# 1-Schematic_NotKia_168x.net
KiCad netlist of a schematic drawn in EasyEDA
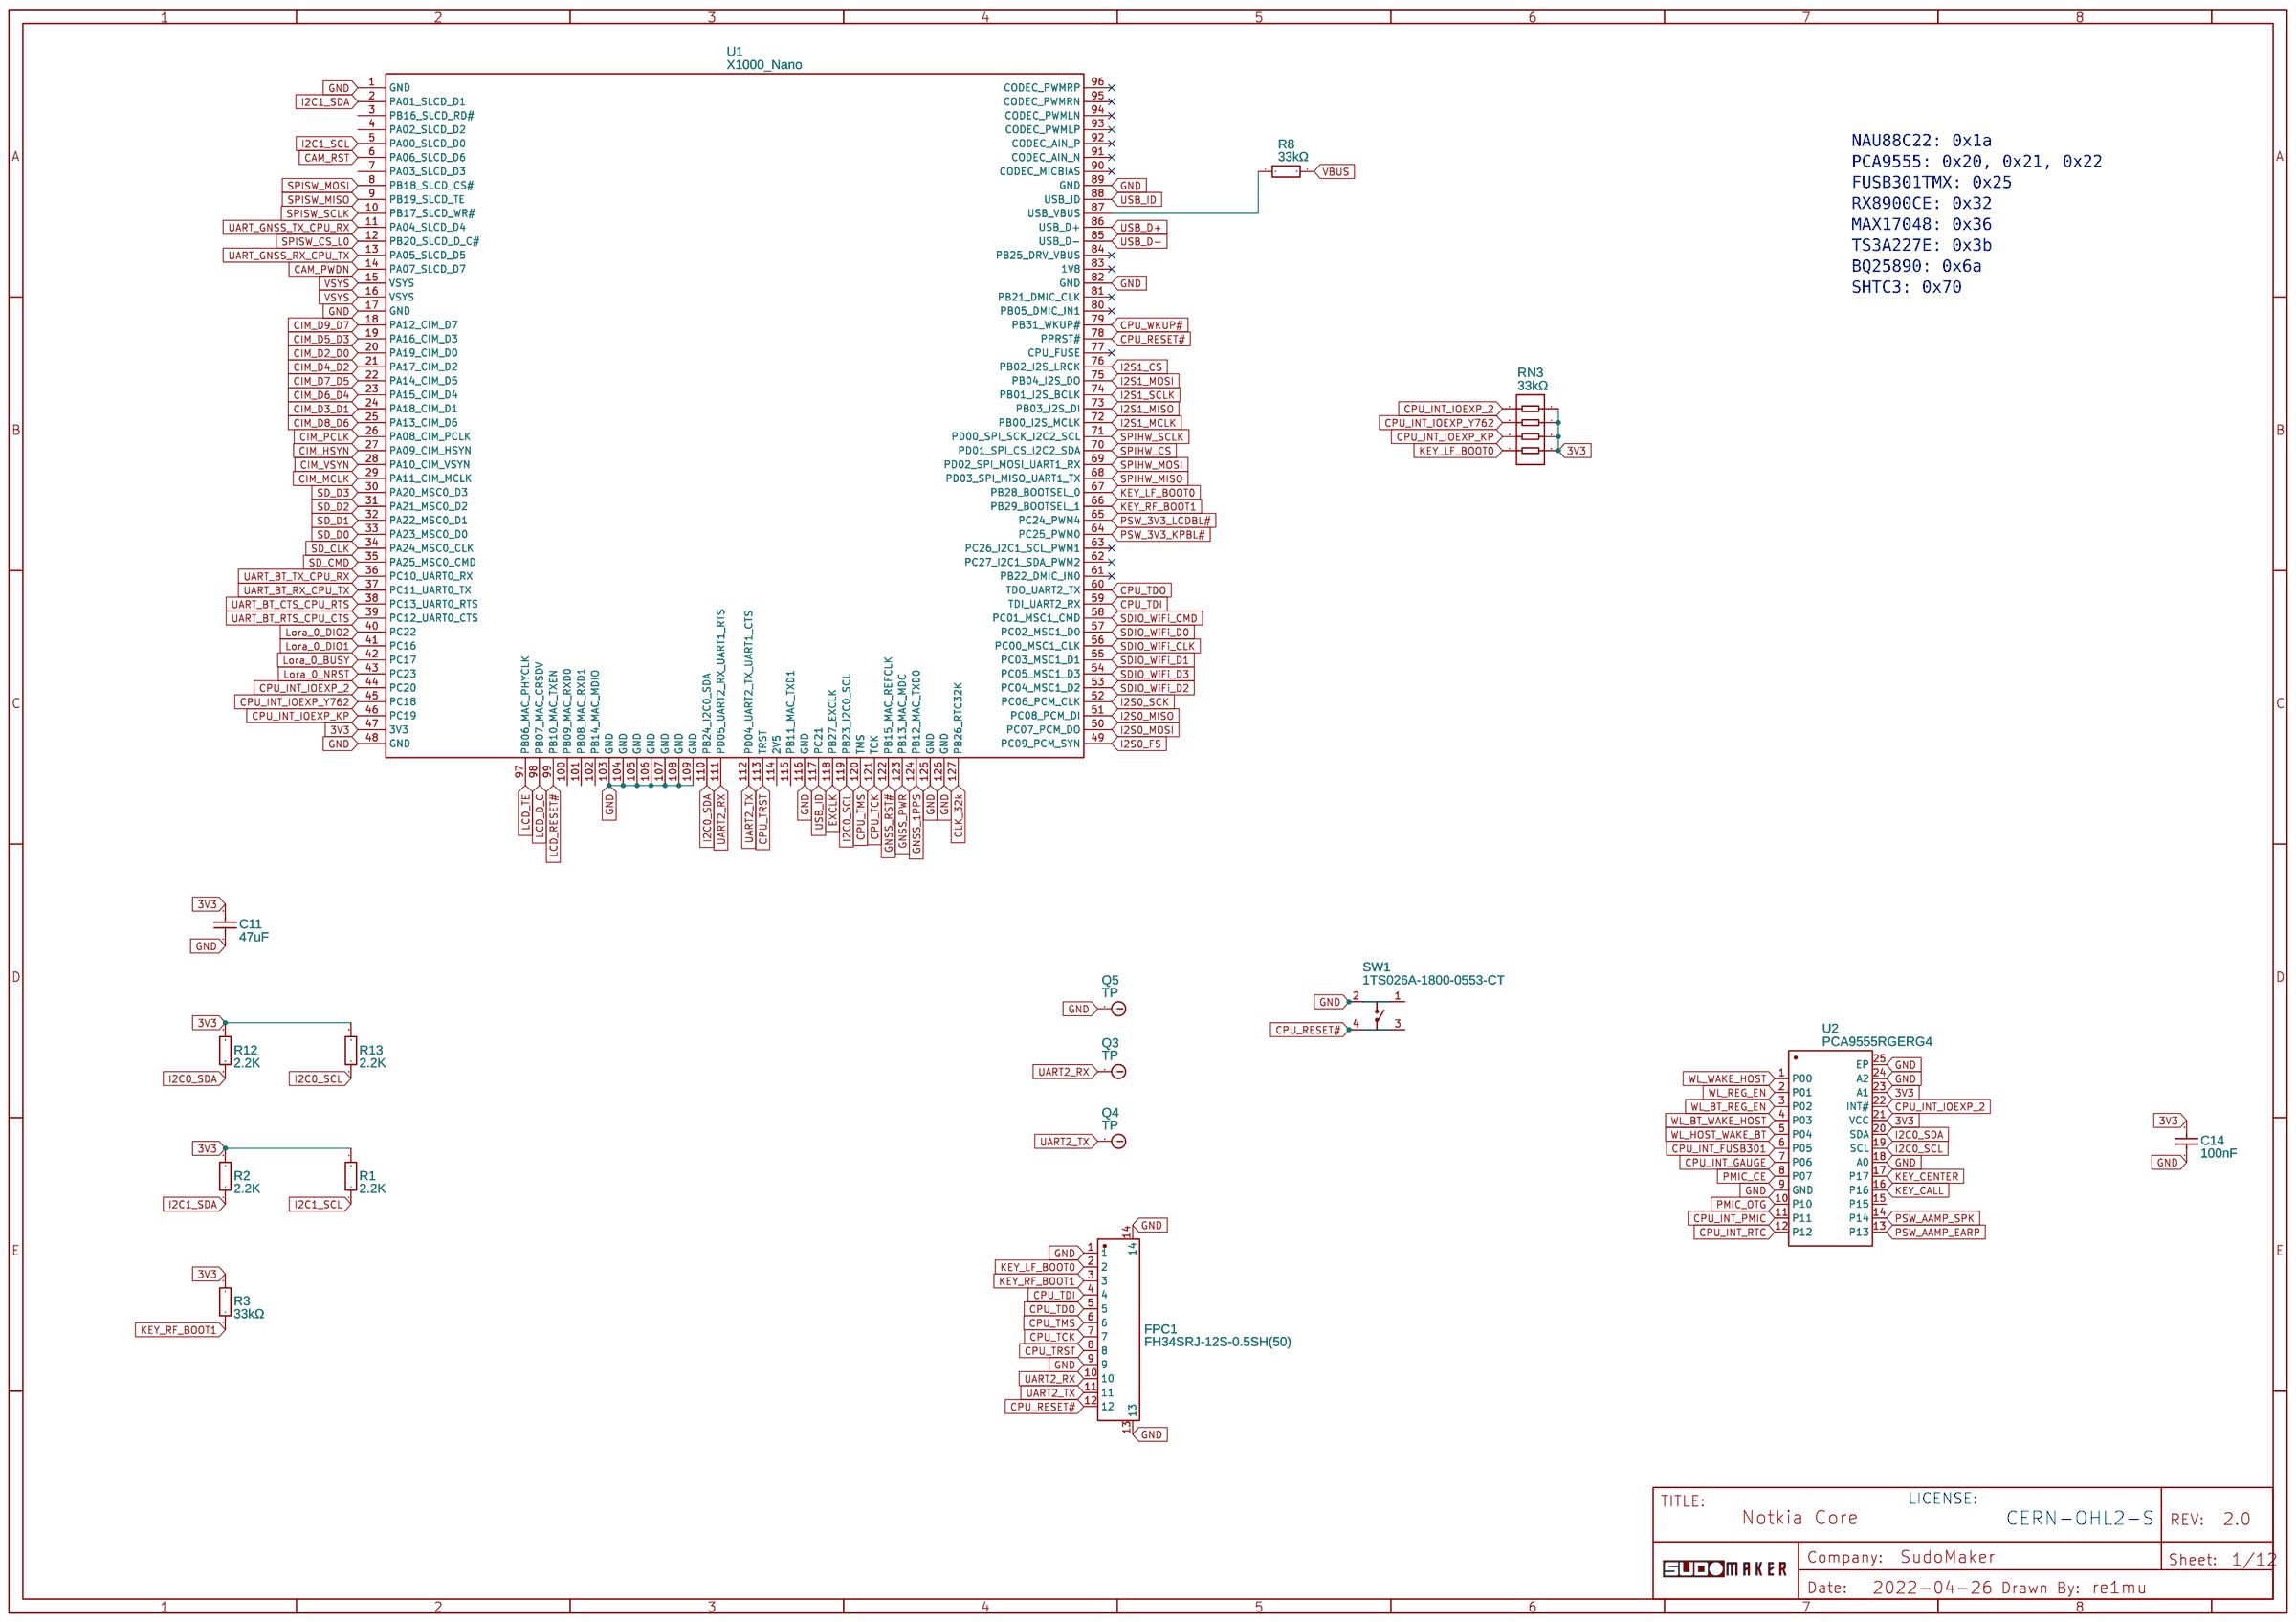
[diagram p0: Core]
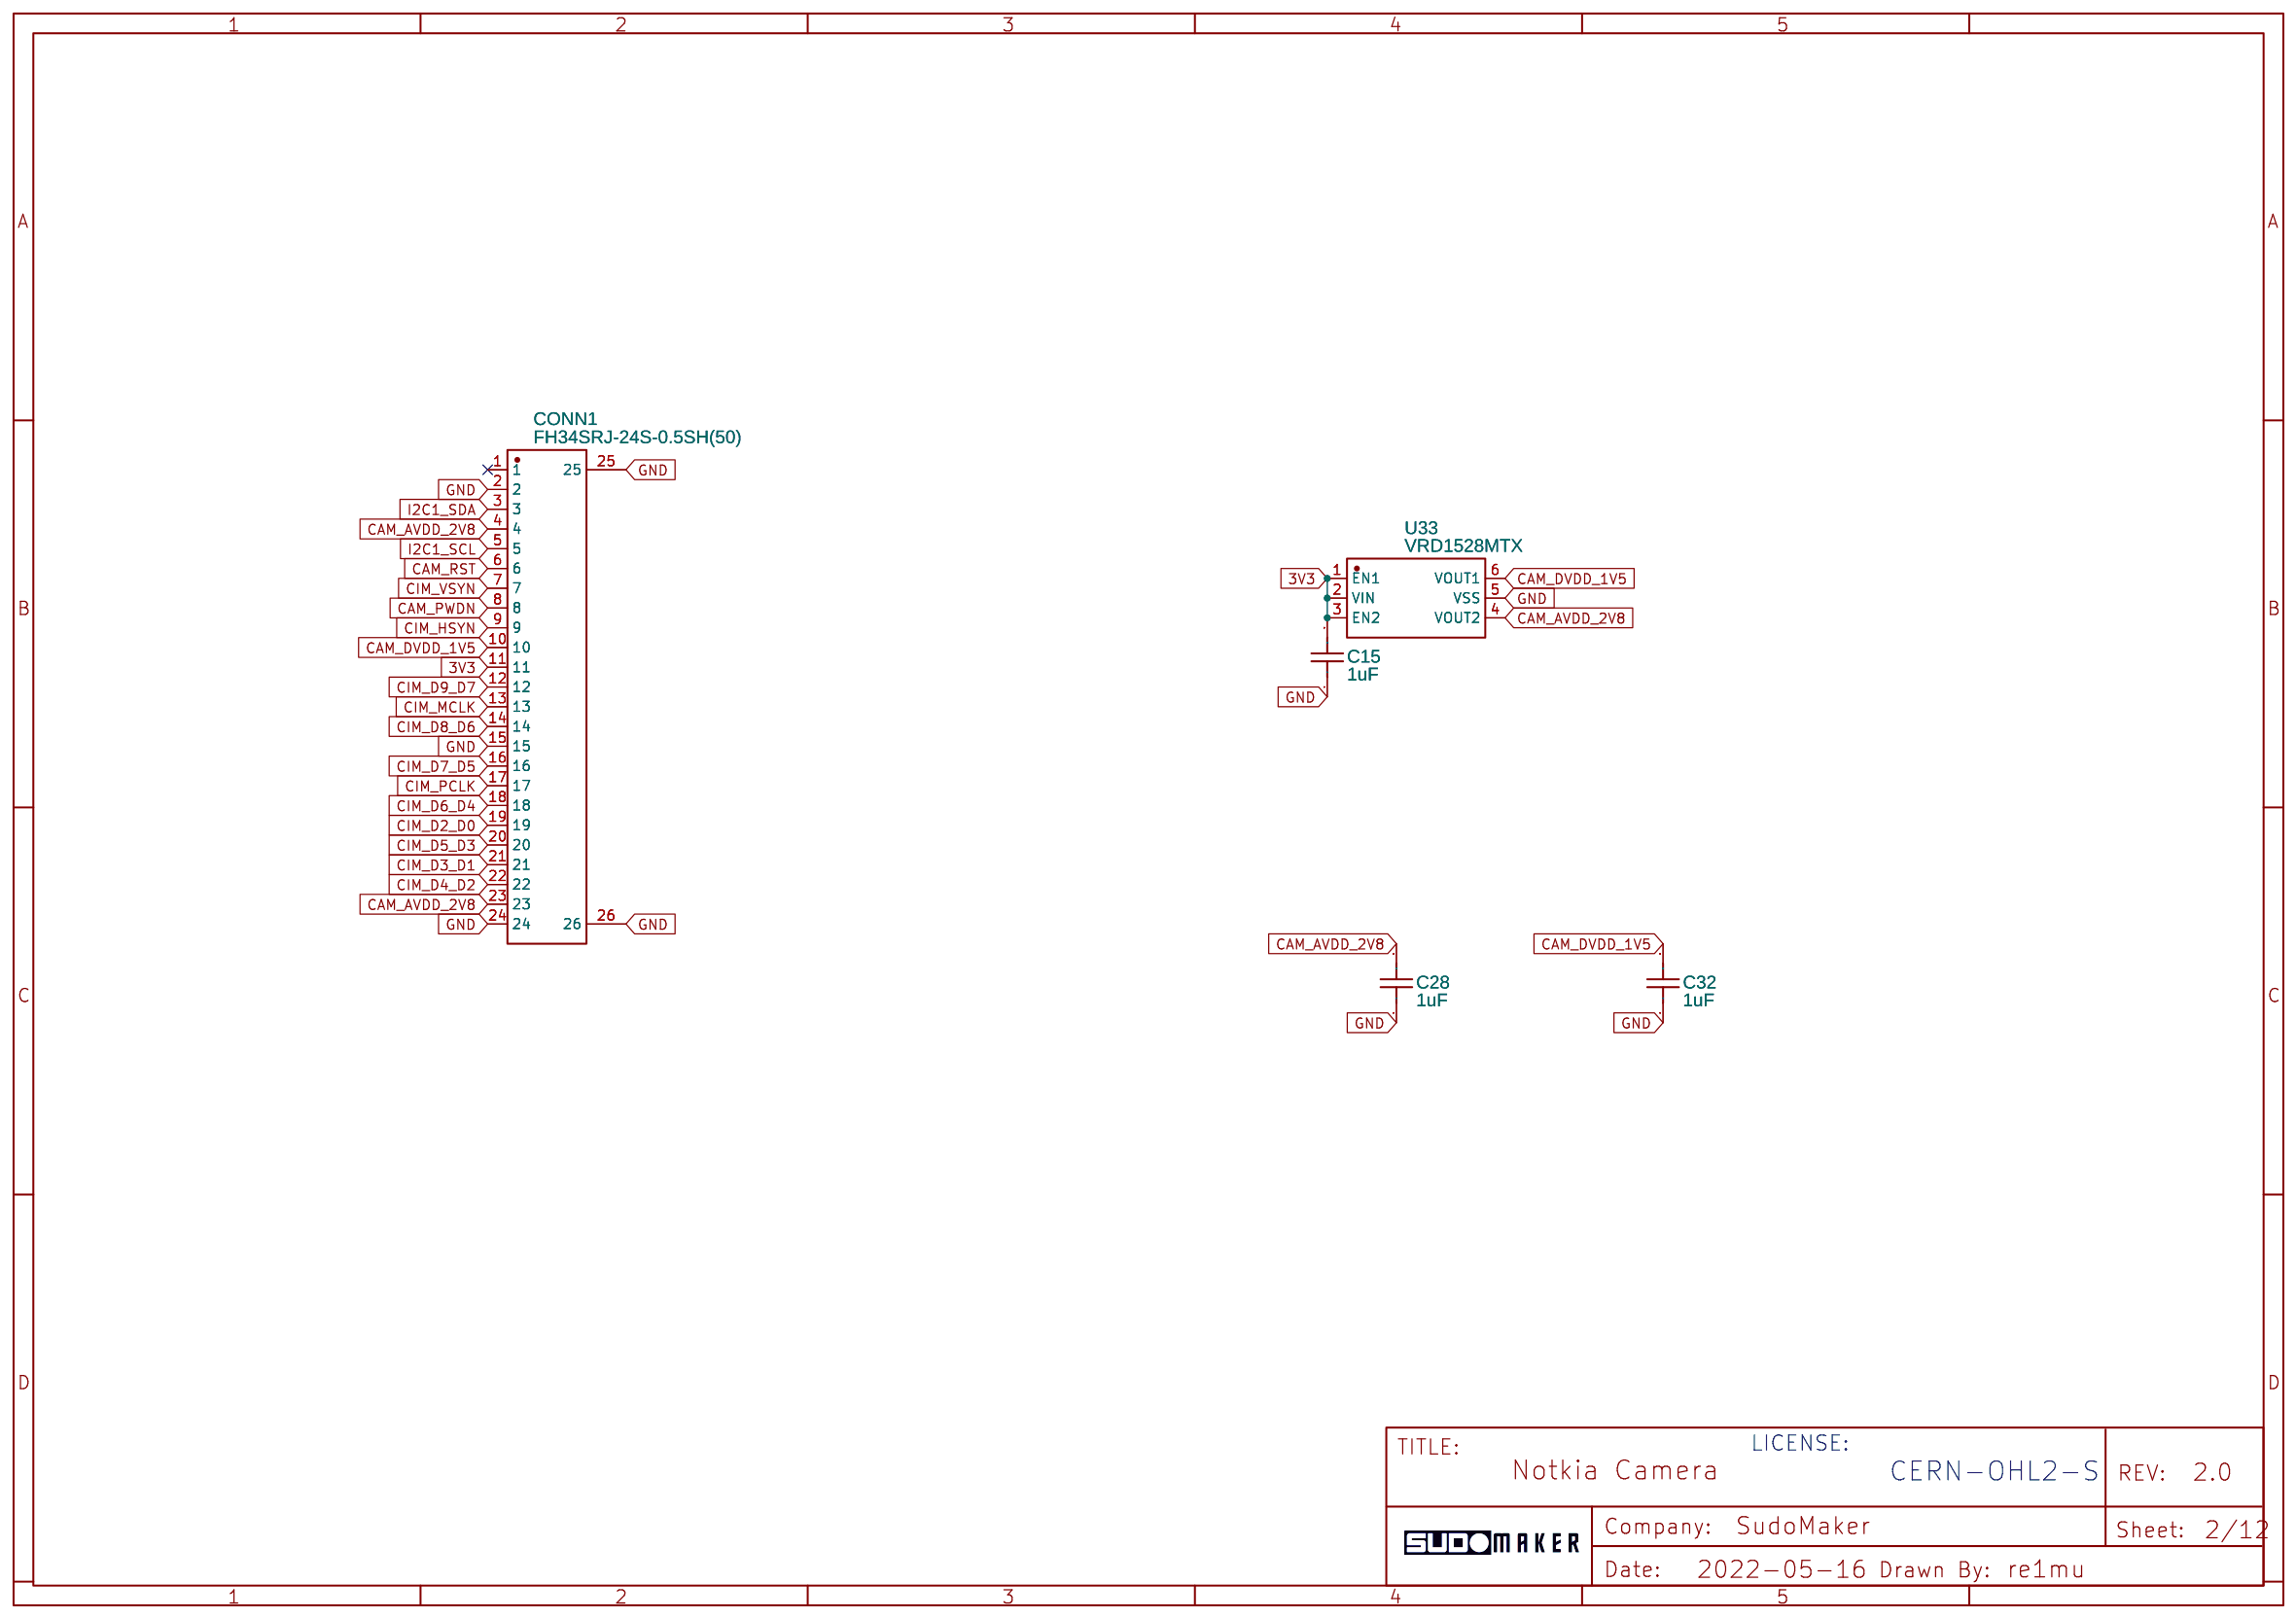
[diagram p1: Camera]
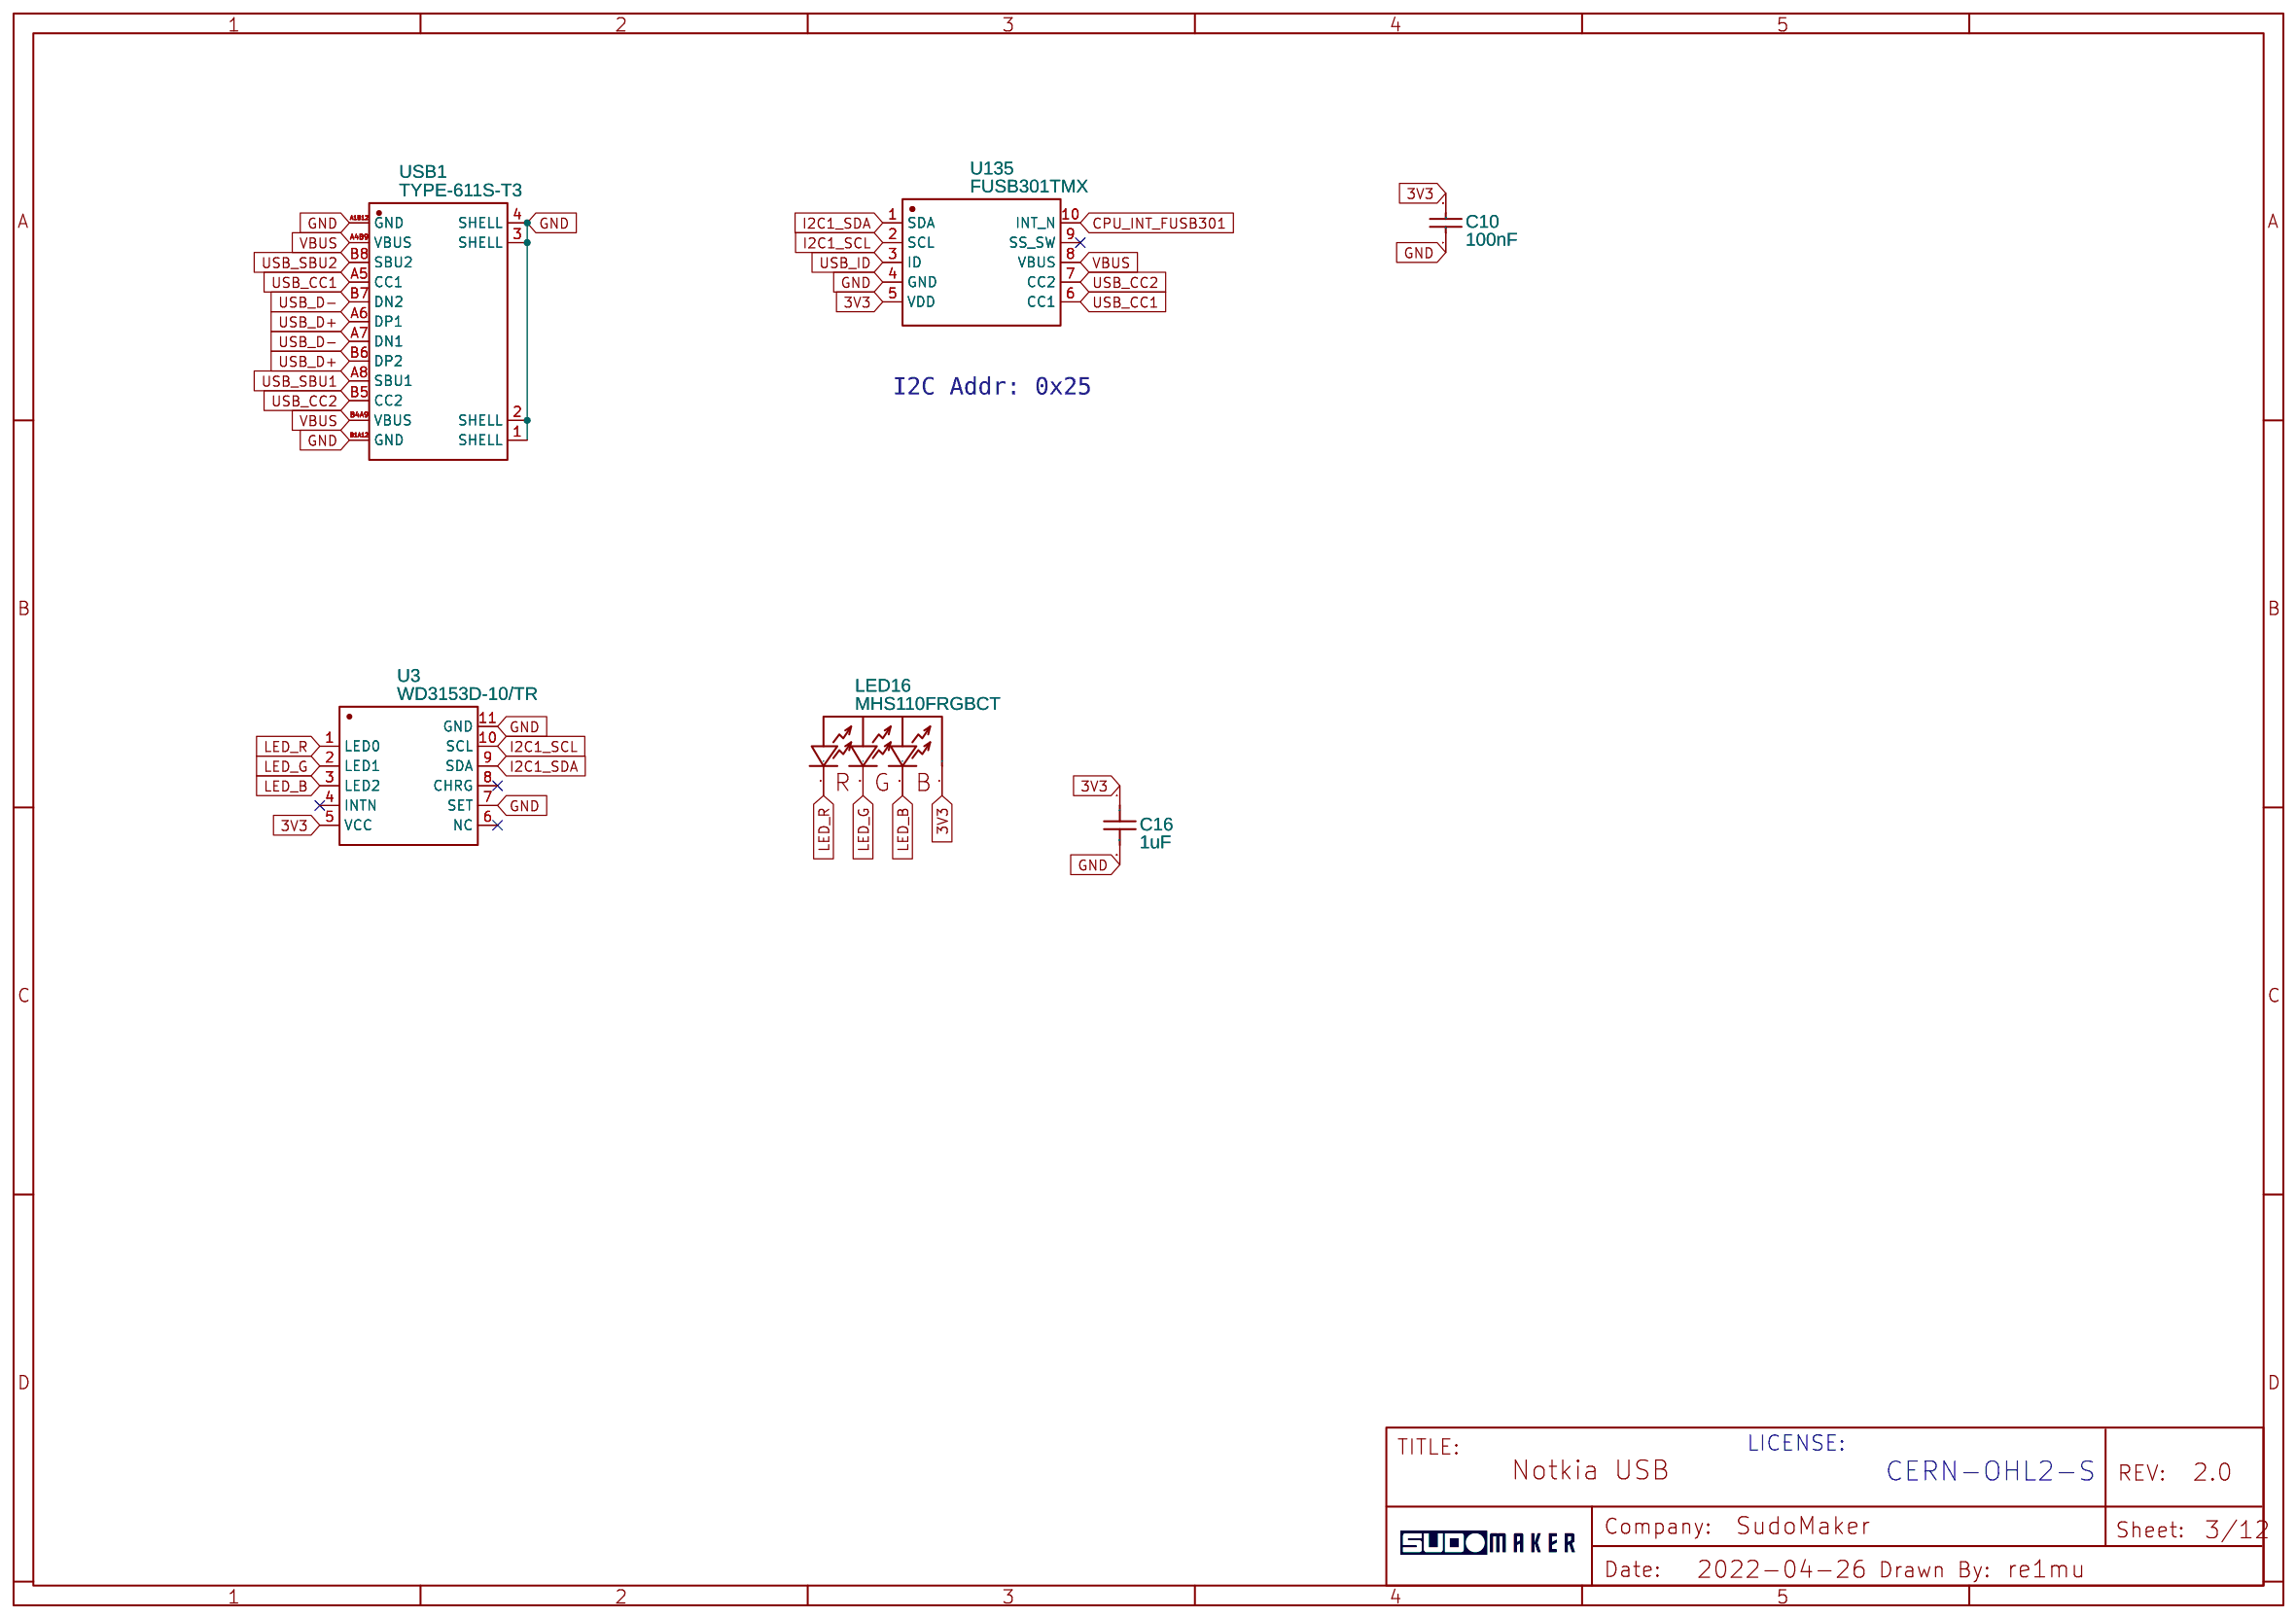
[diagram p2: USB]
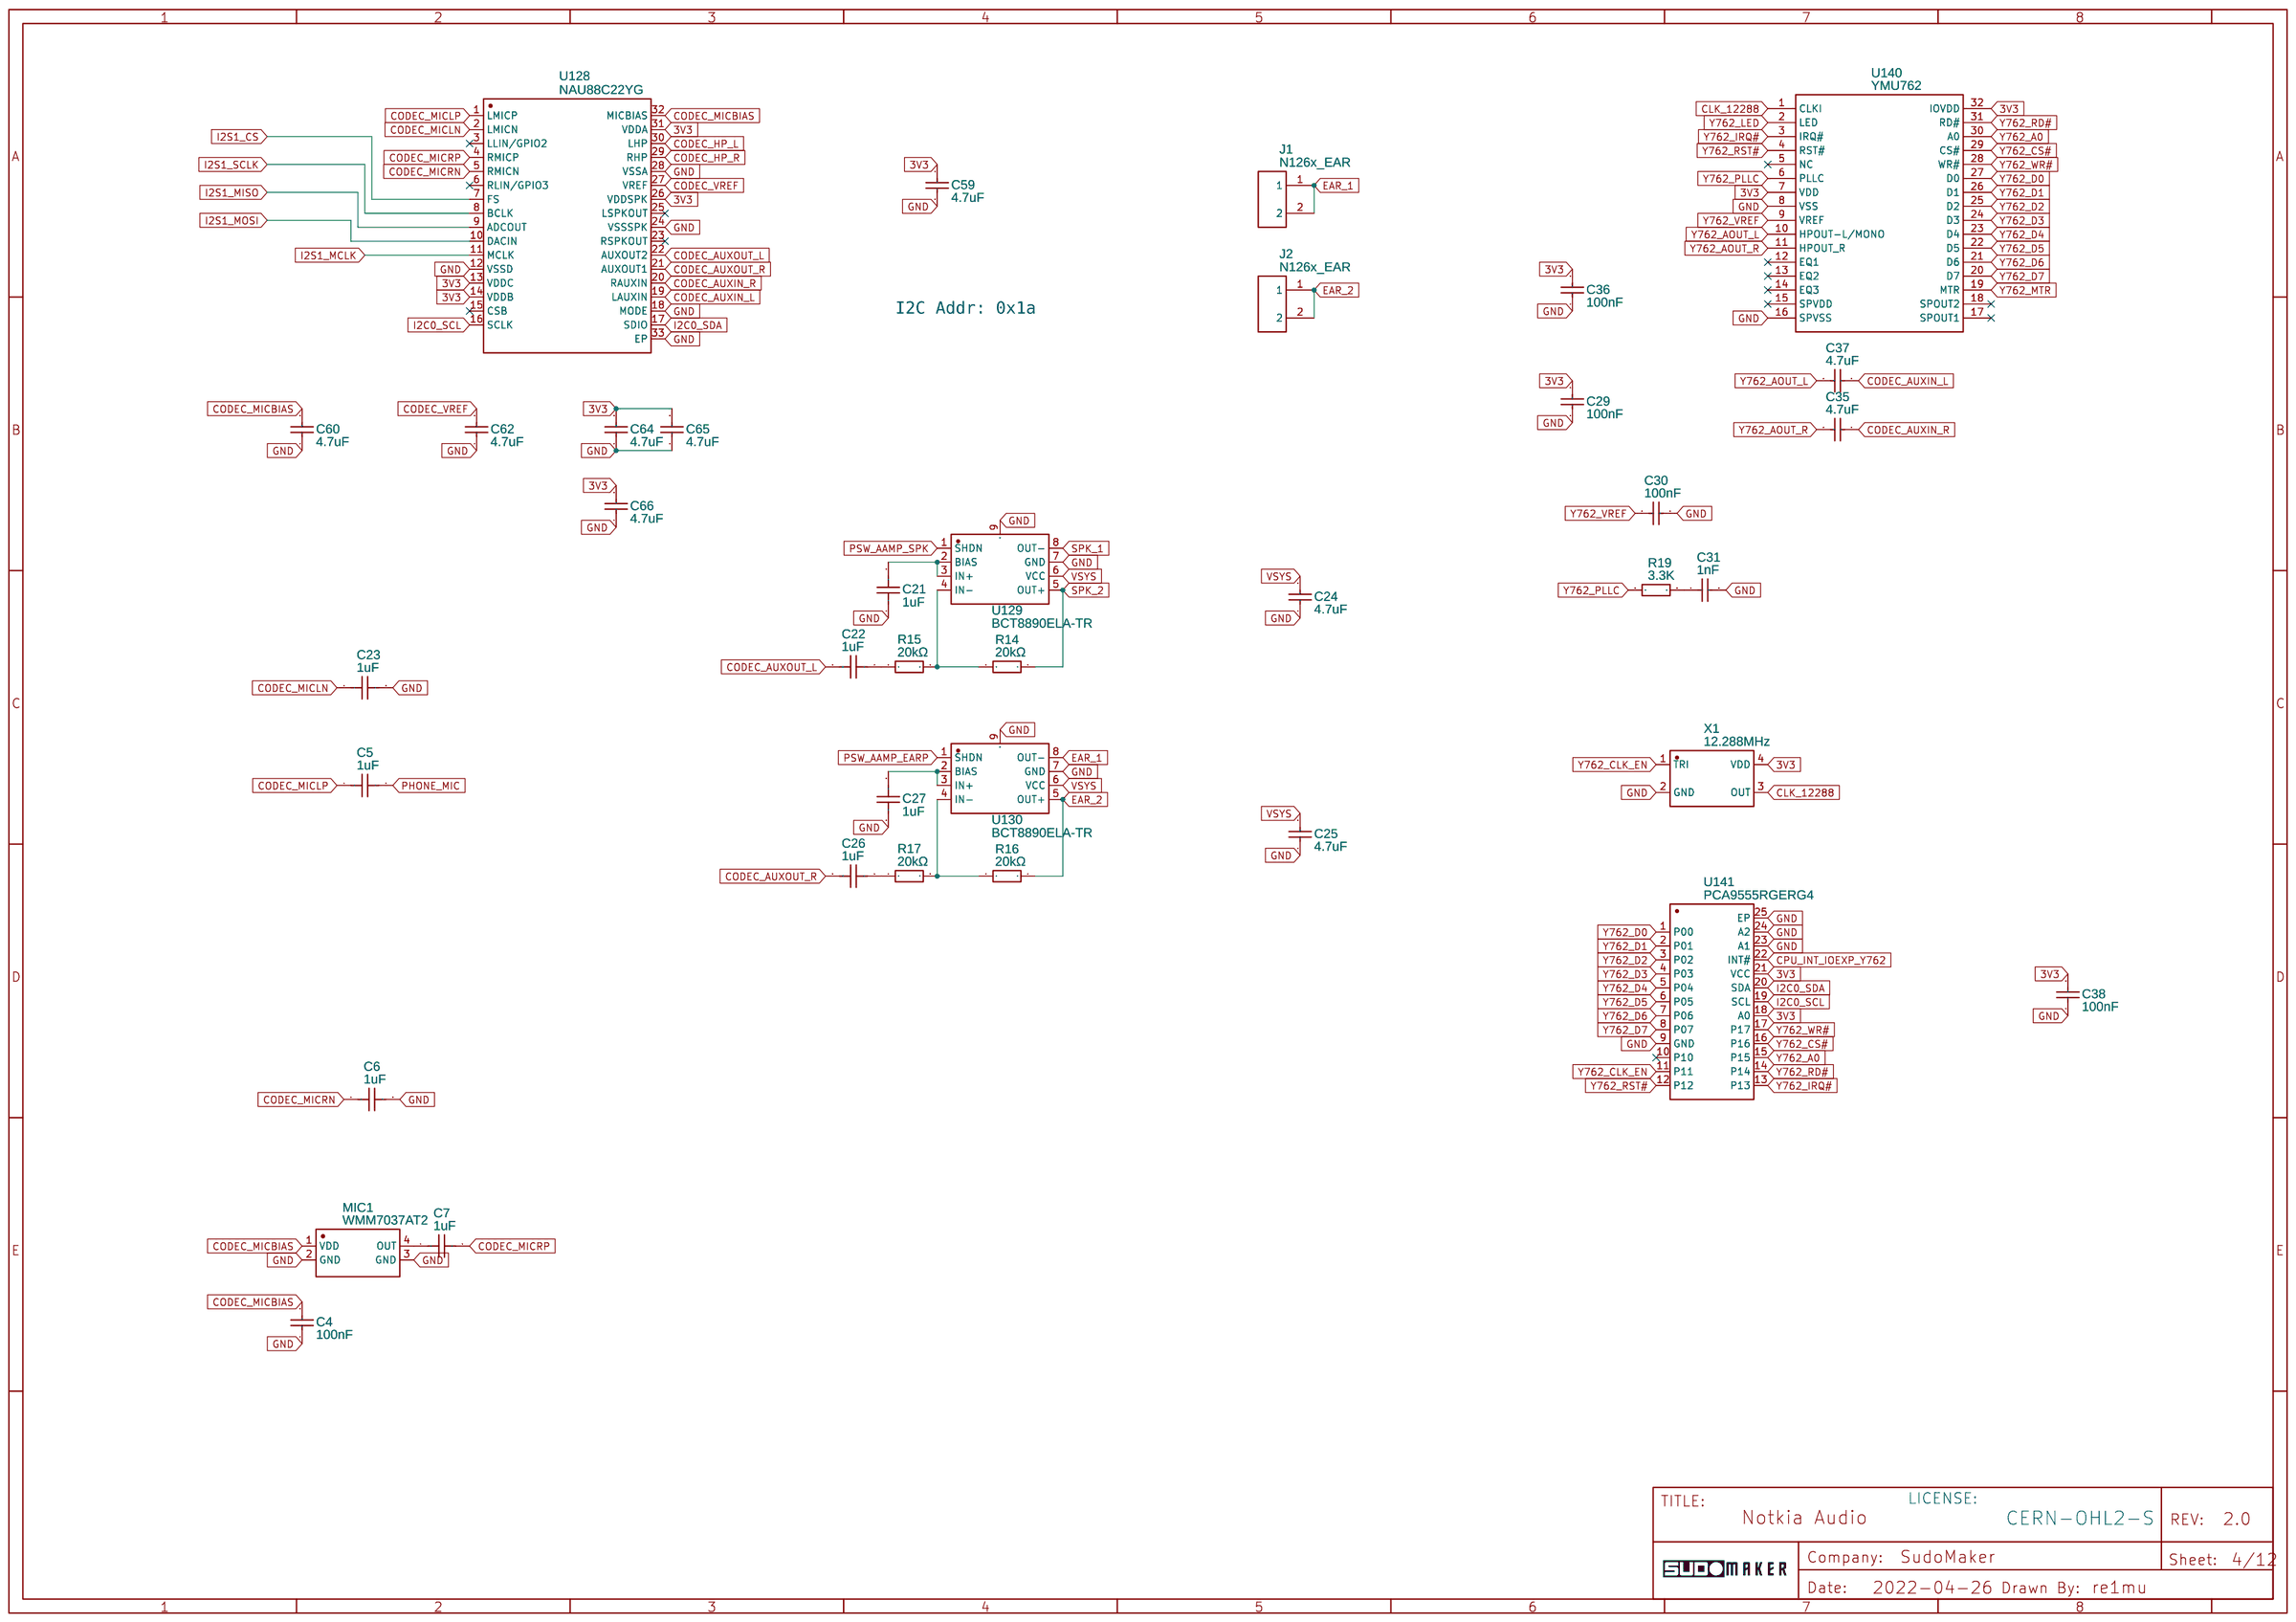
[diagram p3: Audio]
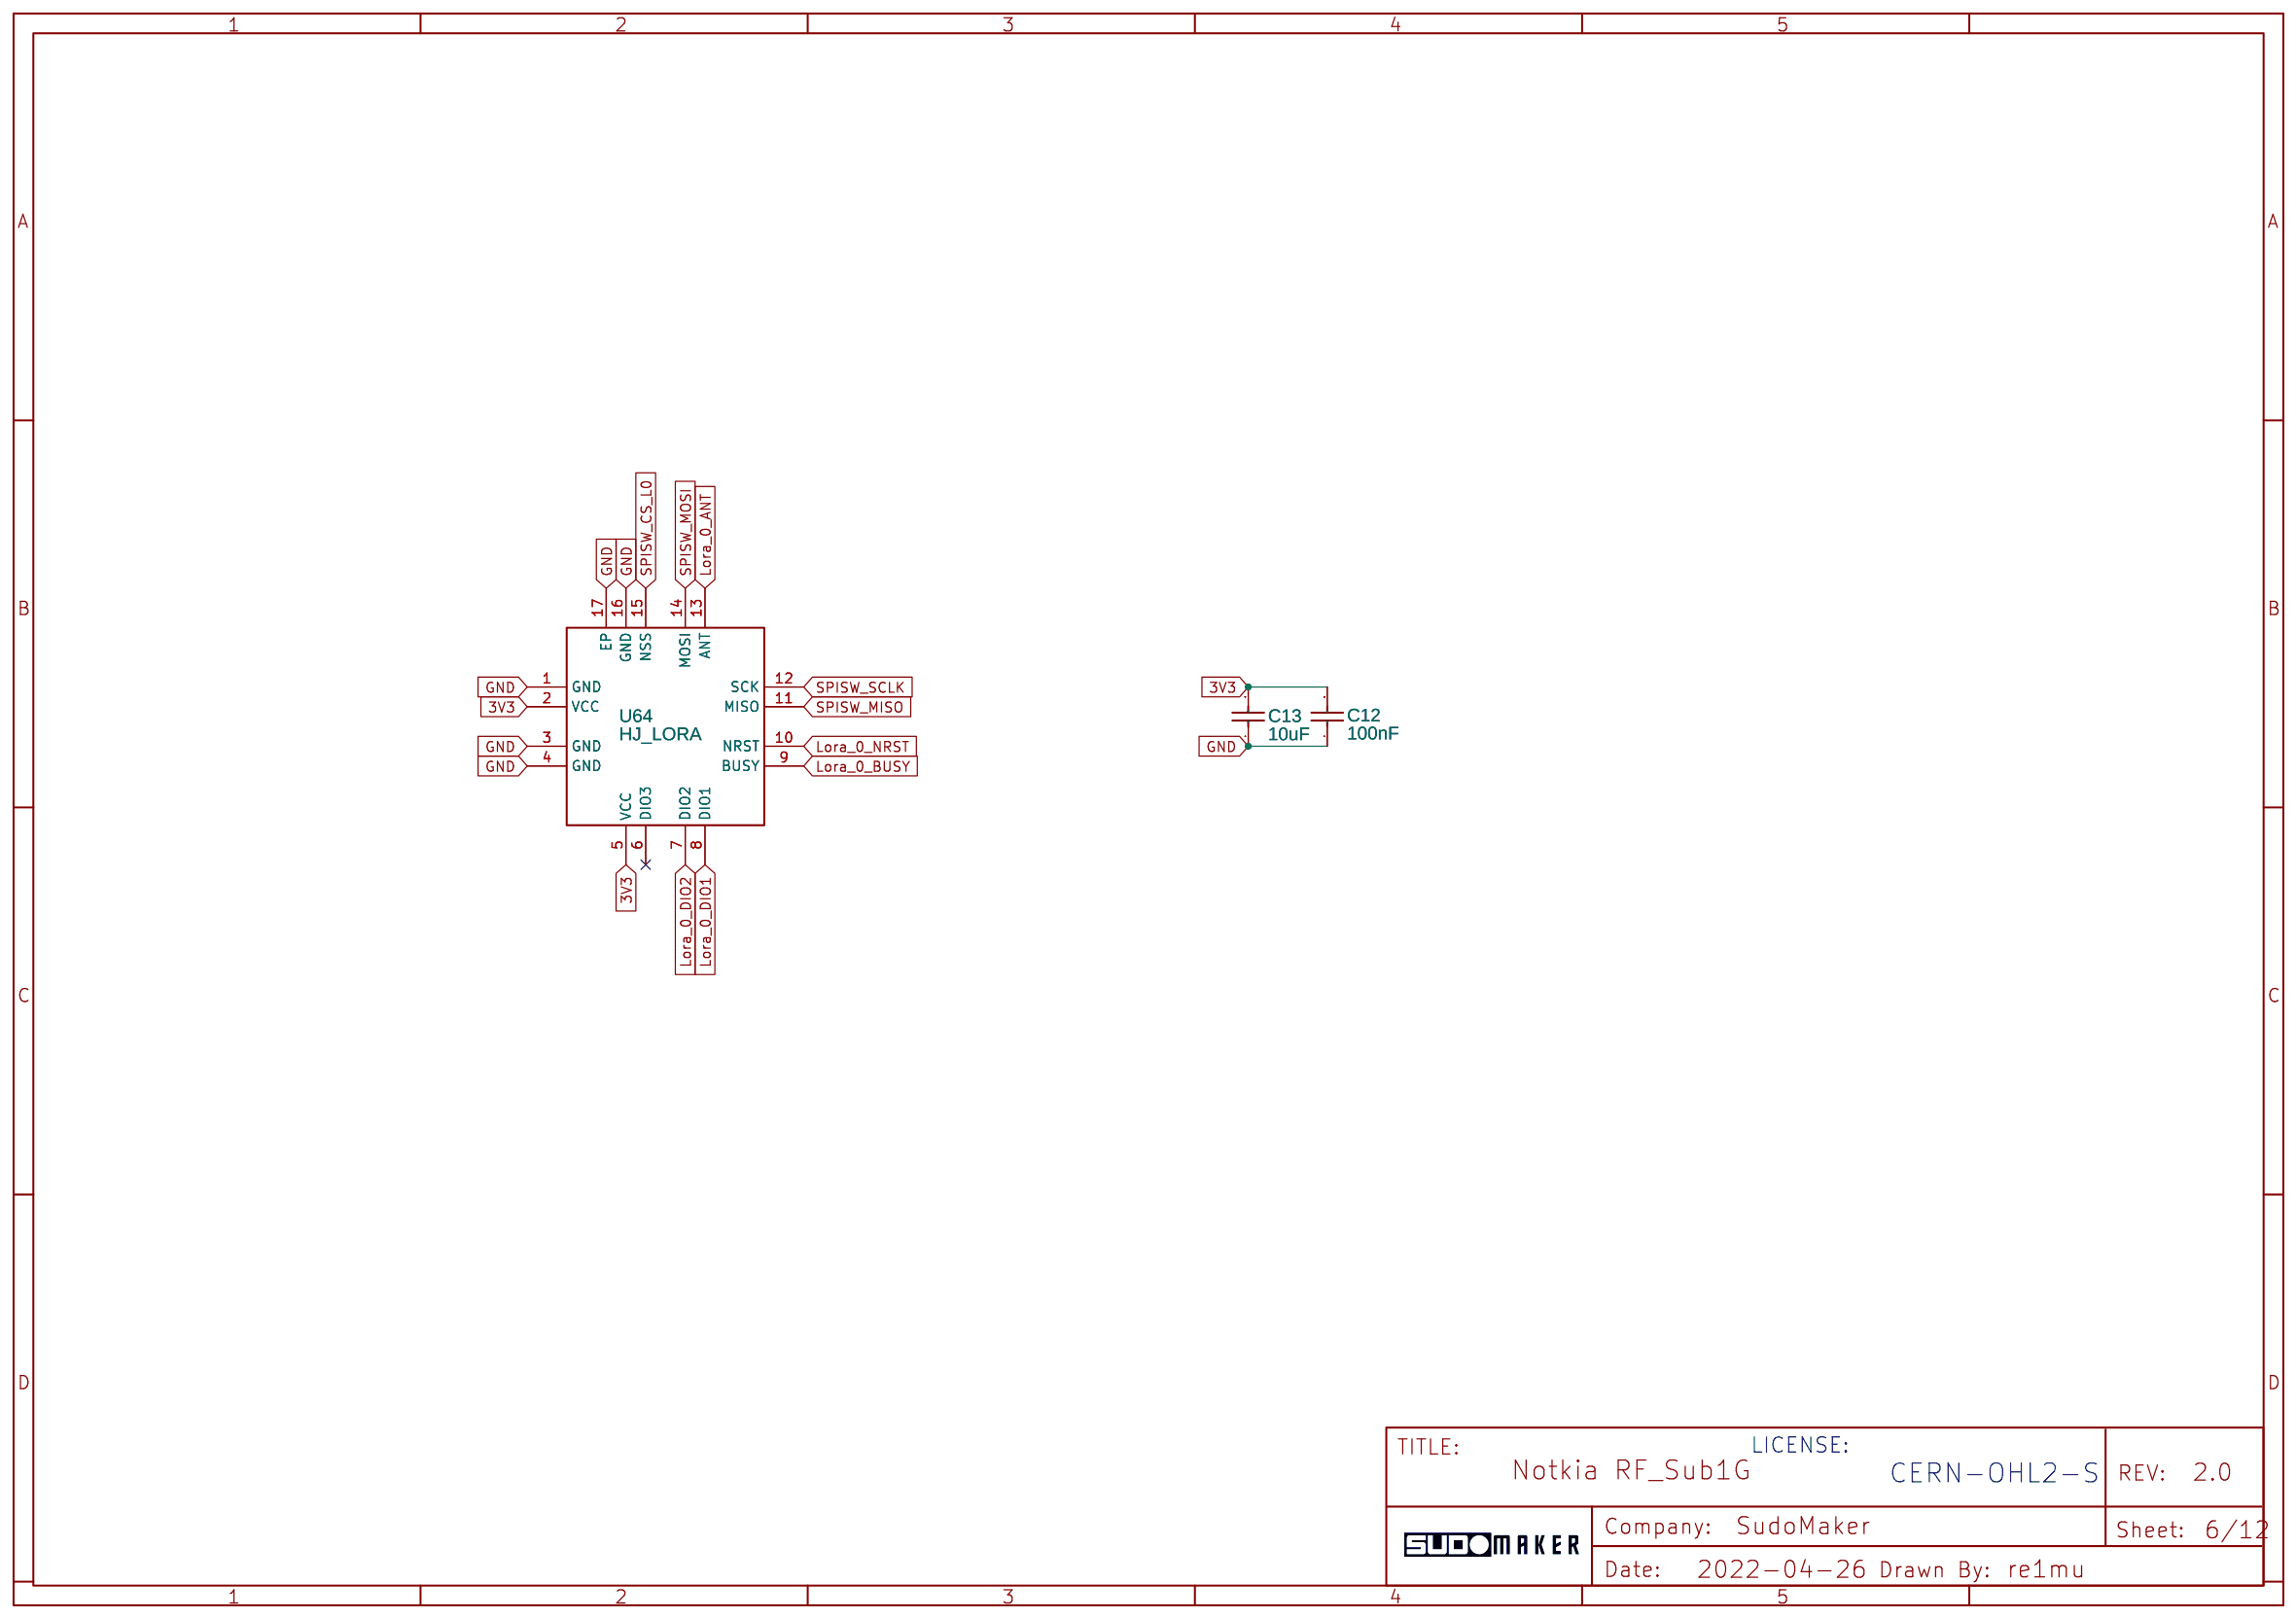
[diagram p4: RF_Sub1G]
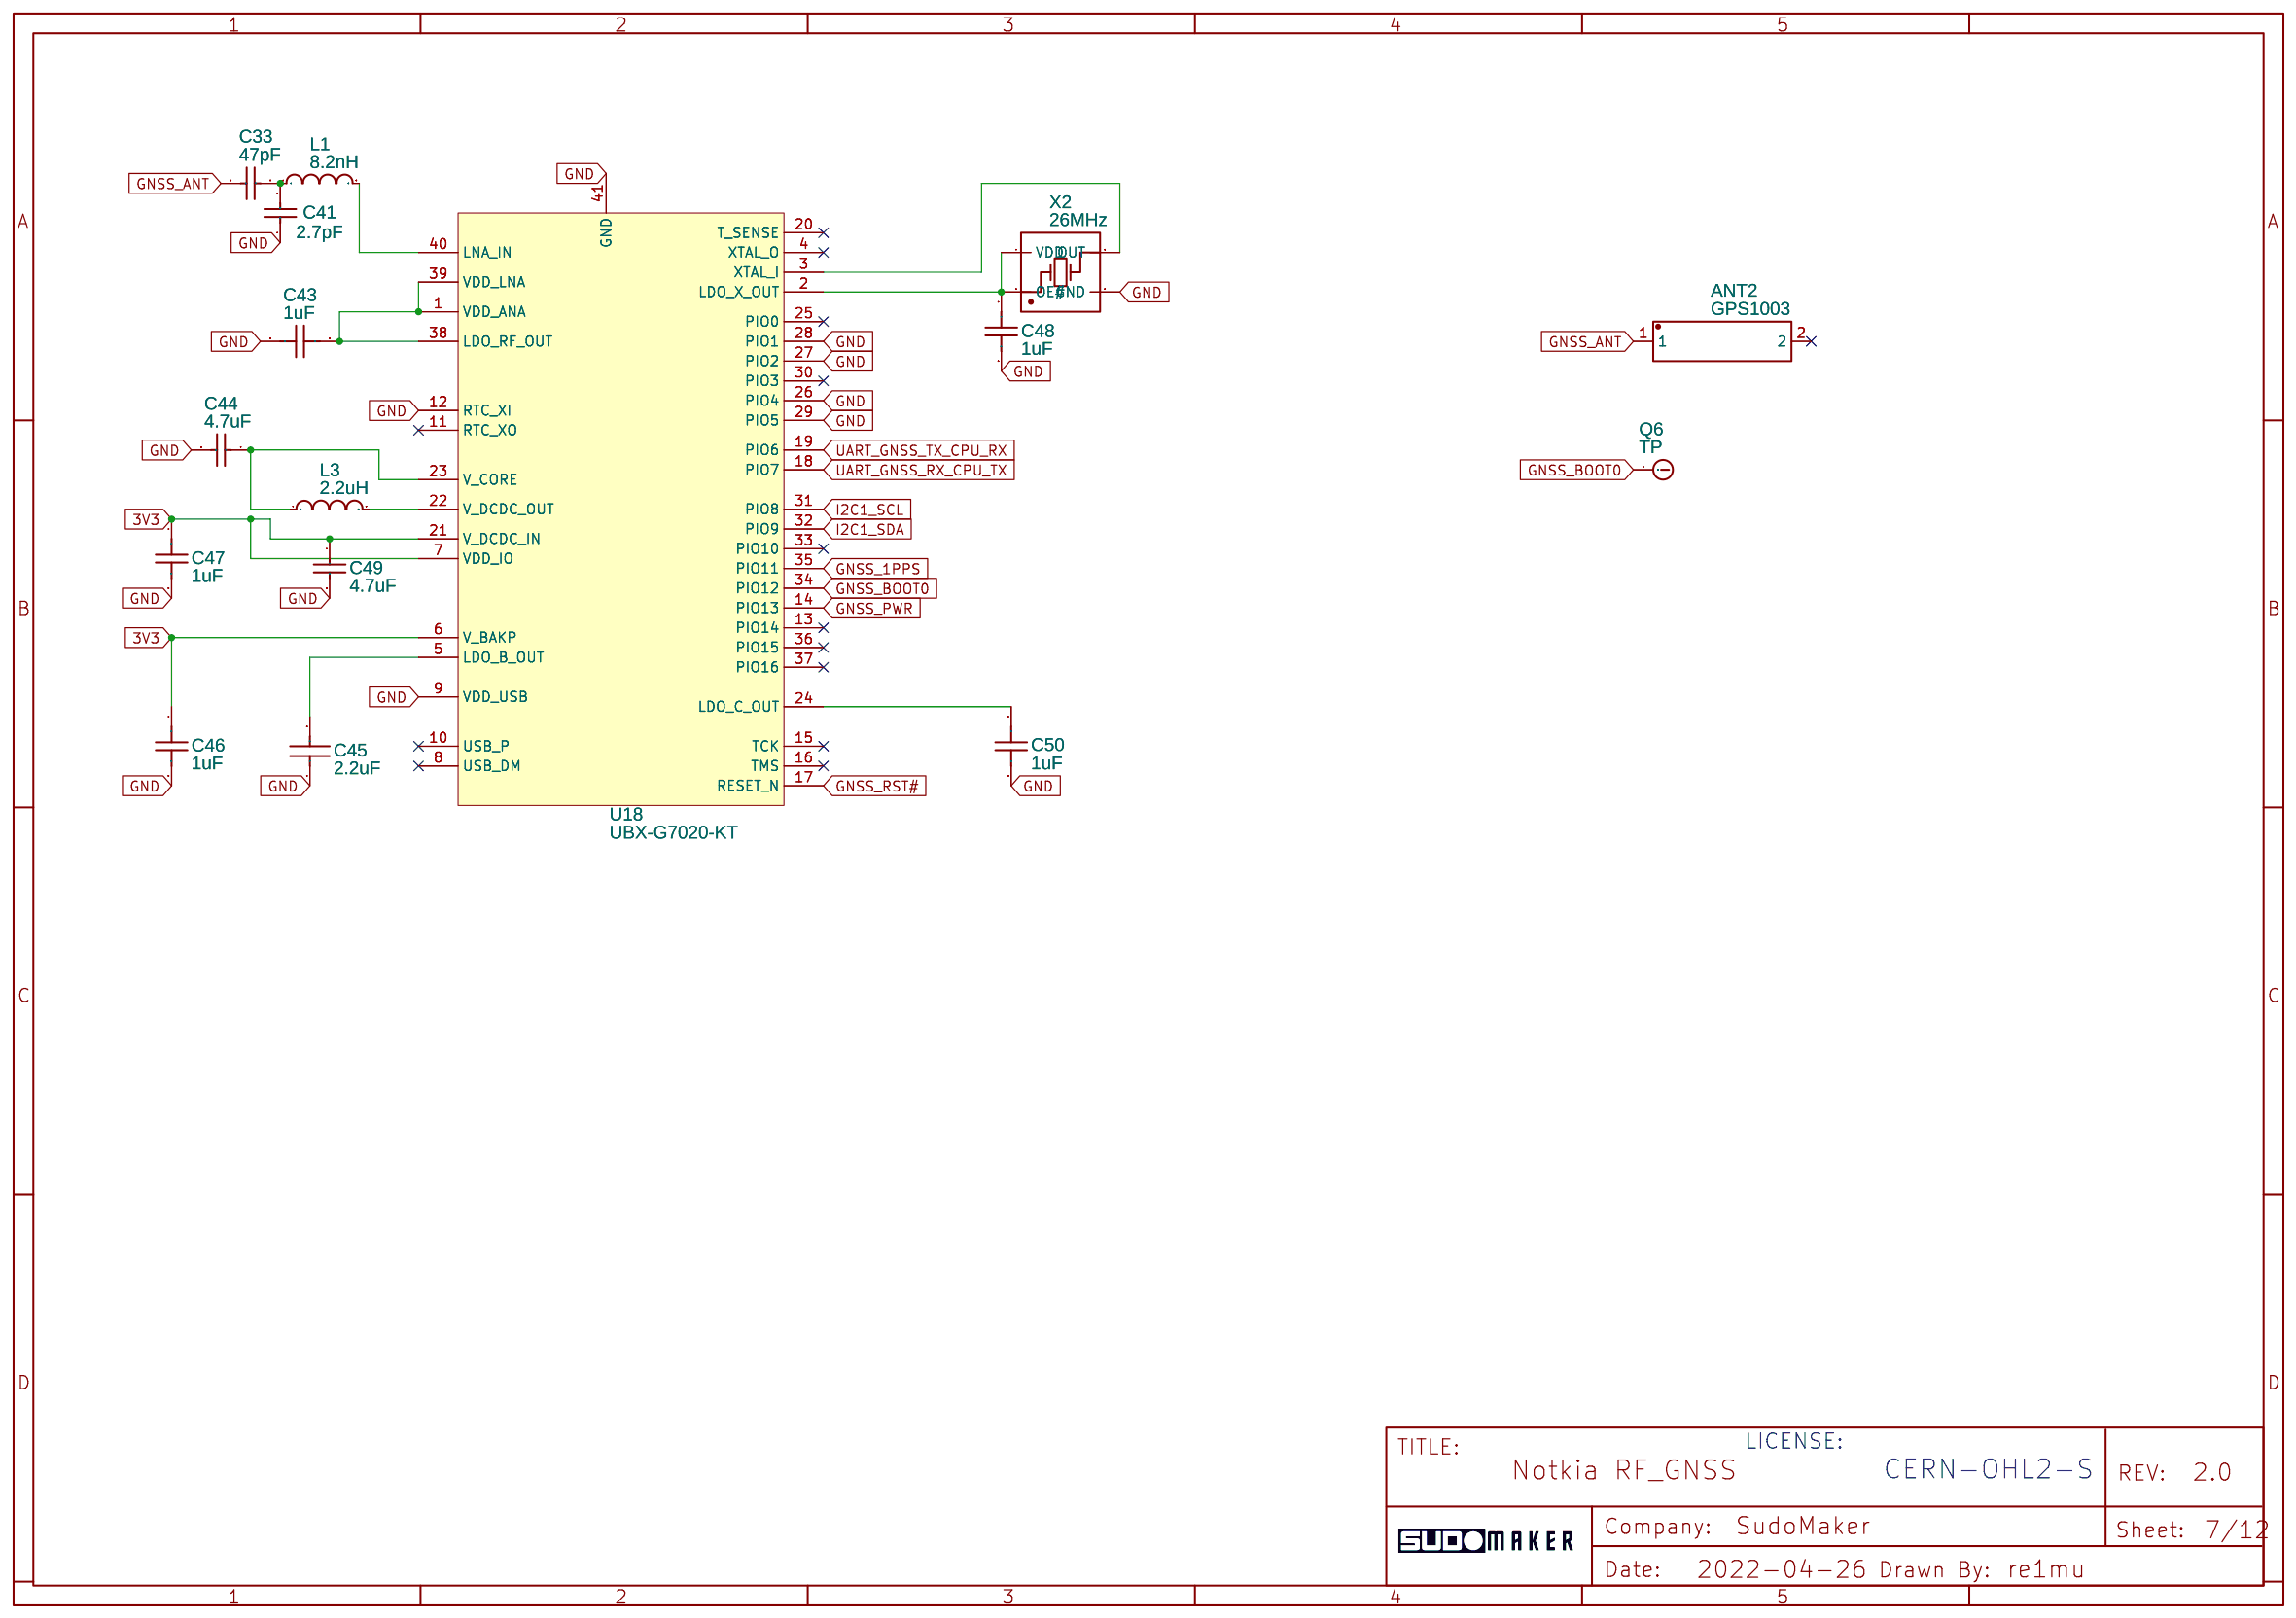
[diagram p5: RF_GNSS]
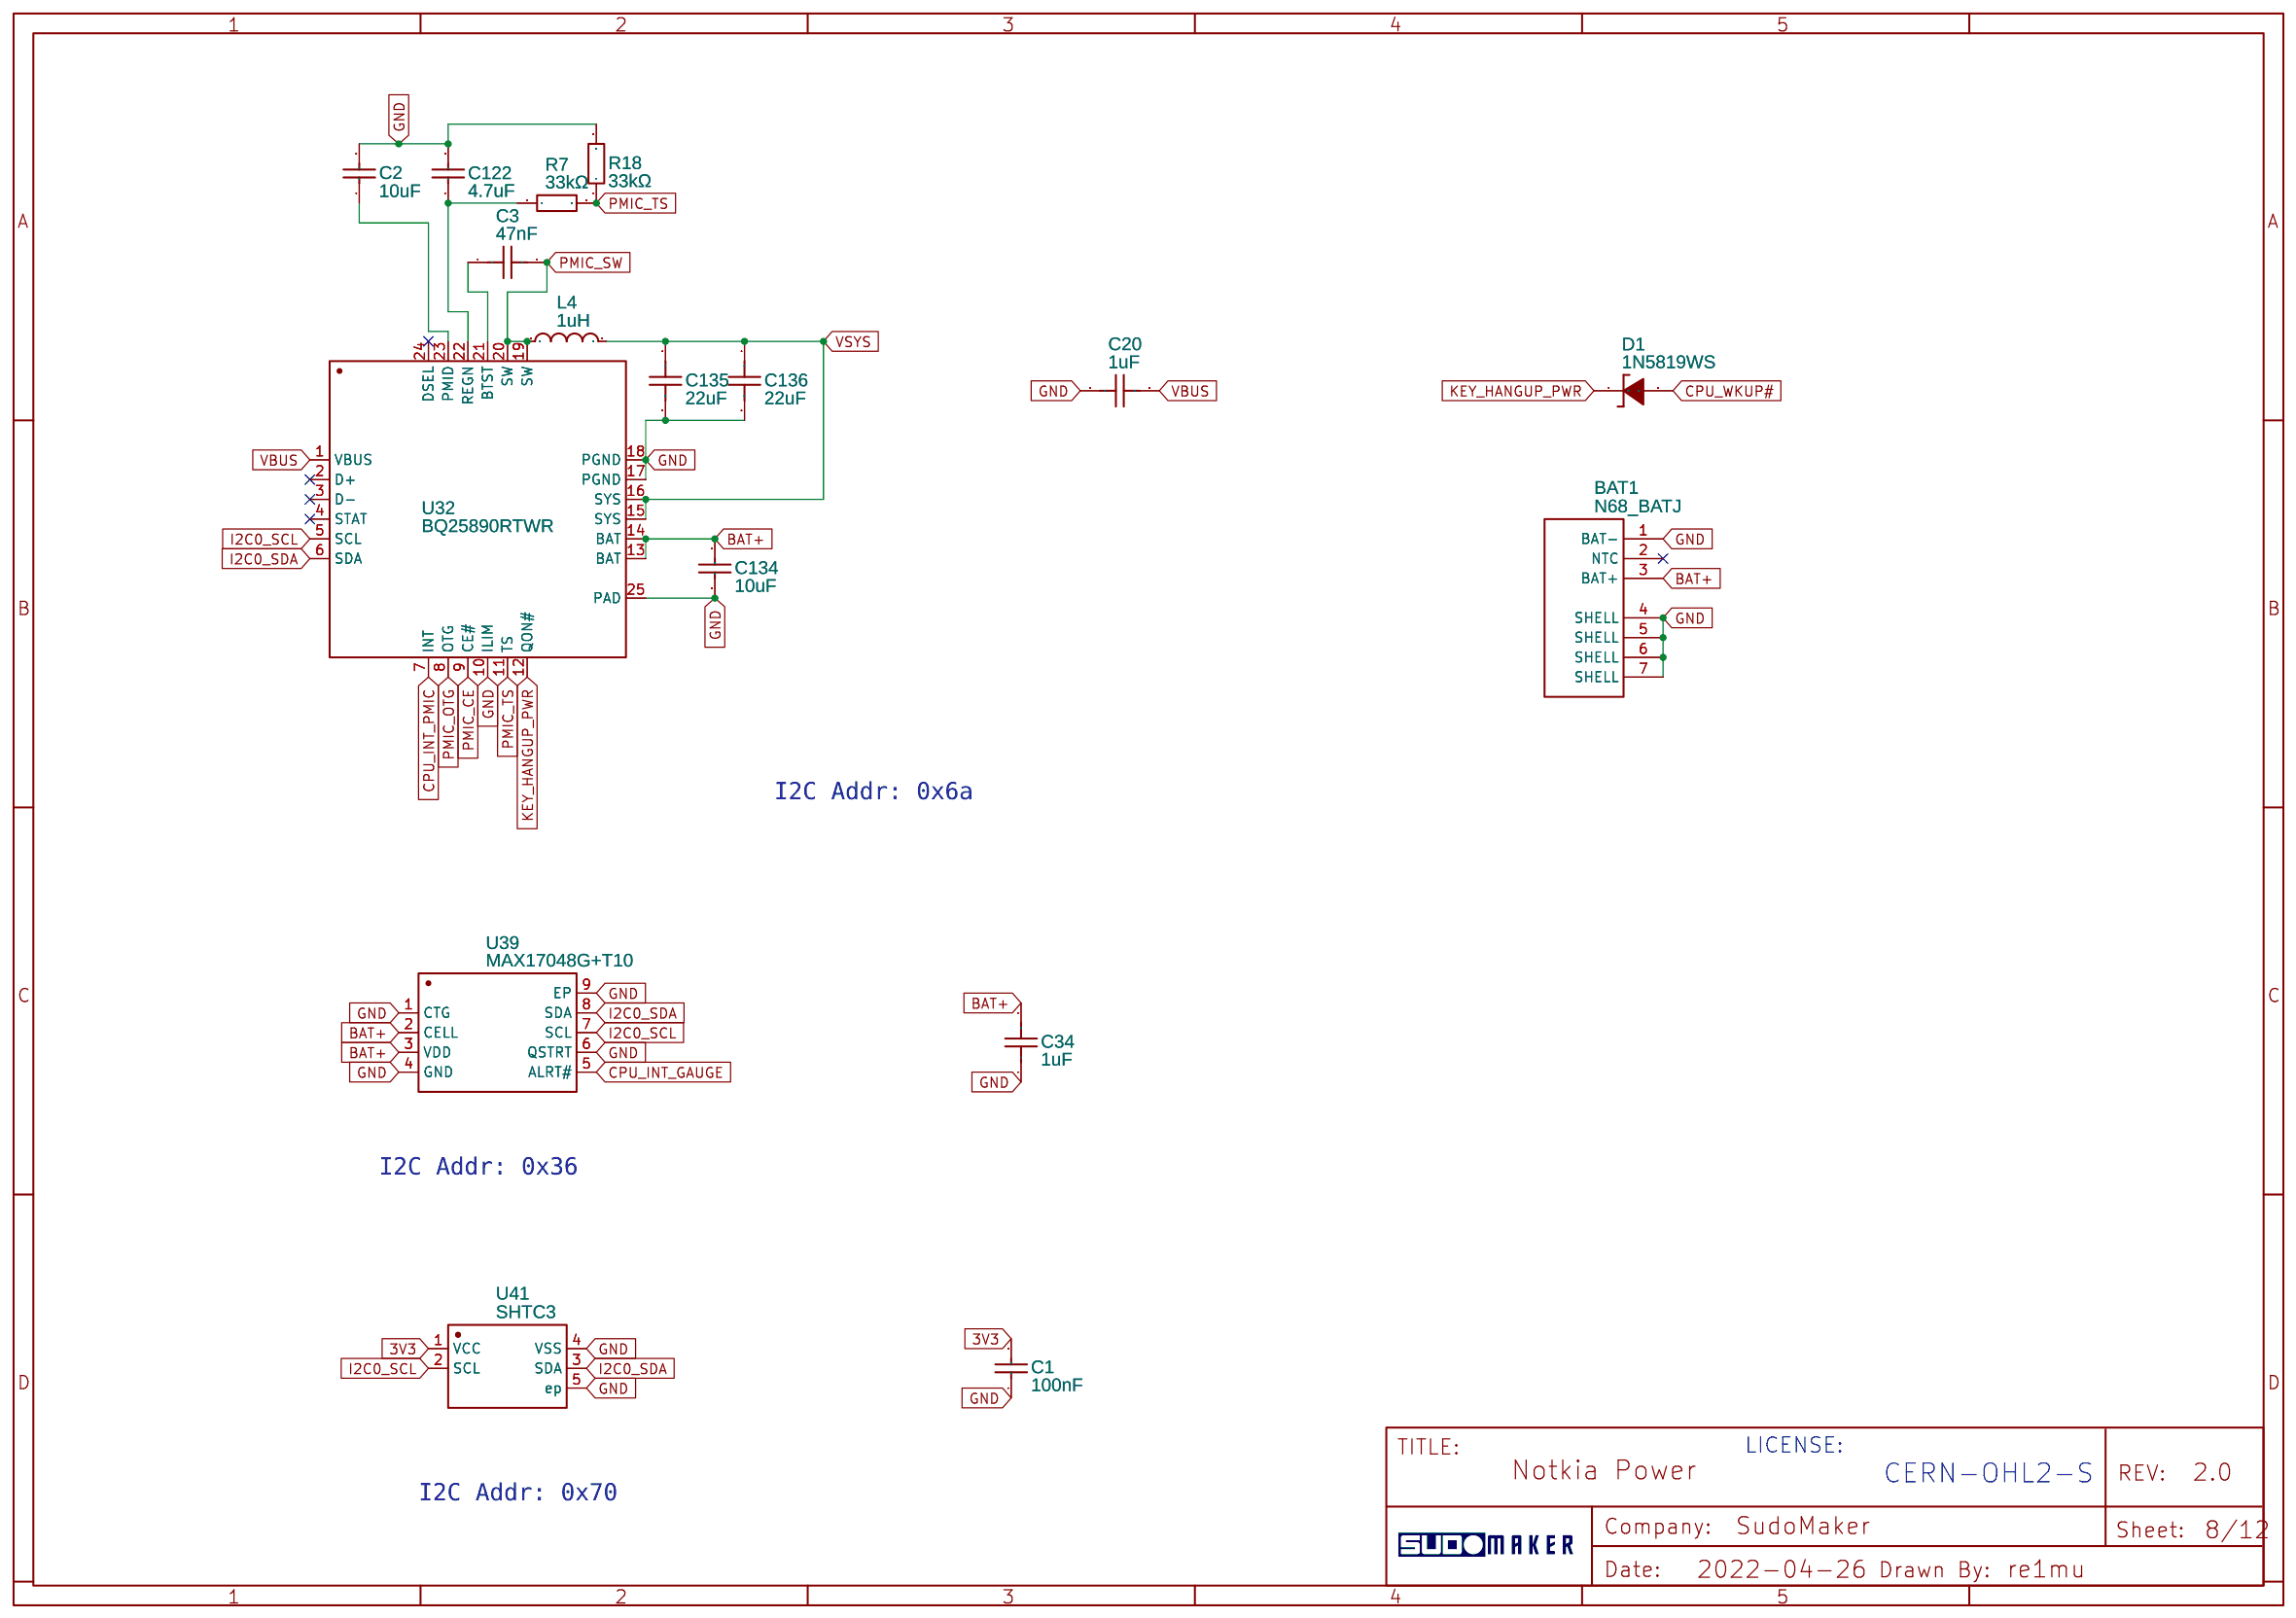
[diagram p6: Power]
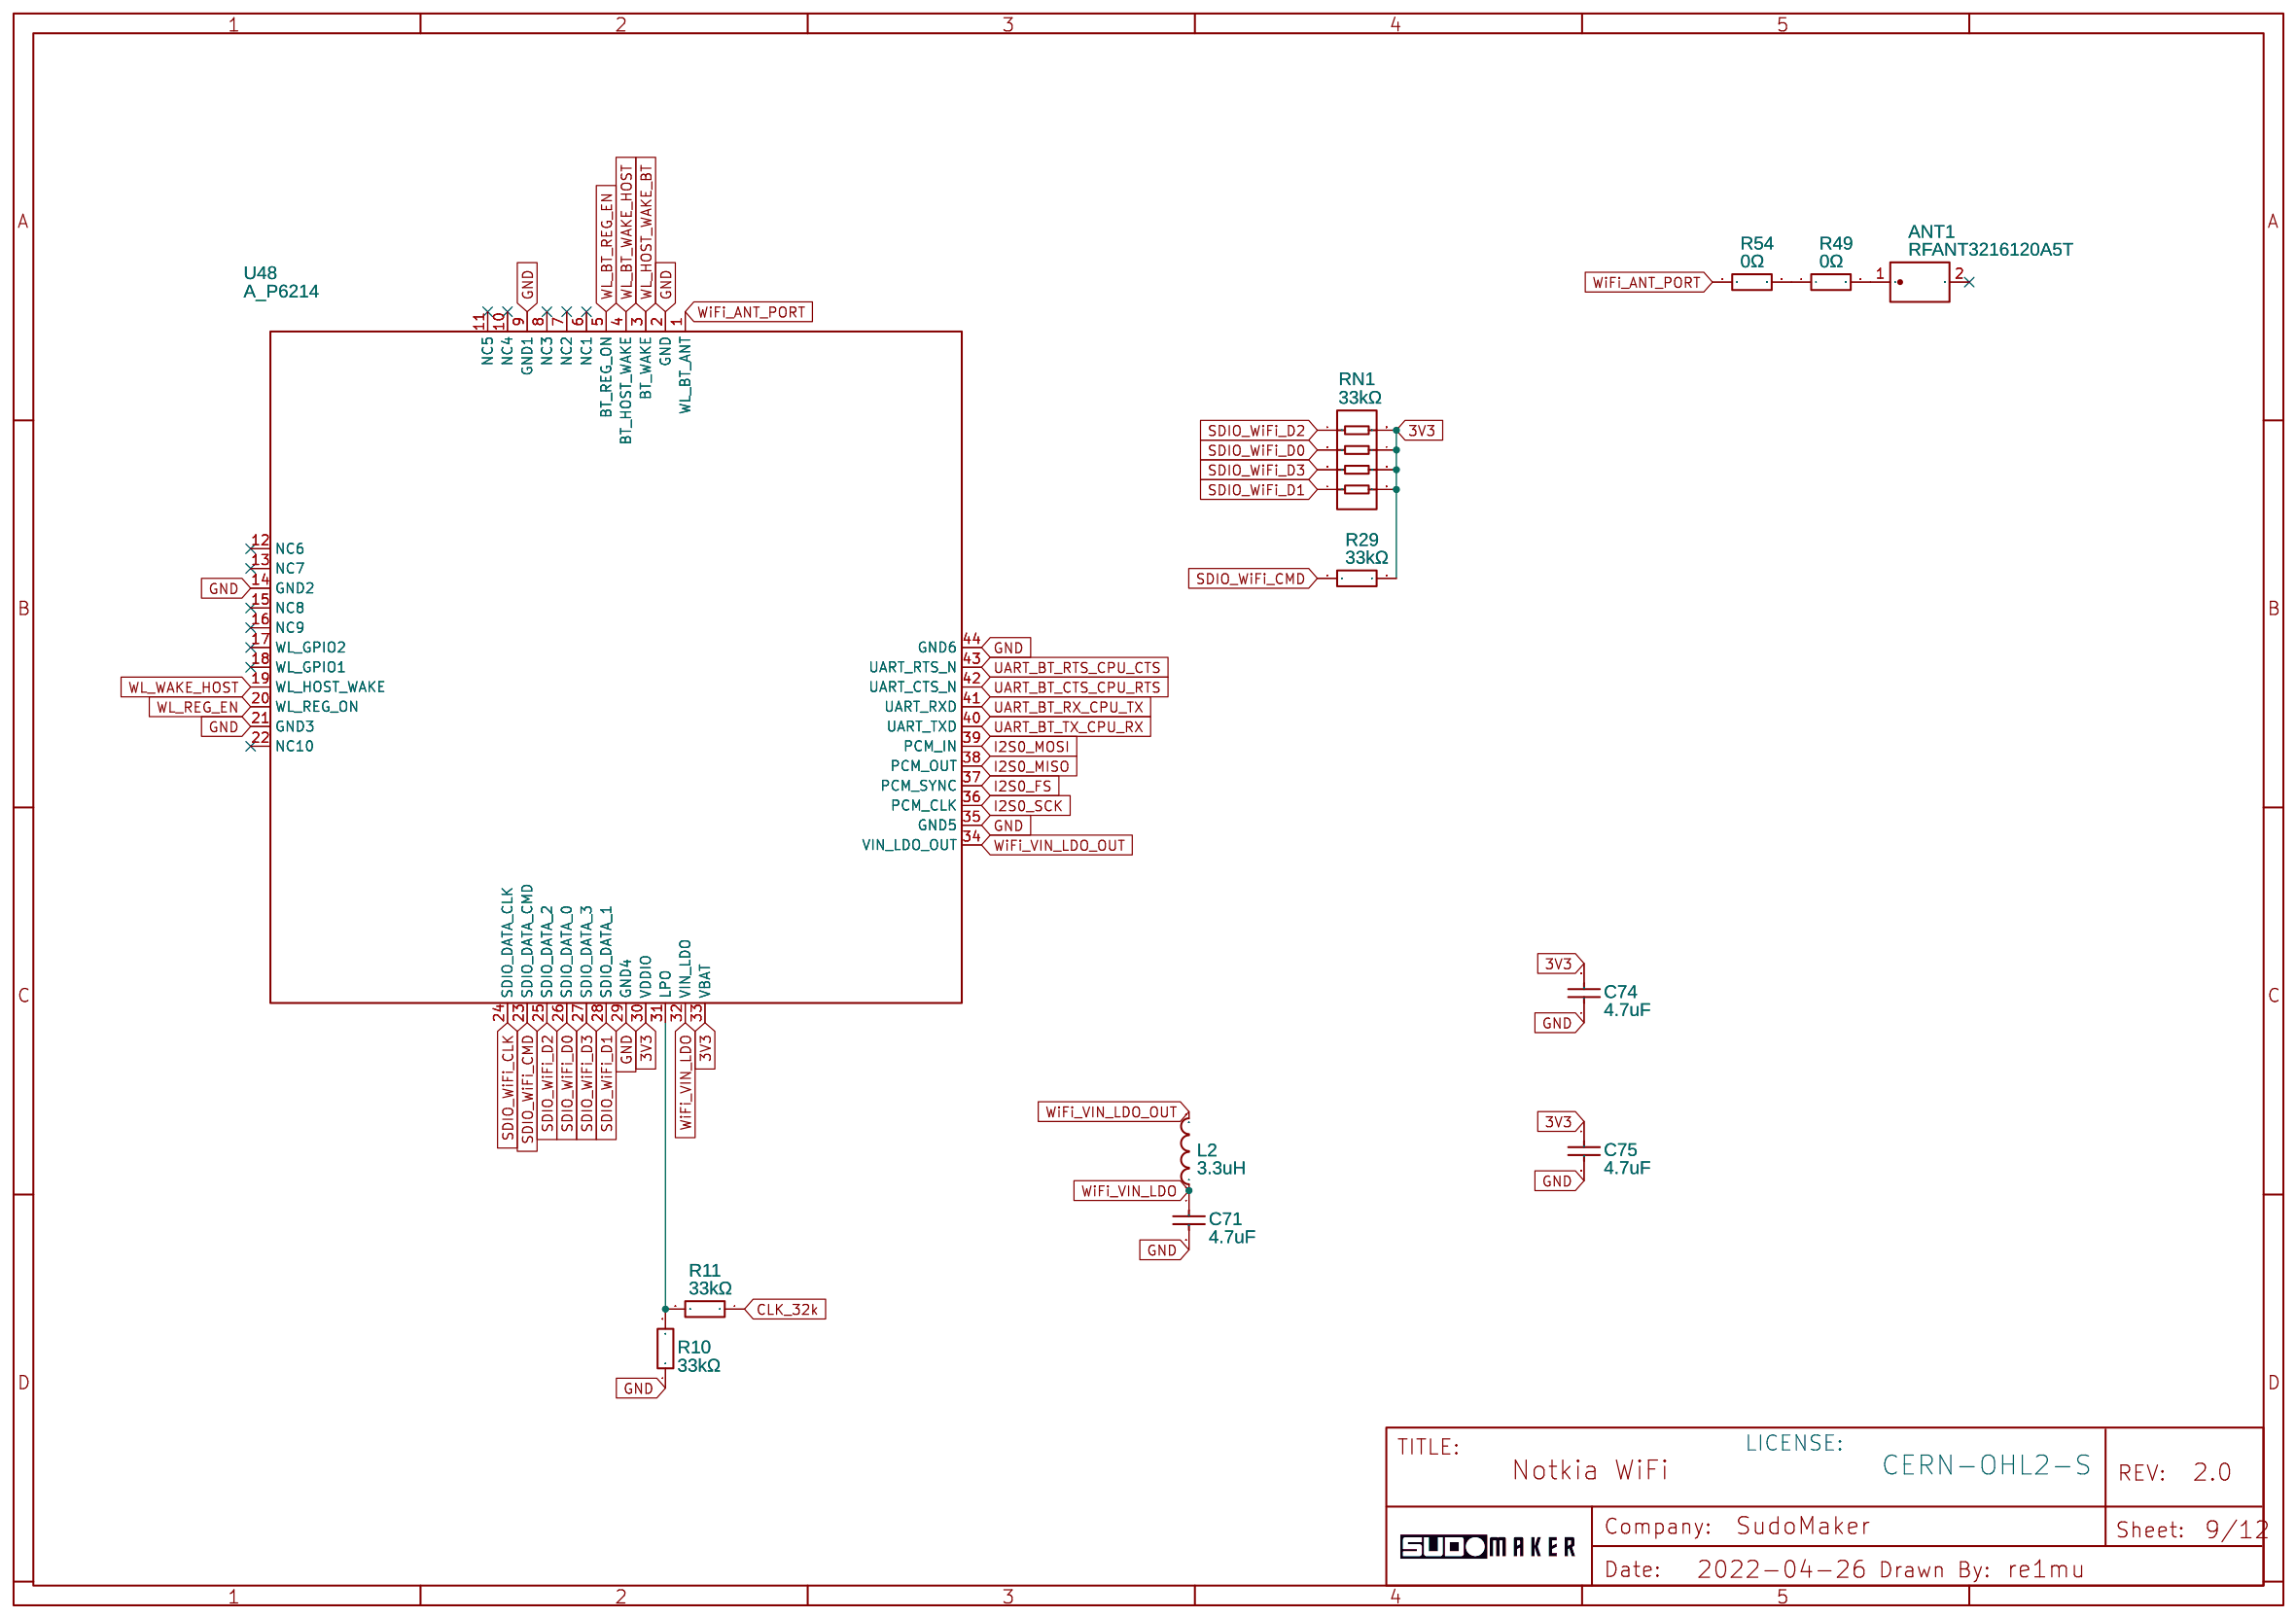
[diagram p7: W1F1]
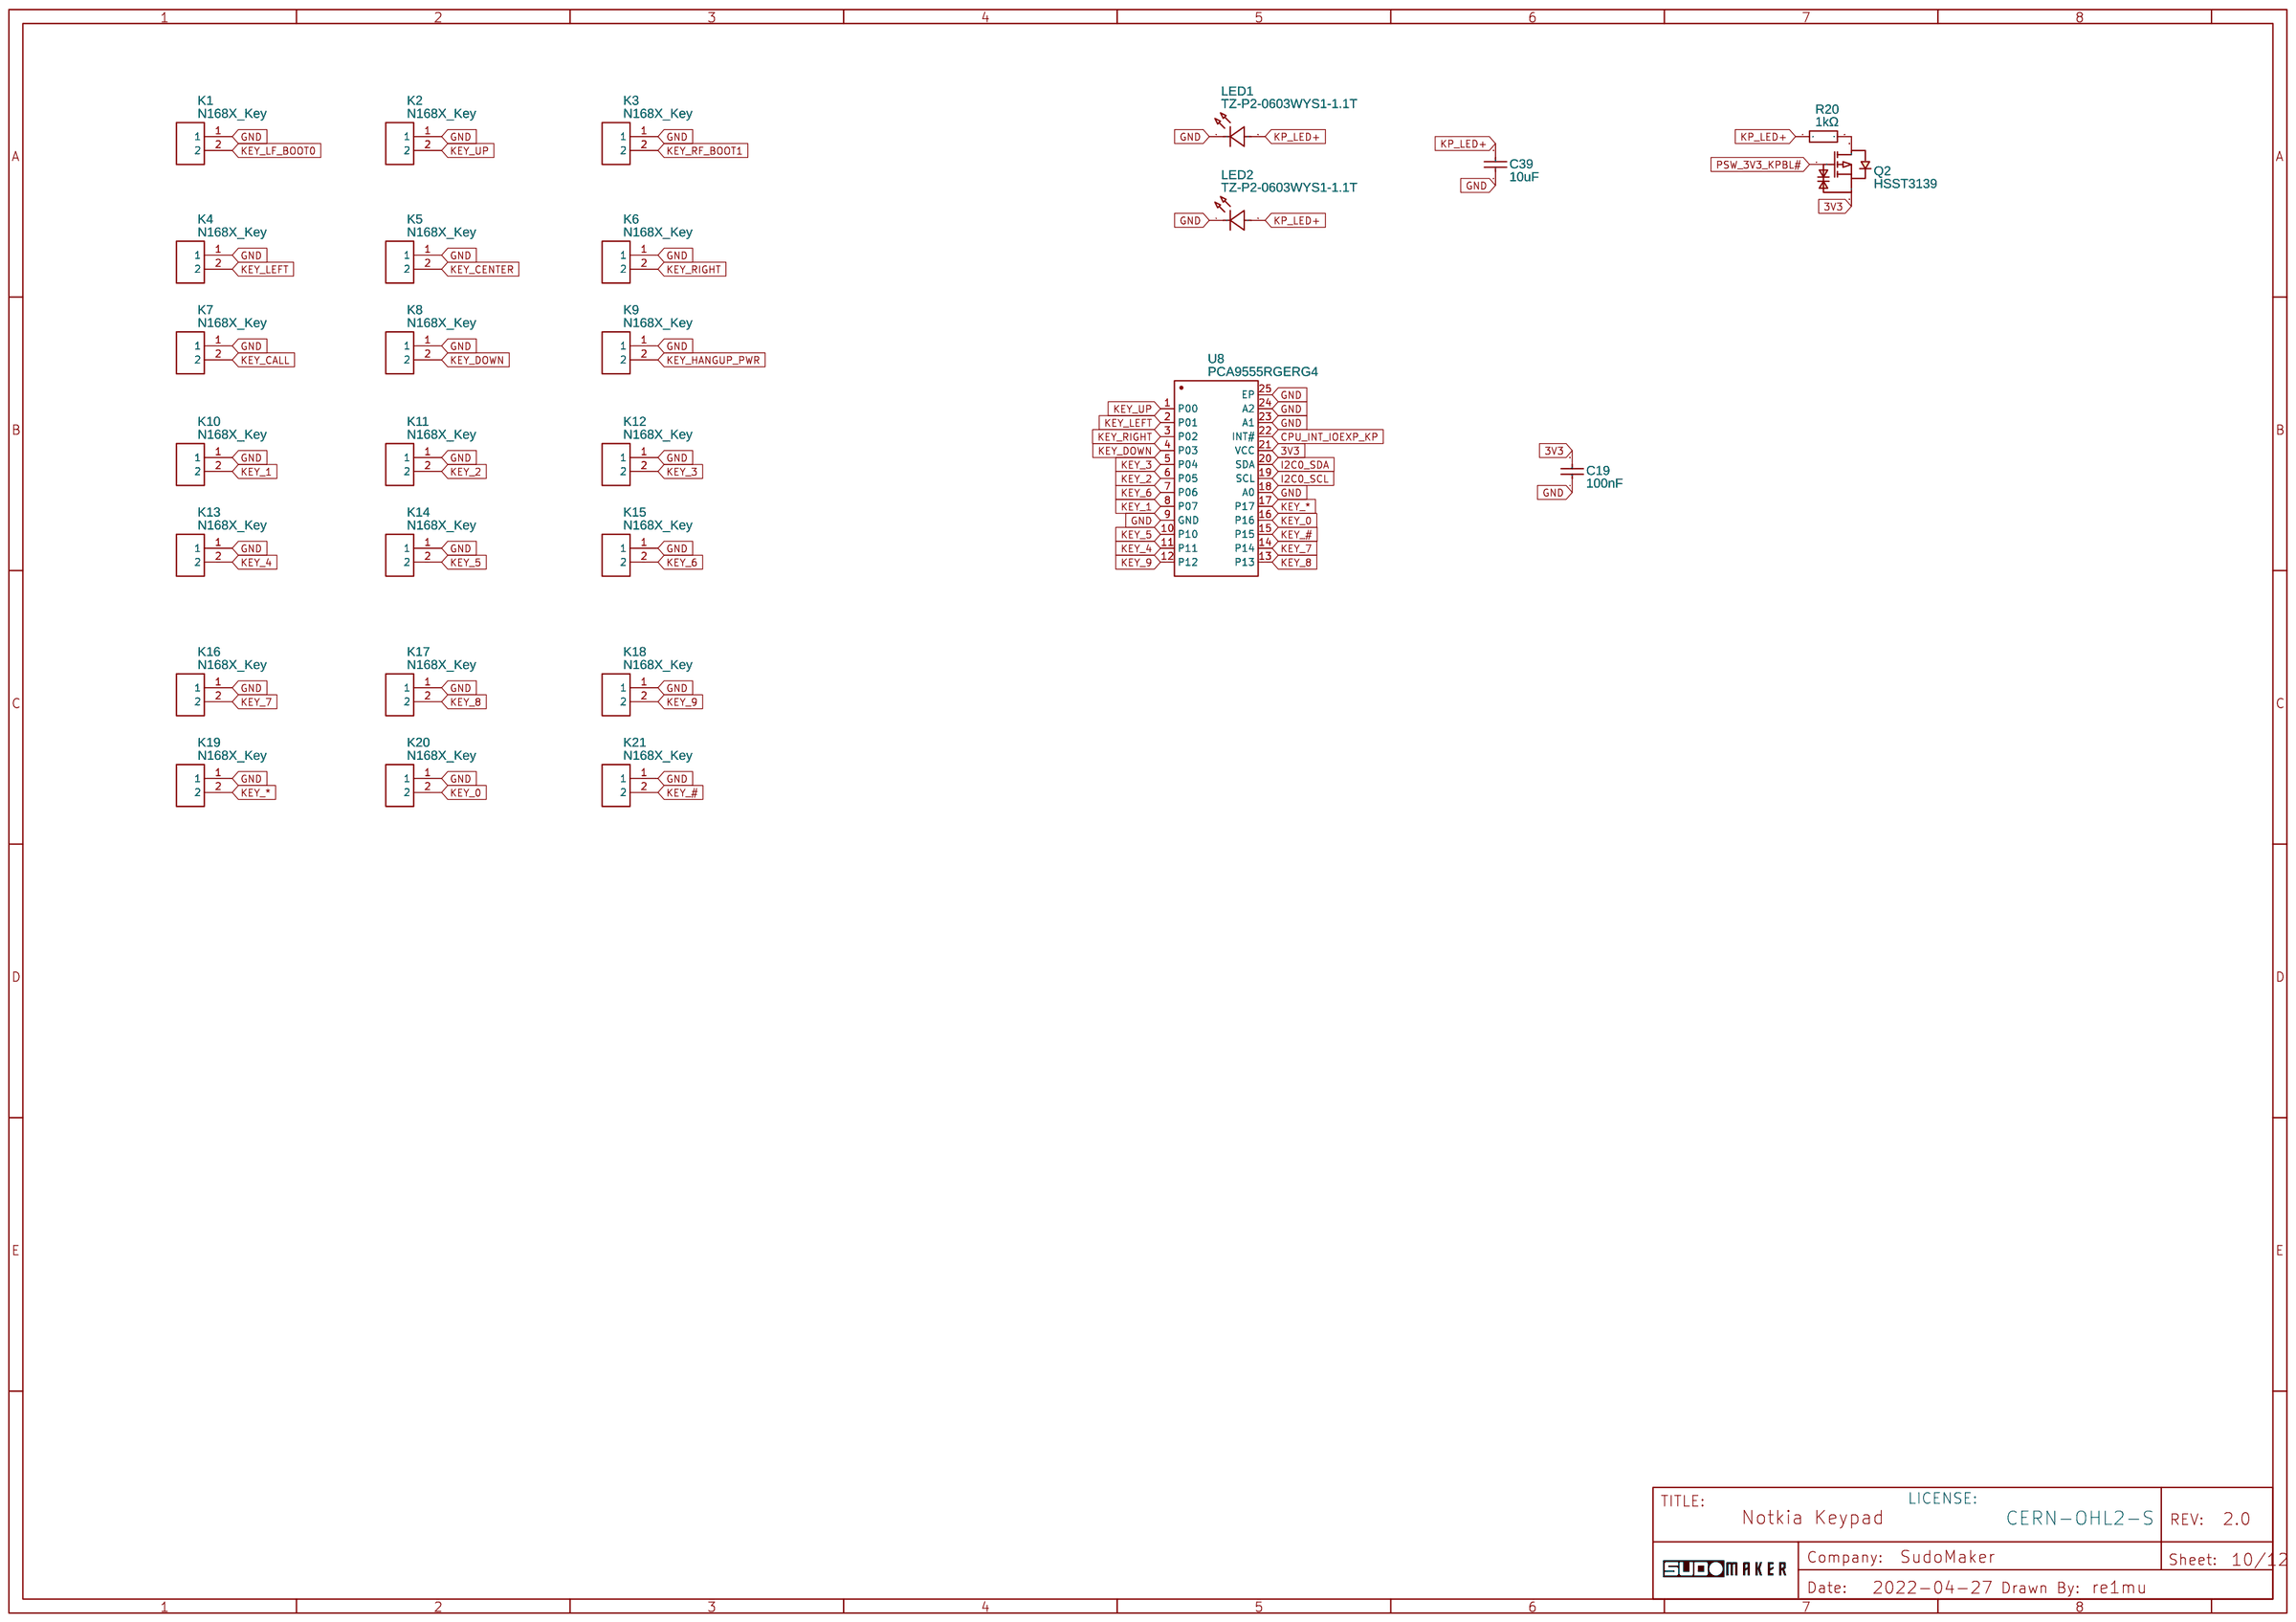
[diagram p8: Keypad]
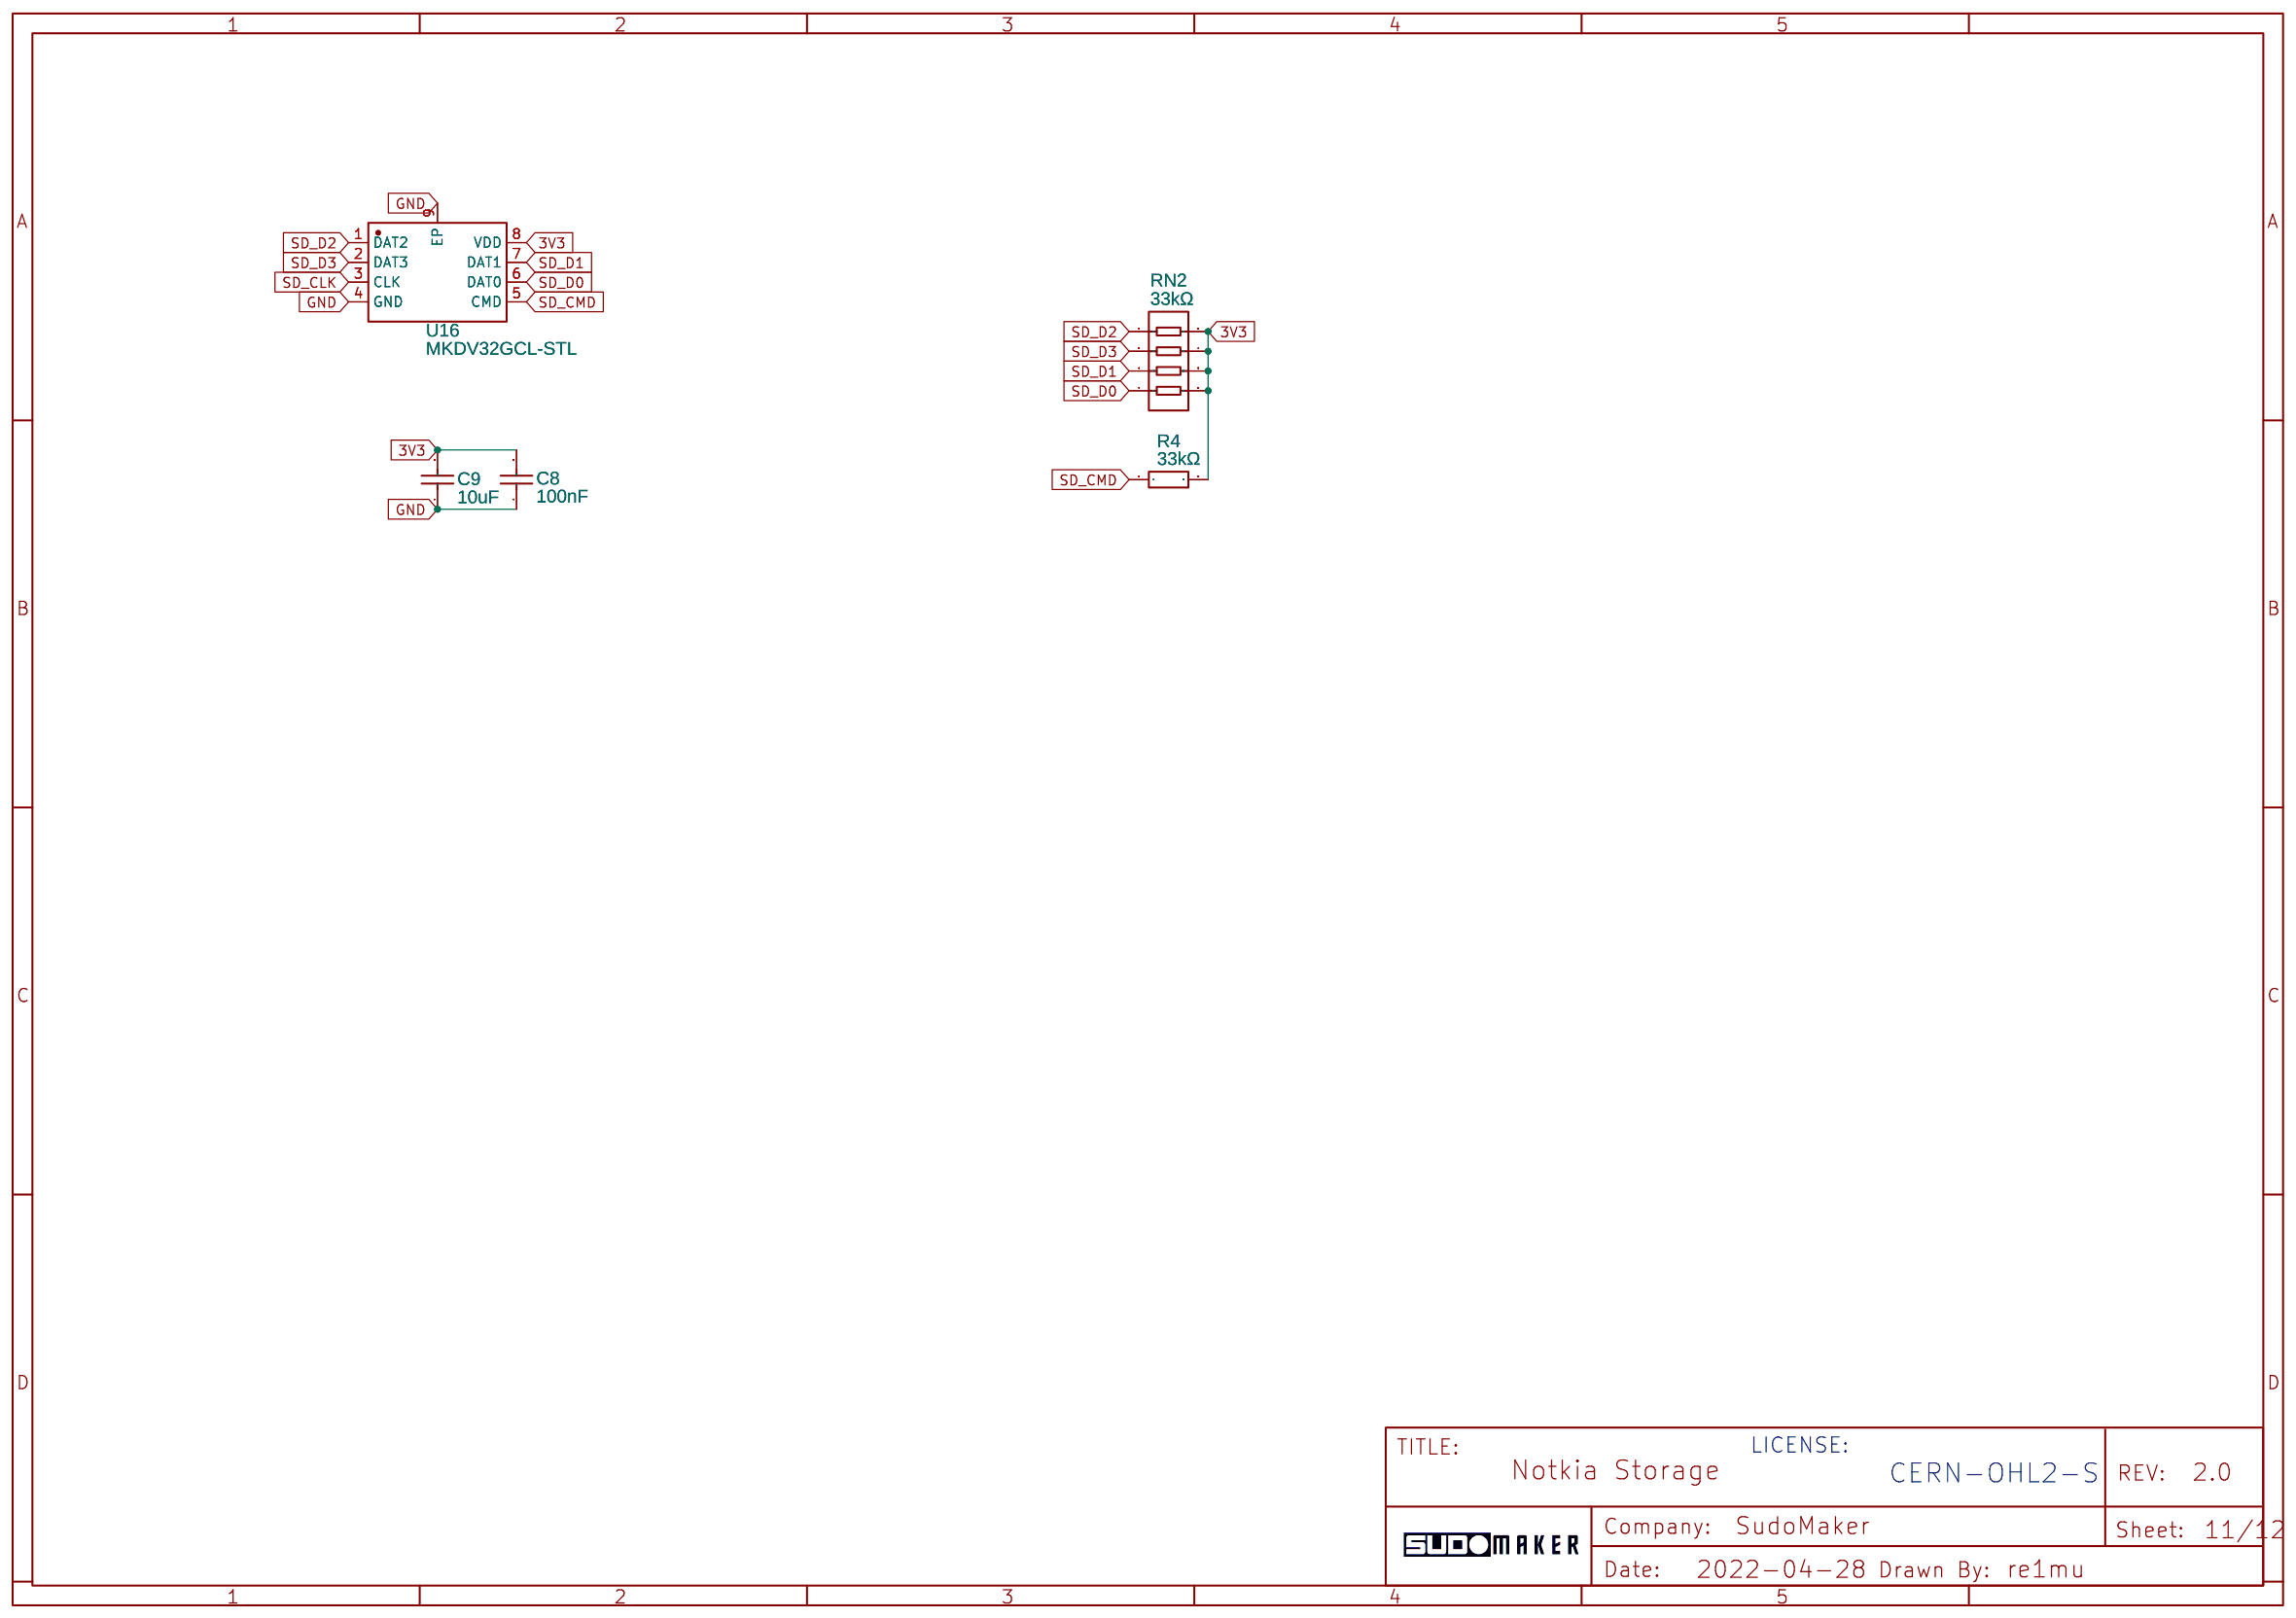
[diagram p9: Storage]
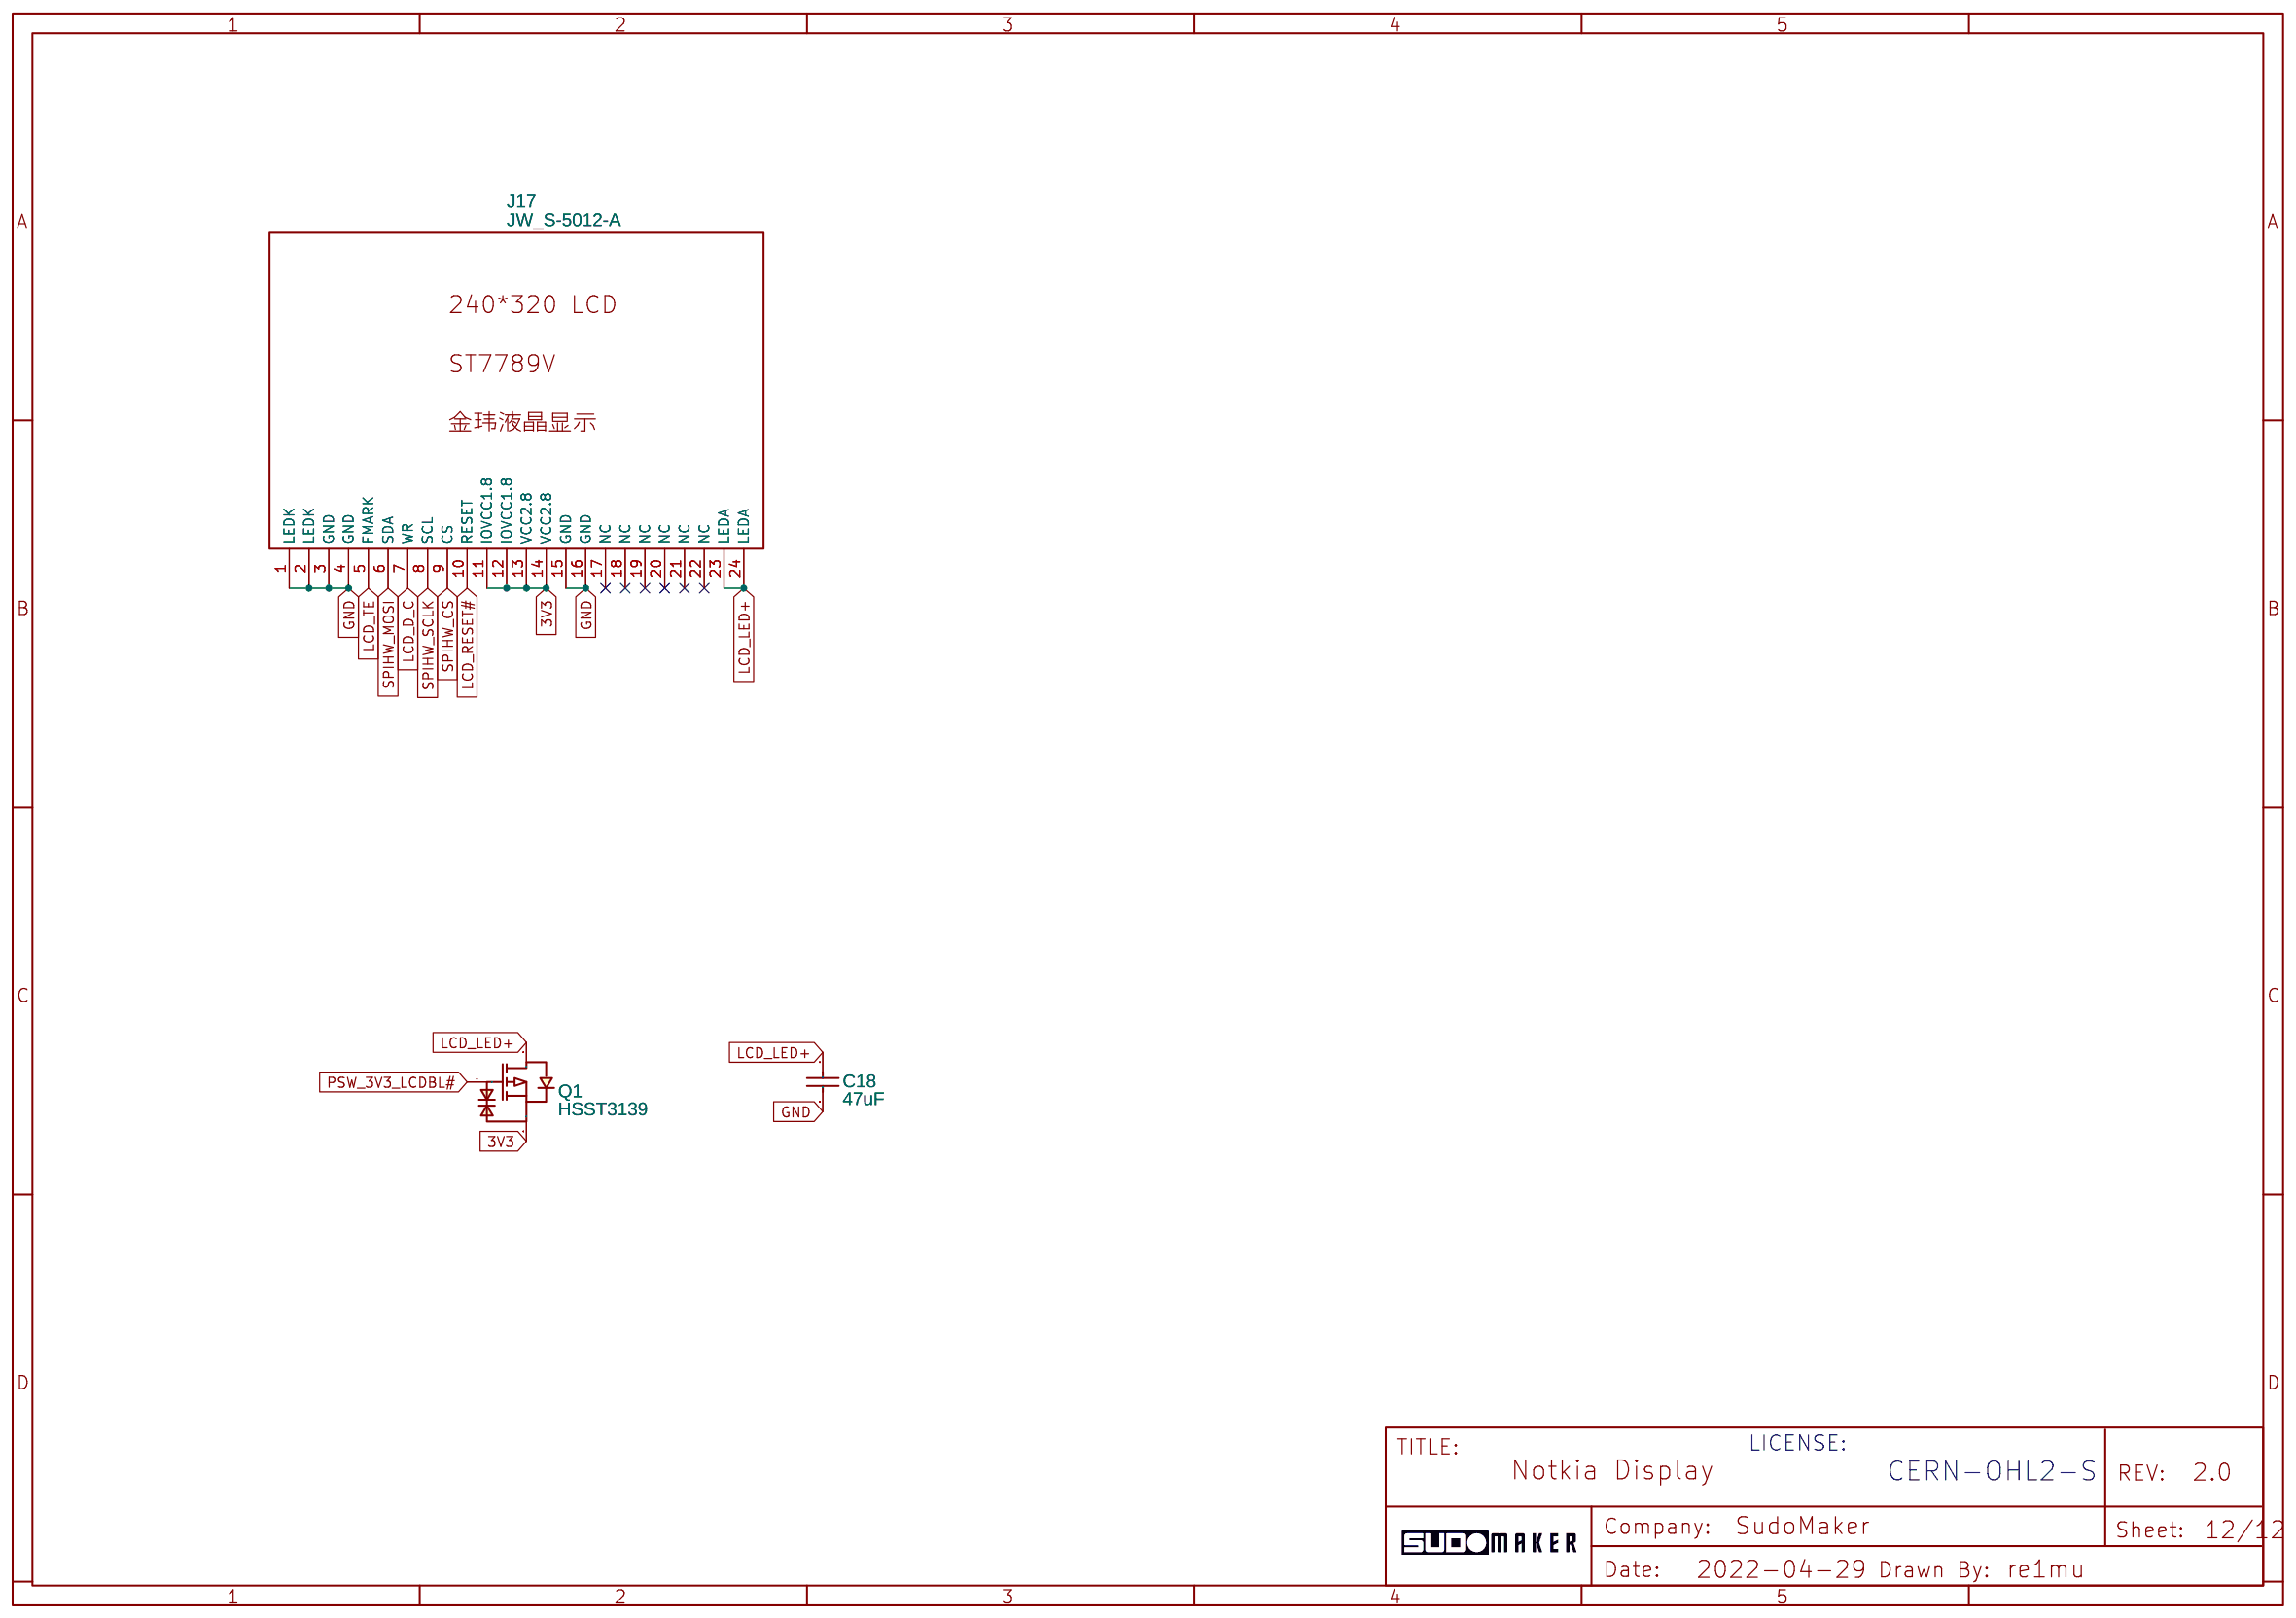
[diagram p10: Display]
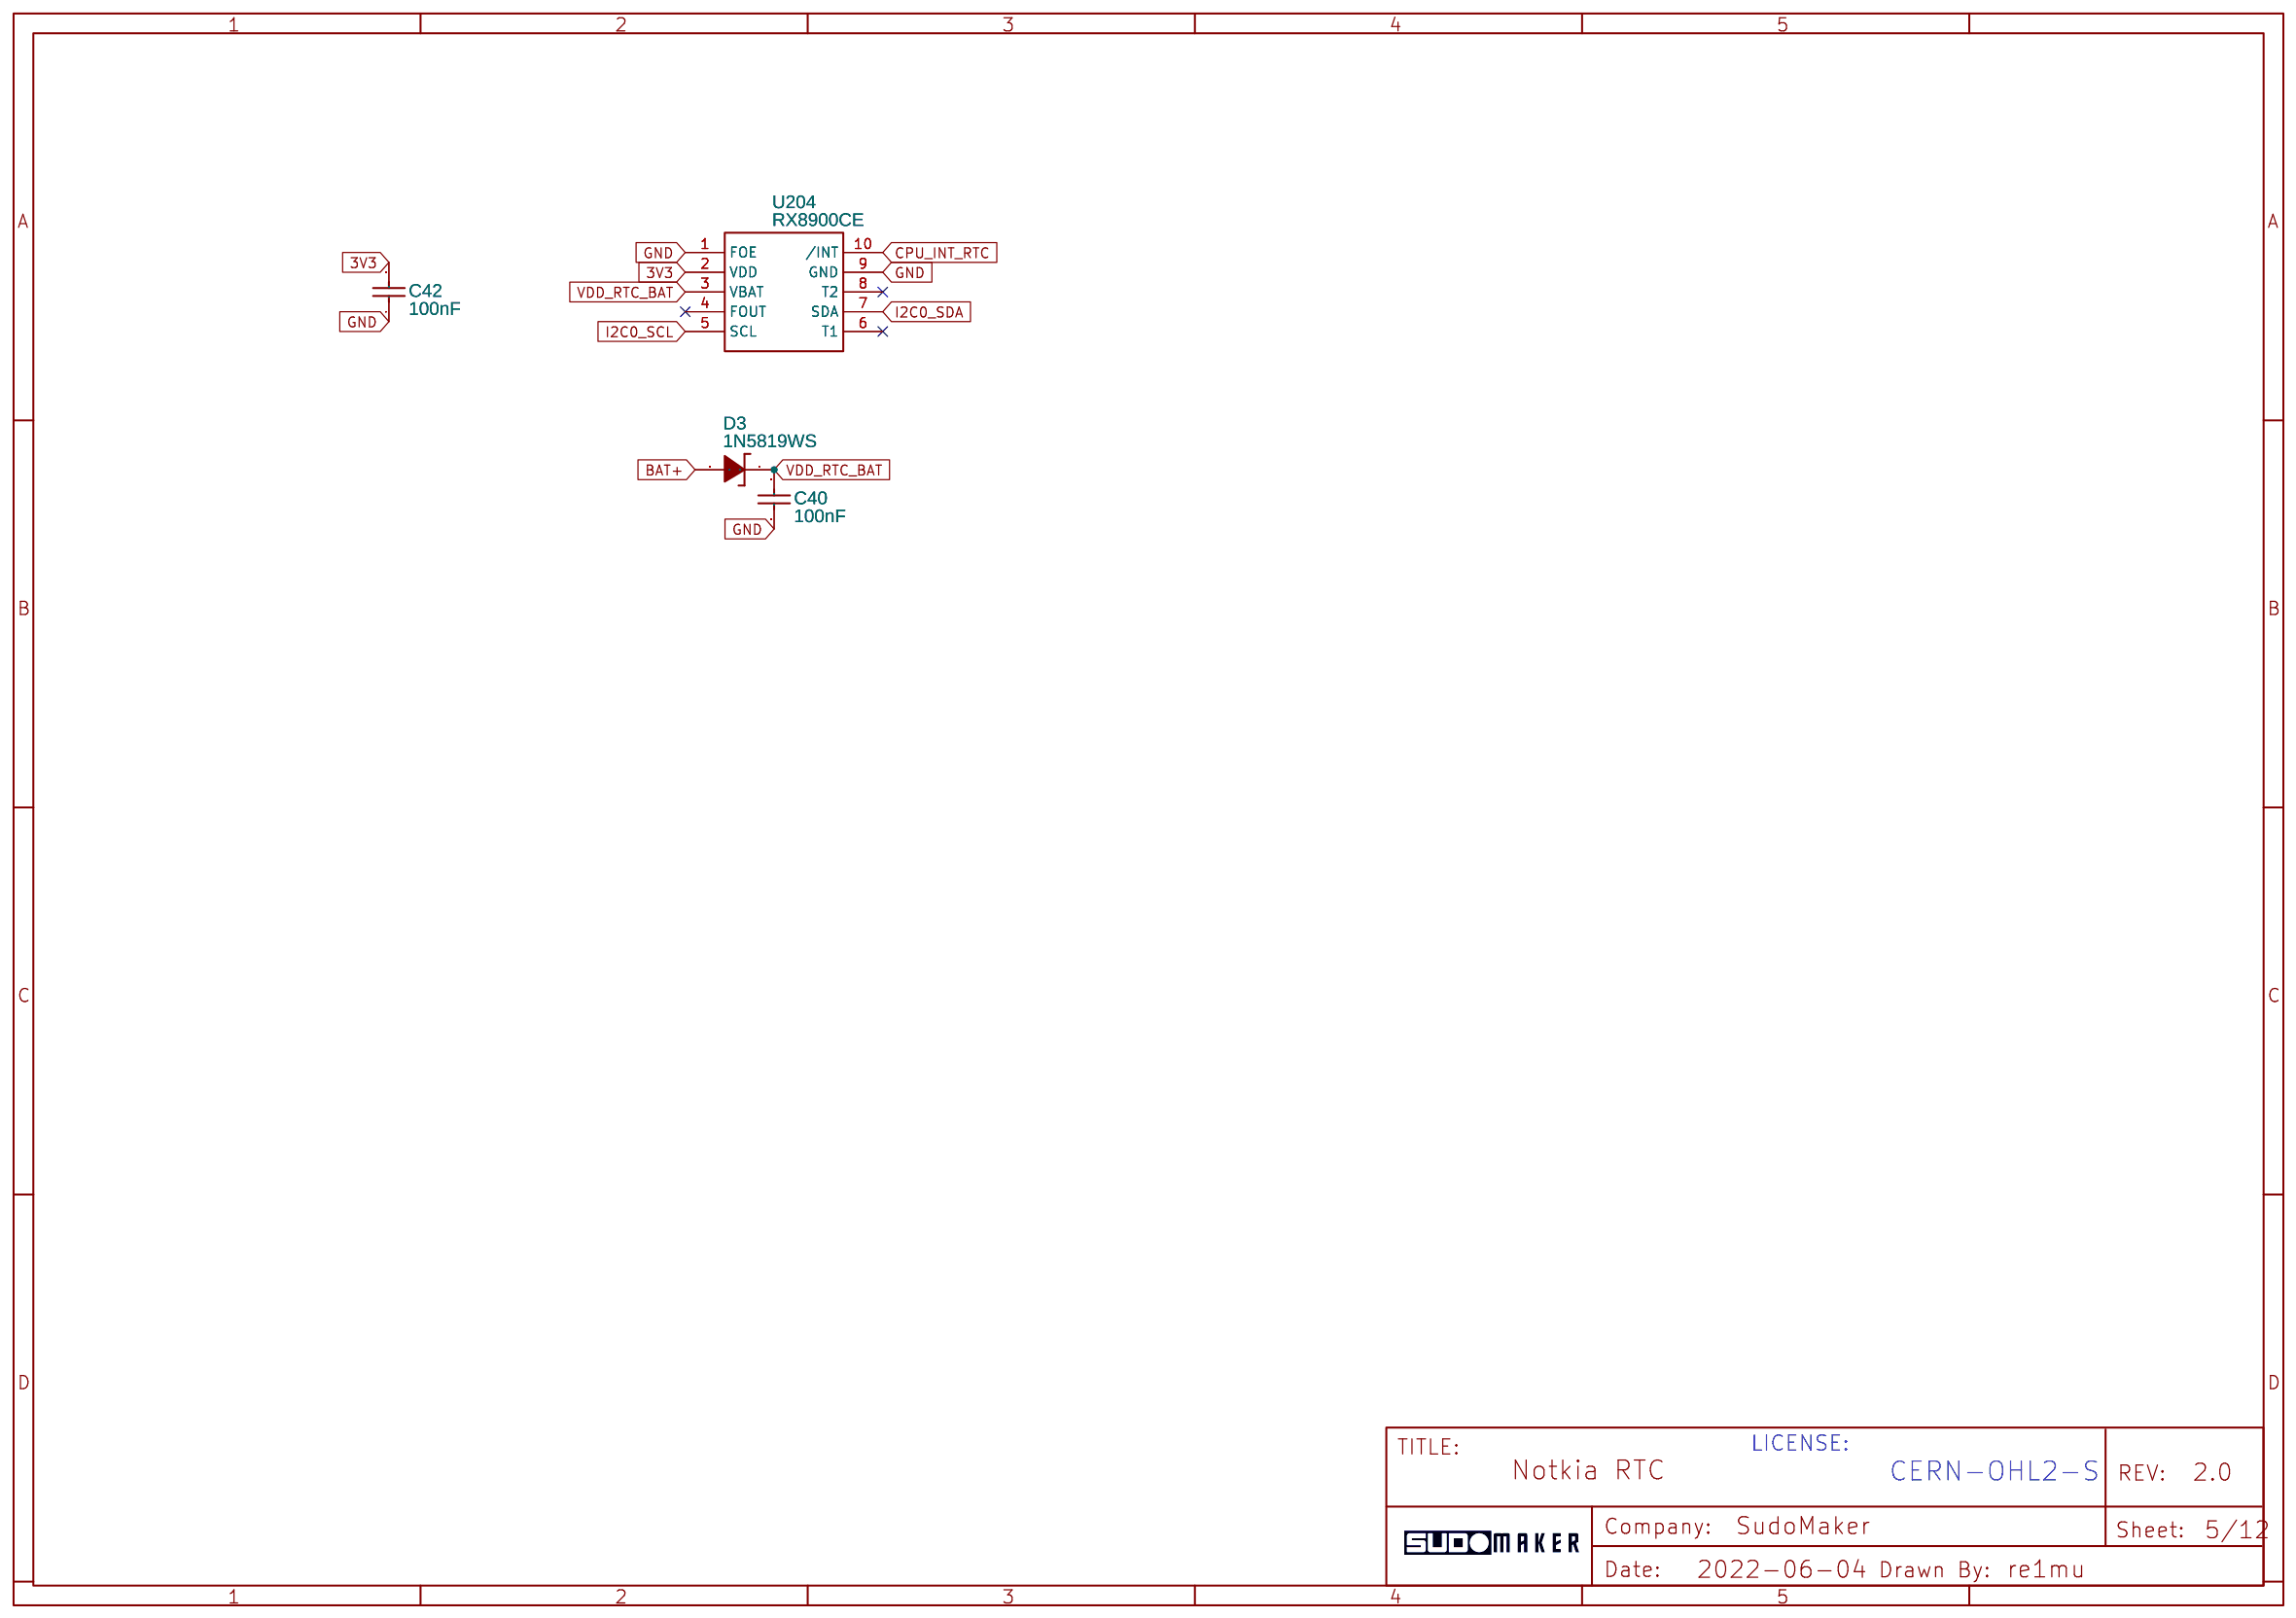
[diagram p11: RTC]

(export (version "E")
  (design (tool "Eeschema 10.0.6"))
  (components
    (comp (ref "C11")
      (value "47uF")
      (fields
        (field (name "BOM_Manufacturer Part") "CL21A476MQYNNNE")
        (field (name "BOM_Supplier Part") "C16780")
      )
      (libsource (lib "") (part "CL21A476MQYNNNE"))
    )
    (comp (ref "C14")
      (value "100nF")
      (fields
        (field (name "BOM_Manufacturer Part") "CL05B104KO5NNNC")
        (field (name "BOM_Supplier Part") "C1525")
      )
      (libsource (lib "") (part "CL05B104KO5NNNC"))
    )
    (comp (ref "FPC1")
      (value "FH34SRJ-12S-0.5SH(50)")
      (fields (field (name "BOM_Supplier Part") "C424659"))
      (libsource (lib "") (part "FH34SRJ-12S-0.5SH(50)"))
    )
    (comp (ref "Q3") (value "TP") (libsource (lib "") (part "TP")))
    (comp (ref "Q4") (value "TP") (libsource (lib "") (part "TP")))
    (comp (ref "Q5") (value "TP") (libsource (lib "") (part "TP")))
    (comp (ref "R1")
      (value "2.2K")
      (fields
        (field (name "BOM_Manufacturer Part") "0402WGF2201TCE")
        (field (name "BOM_Supplier Part") "C25879")
      )
      (libsource (lib "") (part "0402WGF2201TCE"))
    )
    (comp (ref "R2")
      (value "2.2K")
      (fields
        (field (name "BOM_Manufacturer Part") "0402WGF2201TCE")
        (field (name "BOM_Supplier Part") "C25879")
      )
      (libsource (lib "") (part "0402WGF2201TCE"))
    )
    (comp (ref "R3")
      (value "33kΩ")
      (fields
        (field (name "BOM_Manufacturer Part") "0402WGF3302TCE")
        (field (name "BOM_Supplier Part") "C25779")
      )
      (libsource (lib "") (part "0402WGF3302TCE"))
    )
    (comp (ref "R8")
      (value "33kΩ")
      (fields
        (field (name "BOM_Manufacturer Part") "0402WGF3302TCE")
        (field (name "BOM_Supplier Part") "C25779")
      )
      (libsource (lib "") (part "0402WGF3302TCE_1"))
    )
    (comp (ref "R12")
      (value "2.2K")
      (fields
        (field (name "BOM_Manufacturer Part") "0402WGF2201TCE")
        (field (name "BOM_Supplier Part") "C25879")
      )
      (libsource (lib "") (part "0402WGF2201TCE"))
    )
    (comp (ref "R13")
      (value "2.2K")
      (fields
        (field (name "BOM_Manufacturer Part") "0402WGF2201TCE")
        (field (name "BOM_Supplier Part") "C25879")
      )
      (libsource (lib "") (part "0402WGF2201TCE"))
    )
    (comp (ref "RN3")
      (value "33kΩ")
      (fields
        (field (name "BOM_Manufacturer Part") "WA04X333JTL")
        (field (name "BOM_Supplier Part") "C431861")
      )
      (libsource (lib "") (part "WA04X333JTL"))
    )
    (comp (ref "SW1")
      (value "1TS026A-1800-0553-CT")
      (fields (field (name "BOM_Supplier Part") "C913786"))
      (libsource (lib "") (part "1TS026A-1800-0553-CT"))
    )
    (comp (ref "U1") (value "X1000_Nano") (libsource (lib "") (part "X1000_Nano")))
    (comp (ref "U2")
      (value "PCA9555RGERG4")
      (fields (field (name "BOM_Supplier Part") "C2669780"))
      (libsource (lib "") (part "PCA9555RGERG4"))
    )
    (comp (ref "C15")
      (value "1uF")
      (fields
        (field (name "BOM_Manufacturer Part") "CL05A105KA5NQNC")
        (field (name "BOM_Supplier Part") "C52923")
      )
      (libsource (lib "") (part "CL05A105KA5NQNC"))
    )
    (comp (ref "C28")
      (value "1uF")
      (fields
        (field (name "BOM_Manufacturer Part") "CL05A105KA5NQNC")
        (field (name "BOM_Supplier Part") "C52923")
      )
      (libsource (lib "") (part "CL05A105KA5NQNC"))
    )
    (comp (ref "C32")
      (value "1uF")
      (fields
        (field (name "BOM_Manufacturer Part") "CL05A105KA5NQNC")
        (field (name "BOM_Supplier Part") "C52923")
      )
      (libsource (lib "") (part "CL05A105KA5NQNC"))
    )
    (comp (ref "CONN1")
      (value "FH34SRJ-24S-0.5SH(50)")
      (fields (field (name "BOM_Supplier Part") "C324726"))
      (libsource (lib "") (part "FH34SRJ-24S-0.5SH(50)"))
    )
    (comp (ref "U33")
      (value "VRD1528MTX")
      (fields (field (name "BOM_Supplier Part") "C697914"))
      (libsource (lib "") (part "VRD1528MTX"))
    )
    (comp (ref "C10")
      (value "100nF")
      (fields
        (field (name "BOM_Manufacturer Part") "CL05B104KO5NNNC")
        (field (name "BOM_Supplier Part") "C1525")
      )
      (libsource (lib "") (part "CL05B104KO5NNNC"))
    )
    (comp (ref "C16")
      (value "1uF")
      (fields
        (field (name "BOM_Manufacturer Part") "CL05A105KA5NQNC")
        (field (name "BOM_Supplier Part") "C52923")
      )
      (libsource (lib "") (part "CL05A105KA5NQNC"))
    )
    (comp (ref "LED16")
      (value "MHS110FRGBCT")
      (fields (field (name "BOM_Supplier Part") "C496820"))
      (libsource (lib "") (part "MHS110FRGBCT"))
    )
    (comp (ref "U3")
      (value "WD3153D-10/TR")
      (fields (field (name "BOM_Supplier Part") "C506151"))
      (libsource (lib "") (part "WD3153D-10/TR"))
    )
    (comp (ref "U135")
      (value "FUSB301TMX")
      (fields (field (name "BOM_Supplier Part") "C132290"))
      (libsource (lib "") (part "FUSB301TMX"))
    )
    (comp (ref "USB1")
      (value "TYPE-611S-T3")
      (fields (field (name "BOM_Supplier Part") "C2874595"))
      (libsource (lib "") (part "TYPE-611S-T3"))
    )
    (comp (ref "C4")
      (value "100nF")
      (fields
        (field (name "BOM_Manufacturer Part") "CL05B104KO5NNNC")
        (field (name "BOM_Supplier Part") "C1525")
      )
      (libsource (lib "") (part "CL05B104KO5NNNC"))
    )
    (comp (ref "C5")
      (value "1uF")
      (fields
        (field (name "BOM_Manufacturer Part") "CL05A105KA5NQNC")
        (field (name "BOM_Supplier Part") "C52923")
      )
      (libsource (lib "") (part "CL05A105KA5NQNC"))
    )
    (comp (ref "C6")
      (value "1uF")
      (fields
        (field (name "BOM_Manufacturer Part") "CL05A105KA5NQNC")
        (field (name "BOM_Supplier Part") "C52923")
      )
      (libsource (lib "") (part "CL05A105KA5NQNC"))
    )
    (comp (ref "C7")
      (value "1uF")
      (fields
        (field (name "BOM_Manufacturer Part") "CL05A105KA5NQNC")
        (field (name "BOM_Supplier Part") "C52923")
      )
      (libsource (lib "") (part "CL05A105KA5NQNC"))
    )
    (comp (ref "C21")
      (value "1uF")
      (fields
        (field (name "BOM_Manufacturer Part") "CL05A105KA5NQNC")
        (field (name "BOM_Supplier Part") "C52923")
      )
      (libsource (lib "") (part "CL05A105KA5NQNC_2"))
    )
    (comp (ref "C22")
      (value "1uF")
      (fields
        (field (name "BOM_Manufacturer Part") "CL05A105KA5NQNC")
        (field (name "BOM_Supplier Part") "C52923")
      )
      (libsource (lib "") (part "CL05A105KA5NQNC_1"))
    )
    (comp (ref "C23")
      (value "1uF")
      (fields
        (field (name "BOM_Manufacturer Part") "CL05A105KA5NQNC")
        (field (name "BOM_Supplier Part") "C52923")
      )
      (libsource (lib "") (part "CL05A105KA5NQNC"))
    )
    (comp (ref "C24")
      (value "4.7uF")
      (fields
        (field (name "BOM_Manufacturer Part") "CL05A475MP5NRNC")
        (field (name "BOM_Supplier Part") "C23733")
      )
      (libsource (lib "") (part "CL05A475MP5NRNC"))
    )
    (comp (ref "C25")
      (value "4.7uF")
      (fields
        (field (name "BOM_Manufacturer Part") "CL05A475MP5NRNC")
        (field (name "BOM_Supplier Part") "C23733")
      )
      (libsource (lib "") (part "CL05A475MP5NRNC"))
    )
    (comp (ref "C26")
      (value "1uF")
      (fields
        (field (name "BOM_Manufacturer Part") "CL05A105KA5NQNC")
        (field (name "BOM_Supplier Part") "C52923")
      )
      (libsource (lib "") (part "CL05A105KA5NQNC_1"))
    )
    (comp (ref "C27")
      (value "1uF")
      (fields
        (field (name "BOM_Manufacturer Part") "CL05A105KA5NQNC")
        (field (name "BOM_Supplier Part") "C52923")
      )
      (libsource (lib "") (part "CL05A105KA5NQNC_2"))
    )
    (comp (ref "C29")
      (value "100nF")
      (fields
        (field (name "BOM_Manufacturer Part") "CL05B104KO5NNNC")
        (field (name "BOM_Supplier Part") "C1525")
      )
      (libsource (lib "") (part "CL05B104KO5NNNC"))
    )
    (comp (ref "C30")
      (value "100nF")
      (fields
        (field (name "BOM_Manufacturer Part") "CL05B104KO5NNNC")
        (field (name "BOM_Supplier Part") "C1525")
      )
      (libsource (lib "") (part "CL05B104KO5NNNC_1"))
    )
    (comp (ref "C31")
      (value "1nF")
      (fields
        (field (name "BOM_Manufacturer Part") "0402B102K500NT")
        (field (name "BOM_Supplier Part") "C1523")
      )
      (libsource (lib "") (part "0402B102K500NT"))
    )
    (comp (ref "C35")
      (value "4.7uF")
      (fields
        (field (name "BOM_Manufacturer Part") "CL05A475MP5NRNC")
        (field (name "BOM_Supplier Part") "C23733")
      )
      (libsource (lib "") (part "CL05A475MP5NRNC_1"))
    )
    (comp (ref "C36")
      (value "100nF")
      (fields
        (field (name "BOM_Manufacturer Part") "CL05B104KO5NNNC")
        (field (name "BOM_Supplier Part") "C1525")
      )
      (libsource (lib "") (part "CL05B104KO5NNNC"))
    )
    (comp (ref "C37")
      (value "4.7uF")
      (fields
        (field (name "BOM_Manufacturer Part") "CL05A475MP5NRNC")
        (field (name "BOM_Supplier Part") "C23733")
      )
      (libsource (lib "") (part "CL05A475MP5NRNC_1"))
    )
    (comp (ref "C38")
      (value "100nF")
      (fields
        (field (name "BOM_Manufacturer Part") "CL05B104KO5NNNC")
        (field (name "BOM_Supplier Part") "C1525")
      )
      (libsource (lib "") (part "CL05B104KO5NNNC"))
    )
    (comp (ref "C59")
      (value "4.7uF")
      (fields
        (field (name "BOM_Manufacturer Part") "CL05A475MP5NRNC")
        (field (name "BOM_Supplier Part") "C23733")
      )
      (libsource (lib "") (part "CL05A475MP5NRNC"))
    )
    (comp (ref "C60")
      (value "4.7uF")
      (fields
        (field (name "BOM_Manufacturer Part") "CL05A475MP5NRNC")
        (field (name "BOM_Supplier Part") "C23733")
      )
      (libsource (lib "") (part "CL05A475MP5NRNC"))
    )
    (comp (ref "C62")
      (value "4.7uF")
      (fields
        (field (name "BOM_Manufacturer Part") "CL05A475MP5NRNC")
        (field (name "BOM_Supplier Part") "C23733")
      )
      (libsource (lib "") (part "CL05A475MP5NRNC"))
    )
    (comp (ref "C64")
      (value "4.7uF")
      (fields
        (field (name "BOM_Manufacturer Part") "CL05A475MP5NRNC")
        (field (name "BOM_Supplier Part") "C23733")
      )
      (libsource (lib "") (part "CL05A475MP5NRNC"))
    )
    (comp (ref "C65")
      (value "4.7uF")
      (fields
        (field (name "BOM_Manufacturer Part") "CL05A475MP5NRNC")
        (field (name "BOM_Supplier Part") "C23733")
      )
      (libsource (lib "") (part "CL05A475MP5NRNC"))
    )
    (comp (ref "C66")
      (value "4.7uF")
      (fields
        (field (name "BOM_Manufacturer Part") "CL05A475MP5NRNC")
        (field (name "BOM_Supplier Part") "C23733")
      )
      (libsource (lib "") (part "CL05A475MP5NRNC"))
    )
    (comp (ref "J1") (value "N126x_EAR") (libsource (lib "") (part "N126x_EAR")))
    (comp (ref "J2") (value "N126x_EAR") (libsource (lib "") (part "N126x_EAR")))
    (comp (ref "MIC1")
      (value "WMM7037AT2")
      (fields (field (name "BOM_Supplier Part") "C140705"))
      (libsource (lib "") (part "WMM7037AT2"))
    )
    (comp (ref "R14")
      (value "20kΩ")
      (fields
        (field (name "BOM_Manufacturer Part") "0402WGF2002TCE")
        (field (name "BOM_Supplier Part") "C25765")
      )
      (libsource (lib "") (part "0402WGF2002TCE_1"))
    )
    (comp (ref "R15")
      (value "20kΩ")
      (fields
        (field (name "BOM_Manufacturer Part") "0402WGF2002TCE")
        (field (name "BOM_Supplier Part") "C25765")
      )
      (libsource (lib "") (part "0402WGF2002TCE"))
    )
    (comp (ref "R16")
      (value "20kΩ")
      (fields
        (field (name "BOM_Manufacturer Part") "0402WGF2002TCE")
        (field (name "BOM_Supplier Part") "C25765")
      )
      (libsource (lib "") (part "0402WGF2002TCE_1"))
    )
    (comp (ref "R17")
      (value "20kΩ")
      (fields
        (field (name "BOM_Manufacturer Part") "0402WGF2002TCE")
        (field (name "BOM_Supplier Part") "C25765")
      )
      (libsource (lib "") (part "0402WGF2002TCE"))
    )
    (comp (ref "R19")
      (value "3.3K")
      (fields
        (field (name "BOM_Manufacturer Part") "0402WGF3301TCE")
        (field (name "BOM_Supplier Part") "C25890")
      )
      (libsource (lib "") (part "0402WGF3301TCE"))
    )
    (comp (ref "U128")
      (value "NAU88C22YG")
      (fields (field (name "BOM_Supplier Part") "C100123"))
      (libsource (lib "") (part "NAU88C22YG"))
    )
    (comp (ref "U129")
      (value "BCT8890ELA-TR")
      (fields (field (name "BOM_Supplier Part") "C2924400"))
      (libsource (lib "") (part "BCT8890ELA-TR"))
    )
    (comp (ref "U130")
      (value "BCT8890ELA-TR")
      (fields (field (name "BOM_Supplier Part") "C2924400"))
      (libsource (lib "") (part "BCT8890ELA-TR"))
    )
    (comp (ref "U140") (value "YMU762") (libsource (lib "") (part "YMU762")))
    (comp (ref "U141")
      (value "PCA9555RGERG4")
      (fields (field (name "BOM_Supplier Part") "C2669780"))
      (libsource (lib "") (part "PCA9555RGERG4"))
    )
    (comp (ref "X1")
      (value "12.288MHz")
      (fields
        (field (name "BOM_Manufacturer Part") "OT201624MJBA4SL")
        (field (name "BOM_Supplier Part") "C725986")
      )
      (libsource (lib "") (part "OT201624MJBA4SL"))
    )
    (comp (ref "C12")
      (value "100nF")
      (fields
        (field (name "BOM_Manufacturer Part") "CL05B104KO5NNNC")
        (field (name "BOM_Supplier Part") "C1525")
      )
      (libsource (lib "") (part "CL05B104KO5NNNC"))
    )
    (comp (ref "C13")
      (value "10uF")
      (fields
        (field (name "BOM_Manufacturer Part") "CL05A106MQ5NUNC")
        (field (name "BOM_Supplier Part") "C15525")
      )
      (libsource (lib "") (part "CL05A106MQ5NUNC"))
    )
    (comp (ref "U64") (value "HJ_LORA") (libsource (lib "") (part "HJ_LORA")))
    (comp (ref "ANT2")
      (value "GPS1003")
      (fields (field (name "BOM_Supplier Part") "C239243"))
      (libsource (lib "") (part "GPS1003"))
    )
    (comp (ref "C33")
      (value "47pF")
      (fields
        (field (name "BOM_Manufacturer Part") "0402CG470J500NT")
        (field (name "BOM_Supplier Part") "C1567")
      )
      (libsource (lib "") (part "0402CG470J500NT"))
    )
    (comp (ref "C41")
      (value "2.7pF")
      (fields
        (field (name "BOM_Manufacturer Part") "0402CG2R7C500NT")
        (field (name "BOM_Supplier Part") "C1561")
      )
      (libsource (lib "") (part "0402CG2R7C500NT"))
    )
    (comp (ref "C43")
      (value "1uF")
      (fields
        (field (name "BOM_Manufacturer Part") "CL05A105KA5NQNC")
        (field (name "BOM_Supplier Part") "C52923")
      )
      (libsource (lib "") (part "CL05A105KA5NQNC_1"))
    )
    (comp (ref "C44")
      (value "4.7uF")
      (fields
        (field (name "BOM_Manufacturer Part") "CL05A475MP5NRNC")
        (field (name "BOM_Supplier Part") "C23733")
      )
      (libsource (lib "") (part "CL05A475MP5NRNC"))
    )
    (comp (ref "C45")
      (value "2.2uF")
      (fields
        (field (name "BOM_Manufacturer Part") "CL05A225MQ5NSNC")
        (field (name "BOM_Supplier Part") "C12530")
      )
      (libsource (lib "") (part "CL05A225MQ5NSNC"))
    )
    (comp (ref "C46")
      (value "1uF")
      (fields
        (field (name "BOM_Manufacturer Part") "CL05A105KA5NQNC")
        (field (name "BOM_Supplier Part") "C52923")
      )
      (libsource (lib "") (part "CL05A105KA5NQNC"))
    )
    (comp (ref "C47")
      (value "1uF")
      (fields
        (field (name "BOM_Manufacturer Part") "CL05A105KA5NQNC")
        (field (name "BOM_Supplier Part") "C52923")
      )
      (libsource (lib "") (part "CL05A105KA5NQNC"))
    )
    (comp (ref "C48")
      (value "1uF")
      (fields
        (field (name "BOM_Manufacturer Part") "CL05A105KA5NQNC")
        (field (name "BOM_Supplier Part") "C52923")
      )
      (libsource (lib "") (part "CL05A105KA5NQNC"))
    )
    (comp (ref "C49")
      (value "4.7uF")
      (fields
        (field (name "BOM_Manufacturer Part") "CL05A475MP5NRNC")
        (field (name "BOM_Supplier Part") "C23733")
      )
      (libsource (lib "") (part "CL05A475MP5NRNC_1"))
    )
    (comp (ref "C50")
      (value "1uF")
      (fields
        (field (name "BOM_Manufacturer Part") "CL05A105KA5NQNC")
        (field (name "BOM_Supplier Part") "C52923")
      )
      (libsource (lib "") (part "CL05A105KA5NQNC"))
    )
    (comp (ref "L1")
      (value "8.2nH")
      (fields
        (field (name "BOM_Manufacturer Part") "LQW15AN8N2G00D")
        (field (name "BOM_Supplier Part") "C84404")
      )
      (libsource (lib "") (part "LQW15AN8N2G00D"))
    )
    (comp (ref "L3")
      (value "2.2uH")
      (fields
        (field (name "BOM_Manufacturer Part") "LQM2MPN2R2NG0L")
        (field (name "BOM_Supplier Part") "C83998")
      )
      (libsource (lib "") (part "LQM2MPN2R2NG0L"))
    )
    (comp (ref "Q6") (value "TP") (libsource (lib "") (part "TP")))
    (comp (ref "U18") (value "UBX-G7020-KT") (libsource (lib "") (part "UBX-G7020-KT")))
    (comp (ref "X2")
      (value "26MHz")
      (fields
        (field (name "BOM_Manufacturer Part") "1XTW26000MAA")
        (field (name "BOM_Supplier Part") "C213404")
      )
      (libsource (lib "") (part "1XTW26000MAA"))
    )
    (comp (ref "BAT1") (value "N68_BATJ") (libsource (lib "") (part "N68_BATJ")))
    (comp (ref "C1")
      (value "100nF")
      (fields
        (field (name "BOM_Manufacturer Part") "CL05B104KO5NNNC")
        (field (name "BOM_Supplier Part") "C1525")
      )
      (libsource (lib "") (part "CL05B104KO5NNNC"))
    )
    (comp (ref "C2")
      (value "10uF")
      (fields
        (field (name "BOM_Manufacturer Part") "CL05A106MQ5NUNC")
        (field (name "BOM_Supplier Part") "C15525")
      )
      (libsource (lib "") (part "CL05A106MQ5NUNC"))
    )
    (comp (ref "C3")
      (value "47nF")
      (fields
        (field (name "BOM_Manufacturer Part") "0402B473K250CT")
        (field (name "BOM_Supplier Part") "C314287")
      )
      (libsource (lib "") (part "0402B473K250CT"))
    )
    (comp (ref "C20")
      (value "1uF")
      (fields
        (field (name "BOM_Manufacturer Part") "CL05A105KA5NQNC")
        (field (name "BOM_Supplier Part") "C52923")
      )
      (libsource (lib "") (part "CL05A105KA5NQNC_1"))
    )
    (comp (ref "C34")
      (value "1uF")
      (fields
        (field (name "BOM_Manufacturer Part") "CL05A105KA5NQNC")
        (field (name "BOM_Supplier Part") "C52923")
      )
      (libsource (lib "") (part "CL05A105KA5NQNC"))
    )
    (comp (ref "C122")
      (value "4.7uF")
      (fields
        (field (name "BOM_Manufacturer Part") "CL05A475MP5NRNC")
        (field (name "BOM_Supplier Part") "C23733")
      )
      (libsource (lib "") (part "CL05A475MP5NRNC"))
    )
    (comp (ref "C134")
      (value "10uF")
      (fields
        (field (name "BOM_Manufacturer Part") "CL05A106MQ5NUNC")
        (field (name "BOM_Supplier Part") "C15525")
      )
      (libsource (lib "") (part "CL05A106MQ5NUNC"))
    )
    (comp (ref "C135")
      (value "22uF")
      (fields
        (field (name "BOM_Manufacturer Part") "CL10A226MQ8NRNC")
        (field (name "BOM_Supplier Part") "C59461")
      )
      (libsource (lib "") (part "CL10A226MQ8NRNC"))
    )
    (comp (ref "C136")
      (value "22uF")
      (fields
        (field (name "BOM_Manufacturer Part") "CL10A226MQ8NRNC")
        (field (name "BOM_Supplier Part") "C59461")
      )
      (libsource (lib "") (part "CL10A226MQ8NRNC"))
    )
    (comp (ref "D1")
      (value "1N5819WS")
      (fields (field (name "BOM_Supplier Part") "C191023"))
      (libsource (lib "") (part "1N5819WS"))
    )
    (comp (ref "L4")
      (value "1uH")
      (fields
        (field (name "BOM_Manufacturer Part") "HHEI252010A-1R0M-Q8")
        (field (name "BOM_Supplier Part") "C910025")
      )
      (libsource (lib "") (part "HHEI252010A-1R0M-Q8"))
    )
    (comp (ref "R7")
      (value "33kΩ")
      (fields
        (field (name "BOM_Manufacturer Part") "0402WGF3302TCE")
        (field (name "BOM_Supplier Part") "C25779")
      )
      (libsource (lib "") (part "0402WGF3302TCE"))
    )
    (comp (ref "R18")
      (value "33kΩ")
      (fields
        (field (name "BOM_Manufacturer Part") "0402WGF3302TCE")
        (field (name "BOM_Supplier Part") "C25779")
      )
      (libsource (lib "") (part "0402WGF3302TCE_1"))
    )
    (comp (ref "U32")
      (value "BQ25890RTWR")
      (fields (field (name "BOM_Supplier Part") "C130451"))
      (libsource (lib "") (part "BQ25890RTWR"))
    )
    (comp (ref "U39")
      (value "MAX17048G+T10")
      (fields (field (name "BOM_Supplier Part") "C2682616"))
      (libsource (lib "") (part "MAX17048G+T10"))
    )
    (comp (ref "U41")
      (value "SHTC3")
      (fields (field (name "BOM_Supplier Part") "C194656"))
      (libsource (lib "") (part "SHTC3"))
    )
    (comp (ref "ANT1")
      (value "RFANT3216120A5T")
      (fields (field (name "BOM_Supplier Part") "C127629"))
      (libsource (lib "") (part "RFANT3216120A5T"))
    )
    (comp (ref "C71")
      (value "4.7uF")
      (fields
        (field (name "BOM_Manufacturer Part") "CL05A475MP5NRNC")
        (field (name "BOM_Supplier Part") "C23733")
      )
      (libsource (lib "") (part "CL05A475MP5NRNC"))
    )
    (comp (ref "C74")
      (value "4.7uF")
      (fields
        (field (name "BOM_Manufacturer Part") "CL05A475MP5NRNC")
        (field (name "BOM_Supplier Part") "C23733")
      )
      (libsource (lib "") (part "CL05A475MP5NRNC_1"))
    )
    (comp (ref "C75")
      (value "4.7uF")
      (fields
        (field (name "BOM_Manufacturer Part") "CL05A475MP5NRNC")
        (field (name "BOM_Supplier Part") "C23733")
      )
      (libsource (lib "") (part "CL05A475MP5NRNC"))
    )
    (comp (ref "L2")
      (value "3.3uH")
      (fields
        (field (name "BOM_Manufacturer Part") "MPL2012S3R3MHT")
        (field (name "BOM_Supplier Part") "C98331")
      )
      (libsource (lib "") (part "MPL2012S3R3MHT"))
    )
    (comp (ref "R10")
      (value "33kΩ")
      (fields
        (field (name "BOM_Manufacturer Part") "0402WGF3302TCE")
        (field (name "BOM_Supplier Part") "C25779")
      )
      (libsource (lib "") (part "0402WGF3302TCE_2"))
    )
    (comp (ref "R11")
      (value "33kΩ")
      (fields
        (field (name "BOM_Manufacturer Part") "0402WGF3302TCE")
        (field (name "BOM_Supplier Part") "C25779")
      )
      (libsource (lib "") (part "0402WGF3302TCE_1"))
    )
    (comp (ref "R29")
      (value "33kΩ")
      (fields
        (field (name "BOM_Manufacturer Part") "0402WGF3302TCE")
        (field (name "BOM_Supplier Part") "C25779")
      )
      (libsource (lib "") (part "0402WGF3302TCE"))
    )
    (comp (ref "R49")
      (value "0Ω")
      (fields
        (field (name "BOM_Manufacturer Part") "0402WGF0000TCE")
        (field (name "BOM_Supplier Part") "C17168")
      )
      (libsource (lib "") (part "0402WGF0000TCE"))
    )
    (comp (ref "R54")
      (value "0Ω")
      (fields
        (field (name "BOM_Manufacturer Part") "0402WGF0000TCE")
        (field (name "BOM_Supplier Part") "C17168")
      )
      (libsource (lib "") (part "0402WGF0000TCE"))
    )
    (comp (ref "RN1")
      (value "33kΩ")
      (fields
        (field (name "BOM_Manufacturer Part") "WA04X333JTL")
        (field (name "BOM_Supplier Part") "C431861")
      )
      (libsource (lib "") (part "WA04X333JTL"))
    )
    (comp (ref "U48") (value "A_P6214") (libsource (lib "") (part "A_P6214")))
    (comp (ref "C19")
      (value "100nF")
      (fields
        (field (name "BOM_Manufacturer Part") "CL05B104KO5NNNC")
        (field (name "BOM_Supplier Part") "C1525")
      )
      (libsource (lib "") (part "CL05B104KO5NNNC"))
    )
    (comp (ref "C39")
      (value "10uF")
      (fields
        (field (name "BOM_Manufacturer Part") "CL05A106MQ5NUNC")
        (field (name "BOM_Supplier Part") "C15525")
      )
      (libsource (lib "") (part "CL05A106MQ5NUNC"))
    )
    (comp (ref "K1") (value "N168X_Key") (libsource (lib "") (part "N168X_Key")))
    (comp (ref "K2") (value "N168X_Key") (libsource (lib "") (part "N168X_Key")))
    (comp (ref "K3") (value "N168X_Key") (libsource (lib "") (part "N168X_Key")))
    (comp (ref "K4") (value "N168X_Key") (libsource (lib "") (part "N168X_Key")))
    (comp (ref "K5") (value "N168X_Key") (libsource (lib "") (part "N168X_Key")))
    (comp (ref "K6") (value "N168X_Key") (libsource (lib "") (part "N168X_Key")))
    (comp (ref "K7") (value "N168X_Key") (libsource (lib "") (part "N168X_Key")))
    (comp (ref "K8") (value "N168X_Key") (libsource (lib "") (part "N168X_Key")))
    (comp (ref "K9") (value "N168X_Key") (libsource (lib "") (part "N168X_Key")))
    (comp (ref "K10") (value "N168X_Key") (libsource (lib "") (part "N168X_Key")))
    (comp (ref "K11") (value "N168X_Key") (libsource (lib "") (part "N168X_Key")))
    (comp (ref "K12") (value "N168X_Key") (libsource (lib "") (part "N168X_Key")))
    (comp (ref "K13") (value "N168X_Key") (libsource (lib "") (part "N168X_Key")))
    (comp (ref "K14") (value "N168X_Key") (libsource (lib "") (part "N168X_Key")))
    (comp (ref "K15") (value "N168X_Key") (libsource (lib "") (part "N168X_Key")))
    (comp (ref "K16") (value "N168X_Key") (libsource (lib "") (part "N168X_Key")))
    (comp (ref "K17") (value "N168X_Key") (libsource (lib "") (part "N168X_Key")))
    (comp (ref "K18") (value "N168X_Key") (libsource (lib "") (part "N168X_Key")))
    (comp (ref "K19") (value "N168X_Key") (libsource (lib "") (part "N168X_Key")))
    (comp (ref "K20") (value "N168X_Key") (libsource (lib "") (part "N168X_Key")))
    (comp (ref "K21") (value "N168X_Key") (libsource (lib "") (part "N168X_Key")))
    (comp (ref "LED1")
      (value "TZ-P2-0603WYS1-1.1T")
      (fields (field (name "BOM_Supplier Part") "C916072"))
      (libsource (lib "") (part "TZ-P2-0603WYS1-1.1T"))
    )
    (comp (ref "LED2")
      (value "TZ-P2-0603WYS1-1.1T")
      (fields (field (name "BOM_Supplier Part") "C916072"))
      (libsource (lib "") (part "TZ-P2-0603WYS1-1.1T"))
    )
    (comp (ref "Q2")
      (value "HSST3139")
      (fields (field (name "BOM_Supplier Part") "C700948"))
      (libsource (lib "") (part "HSST3139"))
    )
    (comp (ref "R20")
      (value "1kΩ")
      (fields
        (field (name "BOM_Manufacturer Part") "0603WAF1001T5E")
        (field (name "BOM_Supplier Part") "C21190")
      )
      (libsource (lib "") (part "0603WAF1001T5E"))
    )
    (comp (ref "U8")
      (value "PCA9555RGERG4")
      (fields (field (name "BOM_Supplier Part") "C2669780"))
      (libsource (lib "") (part "PCA9555RGERG4"))
    )
    (comp (ref "C8")
      (value "100nF")
      (fields
        (field (name "BOM_Manufacturer Part") "CL05B104KO5NNNC")
        (field (name "BOM_Supplier Part") "C1525")
      )
      (libsource (lib "") (part "CL05B104KO5NNNC"))
    )
    (comp (ref "C9")
      (value "10uF")
      (fields
        (field (name "BOM_Manufacturer Part") "CL05A106MQ5NUNC")
        (field (name "BOM_Supplier Part") "C15525")
      )
      (libsource (lib "") (part "CL05A106MQ5NUNC"))
    )
    (comp (ref "R4")
      (value "33kΩ")
      (fields
        (field (name "BOM_Manufacturer Part") "0402WGF3302TCE")
        (field (name "BOM_Supplier Part") "C25779")
      )
      (libsource (lib "") (part "0402WGF3302TCE"))
    )
    (comp (ref "RN2")
      (value "33kΩ")
      (fields
        (field (name "BOM_Manufacturer Part") "WA04X333JTL")
        (field (name "BOM_Supplier Part") "C431861")
      )
      (libsource (lib "") (part "WA04X333JTL"))
    )
    (comp (ref "U16")
      (value "MKDV32GCL-STL")
      (fields (field (name "BOM_Supplier Part") "C2844071"))
      (libsource (lib "") (part "MKDV32GCL-STL"))
    )
    (comp (ref "C18")
      (value "47uF")
      (fields
        (field (name "BOM_Manufacturer Part") "CL21A476MQYNNNE")
        (field (name "BOM_Supplier Part") "C16780")
      )
      (libsource (lib "") (part "CL21A476MQYNNNE"))
    )
    (comp (ref "J17") (value "JW_S-5012-A") (libsource (lib "") (part "JW_S-5012-A")))
    (comp (ref "Q1")
      (value "HSST3139")
      (fields (field (name "BOM_Supplier Part") "C700948"))
      (libsource (lib "") (part "HSST3139"))
    )
    (comp (ref "C40")
      (value "100nF")
      (fields
        (field (name "BOM_Manufacturer Part") "CL05B104KO5NNNC")
        (field (name "BOM_Supplier Part") "C1525")
      )
      (libsource (lib "") (part "CL05B104KO5NNNC"))
    )
    (comp (ref "C42")
      (value "100nF")
      (fields
        (field (name "BOM_Manufacturer Part") "CL05B104KO5NNNC")
        (field (name "BOM_Supplier Part") "C1525")
      )
      (libsource (lib "") (part "CL05B104KO5NNNC"))
    )
    (comp (ref "D3")
      (value "1N5819WS")
      (fields (field (name "BOM_Supplier Part") "C191023"))
      (libsource (lib "") (part "1N5819WS"))
    )
    (comp (ref "U204") (value "RX8900CE") (libsource (lib "") (part "RX8900CE")))
  )
  (nets
    (net (code "1") (name "3V3") (class "Default")
      (node (ref "C1") (pin "2") (pinfunction "2_2") (pintype "input"))
      (node (ref "C10") (pin "2") (pinfunction "2_2") (pintype "input"))
      (node (ref "C11") (pin "2") (pinfunction "2_2") (pintype "input"))
      (node (ref "C12") (pin "2") (pinfunction "2_2") (pintype "input"))
      (node (ref "C13") (pin "2") (pinfunction "2_2") (pintype "input"))
      (node (ref "C14") (pin "2") (pinfunction "2_2") (pintype "input"))
      (node (ref "C15") (pin "2") (pinfunction "2_2") (pintype "unspecified"))
      (node (ref "C16") (pin "1") (pinfunction "1_1") (pintype "unspecified"))
      (node (ref "C19") (pin "2") (pinfunction "2_2") (pintype "input"))
      (node (ref "C29") (pin "2") (pinfunction "2_2") (pintype "input"))
      (node (ref "C36") (pin "2") (pinfunction "2_2") (pintype "input"))
      (node (ref "C38") (pin "2") (pinfunction "2_2") (pintype "input"))
      (node (ref "C42") (pin "2") (pinfunction "2_2") (pintype "input"))
      (node (ref "C46") (pin "1") (pinfunction "1_1") (pintype "unspecified"))
      (node (ref "C47") (pin "1") (pinfunction "1_1") (pintype "unspecified"))
      (node (ref "C49") (pin "1") (pinfunction "1_1") (pintype "input"))
      (node (ref "C59") (pin "2") (pinfunction "2_2") (pintype "input"))
      (node (ref "C64") (pin "2") (pinfunction "2_2") (pintype "input"))
      (node (ref "C65") (pin "2") (pinfunction "2_2") (pintype "input"))
      (node (ref "C66") (pin "2") (pinfunction "2_2") (pintype "input"))
      (node (ref "C74") (pin "2") (pinfunction "2_2") (pintype "input"))
      (node (ref "C75") (pin "1") (pinfunction "1_1") (pintype "input"))
      (node (ref "C8") (pin "2") (pinfunction "2_2") (pintype "input"))
      (node (ref "C9") (pin "2") (pinfunction "2_2") (pintype "input"))
      (node (ref "CONN1") (pin "11") (pinfunction "11_11") (pintype "unspecified"))
      (node (ref "J17") (pin "11") (pinfunction "IOVCC1.8_11") (pintype "unspecified"))
      (node (ref "J17") (pin "12") (pinfunction "IOVCC1.8_12") (pintype "unspecified"))
      (node (ref "J17") (pin "13") (pinfunction "VCC2.8_13") (pintype "unspecified"))
      (node (ref "J17") (pin "14") (pinfunction "VCC2.8_14") (pintype "unspecified"))
      (node (ref "LED16") (pin "1") (pinfunction "+_1") (pintype "unspecified"))
      (node (ref "Q1") (pin "2") (pinfunction "S_2") (pintype "unspecified"))
      (node (ref "Q2") (pin "2") (pinfunction "S_2") (pintype "unspecified"))
      (node (ref "R1") (pin "2") (pinfunction "2_2") (pintype "input"))
      (node (ref "R12") (pin "2") (pinfunction "2_2") (pintype "input"))
      (node (ref "R13") (pin "2") (pinfunction "2_2") (pintype "input"))
      (node (ref "R2") (pin "2") (pinfunction "2_2") (pintype "input"))
      (node (ref "R29") (pin "2") (pinfunction "2_2") (pintype "input"))
      (node (ref "R3") (pin "2") (pinfunction "2_2") (pintype "input"))
      (node (ref "R4") (pin "2") (pinfunction "2_2") (pintype "input"))
      (node (ref "RN1") (pin "5") (pinfunction "5_5") (pintype "unspecified"))
      (node (ref "RN1") (pin "6") (pinfunction "6_6") (pintype "unspecified"))
      (node (ref "RN1") (pin "7") (pinfunction "7_7") (pintype "unspecified"))
      (node (ref "RN1") (pin "8") (pinfunction "8_8") (pintype "unspecified"))
      (node (ref "RN2") (pin "5") (pinfunction "5_5") (pintype "unspecified"))
      (node (ref "RN2") (pin "6") (pinfunction "6_6") (pintype "unspecified"))
      (node (ref "RN2") (pin "7") (pinfunction "7_7") (pintype "unspecified"))
      (node (ref "RN2") (pin "8") (pinfunction "8_8") (pintype "unspecified"))
      (node (ref "RN3") (pin "5") (pinfunction "5_5") (pintype "unspecified"))
      (node (ref "RN3") (pin "6") (pinfunction "6_6") (pintype "unspecified"))
      (node (ref "RN3") (pin "7") (pinfunction "7_7") (pintype "unspecified"))
      (node (ref "RN3") (pin "8") (pinfunction "8_8") (pintype "unspecified"))
      (node (ref "U1") (pin "47") (pinfunction "3V3_47") (pintype "unspecified"))
      (node (ref "U128") (pin "13") (pinfunction "VDDC_13") (pintype "unspecified"))
      (node (ref "U128") (pin "14") (pinfunction "VDDB_14") (pintype "unspecified"))
      (node (ref "U128") (pin "26") (pinfunction "VDDSPK_26") (pintype "unspecified"))
      (node (ref "U128") (pin "31") (pinfunction "VDDA_31") (pintype "unspecified"))
      (node (ref "U135") (pin "5") (pinfunction "VDD_5") (pintype "unspecified"))
      (node (ref "U140") (pin "32") (pinfunction "IOVDD_32") (pintype "unspecified"))
      (node (ref "U140") (pin "7") (pinfunction "VDD_7") (pintype "unspecified"))
      (node (ref "U141") (pin "18") (pinfunction "A0_18") (pintype "unspecified"))
      (node (ref "U141") (pin "21") (pinfunction "VCC_21") (pintype "unspecified"))
      (node (ref "U16") (pin "8") (pinfunction "VDD_8") (pintype "unspecified"))
      (node (ref "U18") (pin "21") (pinfunction "V_DCDC_IN_21") (pintype "unspecified"))
      (node (ref "U18") (pin "6") (pinfunction "V_BAKP_6") (pintype "unspecified"))
      (node (ref "U18") (pin "7") (pinfunction "VDD_IO_7") (pintype "unspecified"))
      (node (ref "U2") (pin "21") (pinfunction "VCC_21") (pintype "unspecified"))
      (node (ref "U2") (pin "23") (pinfunction "A1_23") (pintype "unspecified"))
      (node (ref "U204") (pin "2") (pinfunction "VDD_2") (pintype "unspecified"))
      (node (ref "U3") (pin "5") (pinfunction "VCC_5") (pintype "unspecified"))
      (node (ref "U33") (pin "1") (pinfunction "EN1_1") (pintype "unspecified"))
      (node (ref "U33") (pin "2") (pinfunction "VIN_2") (pintype "unspecified"))
      (node (ref "U33") (pin "3") (pinfunction "EN2_3") (pintype "unspecified"))
      (node (ref "U41") (pin "1") (pinfunction "VCC_1") (pintype "unspecified"))
      (node (ref "U48") (pin "30") (pinfunction "VDDIO_30") (pintype "unspecified"))
      (node (ref "U48") (pin "33") (pinfunction "VBAT_33") (pintype "unspecified"))
      (node (ref "U64") (pin "2") (pinfunction "VCC_2") (pintype "unspecified"))
      (node (ref "U64") (pin "5") (pinfunction "VCC_5") (pintype "unspecified"))
      (node (ref "U8") (pin "21") (pinfunction "VCC_21") (pintype "unspecified"))
      (node (ref "X1") (pin "4") (pinfunction "VDD_4") (pintype "unspecified"))
    )
    (net (code "2") (name "BAT+") (class "Default")
      (node (ref "BAT1") (pin "3") (pinfunction "BAT+_3") (pintype "unspecified"))
      (node (ref "C134") (pin "2") (pinfunction "2_2") (pintype "input"))
      (node (ref "C34") (pin "2") (pinfunction "2_2") (pintype "unspecified"))
      (node (ref "D3") (pin "2") (pinfunction "A_2") (pintype "unspecified"))
      (node (ref "U32") (pin "13") (pinfunction "BAT_13") (pintype "unspecified"))
      (node (ref "U32") (pin "14") (pinfunction "BAT_14") (pintype "unspecified"))
      (node (ref "U39") (pin "2") (pinfunction "CELL_2") (pintype "unspecified"))
      (node (ref "U39") (pin "3") (pinfunction "VDD_3") (pintype "unspecified"))
    )
    (net (code "3") (name "CAM_AVDD_2V8") (class "Default")
      (node (ref "C28") (pin "2") (pinfunction "2_2") (pintype "unspecified"))
      (node (ref "CONN1") (pin "23") (pinfunction "23_23") (pintype "unspecified"))
      (node (ref "CONN1") (pin "4") (pinfunction "4_4") (pintype "unspecified"))
      (node (ref "U33") (pin "4") (pinfunction "VOUT2_4") (pintype "unspecified"))
    )
    (net (code "4") (name "CAM_DVDD_1V5") (class "Default")
      (node (ref "C32") (pin "2") (pinfunction "2_2") (pintype "unspecified"))
      (node (ref "CONN1") (pin "10") (pinfunction "10_10") (pintype "unspecified"))
      (node (ref "U33") (pin "6") (pinfunction "VOUT1_6") (pintype "unspecified"))
    )
    (net (code "5") (name "CAM_PWDN") (class "Default")
      (node (ref "CONN1") (pin "8") (pinfunction "8_8") (pintype "unspecified"))
      (node (ref "U1") (pin "14") (pinfunction "PA07_SLCD_D7_14") (pintype "unspecified"))
    )
    (net (code "6") (name "CAM_RST") (class "Default")
      (node (ref "CONN1") (pin "6") (pinfunction "6_6") (pintype "unspecified"))
      (node (ref "U1") (pin "6") (pinfunction "PA06_SLCD_D6_6") (pintype "unspecified"))
    )
    (net (code "7") (name "CIM_D2_D0") (class "Default")
      (node (ref "CONN1") (pin "19") (pinfunction "19_19") (pintype "unspecified"))
      (node (ref "U1") (pin "20") (pinfunction "PA19_CIM_D0_20") (pintype "unspecified"))
    )
    (net (code "8") (name "CIM_D3_D1") (class "Default")
      (node (ref "CONN1") (pin "21") (pinfunction "21_21") (pintype "unspecified"))
      (node (ref "U1") (pin "24") (pinfunction "PA18_CIM_D1_24") (pintype "unspecified"))
    )
    (net (code "9") (name "CIM_D4_D2") (class "Default")
      (node (ref "CONN1") (pin "22") (pinfunction "22_22") (pintype "unspecified"))
      (node (ref "U1") (pin "21") (pinfunction "PA17_CIM_D2_21") (pintype "unspecified"))
    )
    (net (code "10") (name "CIM_D5_D3") (class "Default")
      (node (ref "CONN1") (pin "20") (pinfunction "20_20") (pintype "unspecified"))
      (node (ref "U1") (pin "19") (pinfunction "PA16_CIM_D3_19") (pintype "unspecified"))
    )
    (net (code "11") (name "CIM_D6_D4") (class "Default")
      (node (ref "CONN1") (pin "18") (pinfunction "18_18") (pintype "unspecified"))
      (node (ref "U1") (pin "23") (pinfunction "PA15_CIM_D4_23") (pintype "unspecified"))
    )
    (net (code "12") (name "CIM_D7_D5") (class "Default")
      (node (ref "CONN1") (pin "16") (pinfunction "16_16") (pintype "unspecified"))
      (node (ref "U1") (pin "22") (pinfunction "PA14_CIM_D5_22") (pintype "unspecified"))
    )
    (net (code "13") (name "CIM_D8_D6") (class "Default")
      (node (ref "CONN1") (pin "14") (pinfunction "14_14") (pintype "unspecified"))
      (node (ref "U1") (pin "25") (pinfunction "PA13_CIM_D6_25") (pintype "unspecified"))
    )
    (net (code "14") (name "CIM_D9_D7") (class "Default")
      (node (ref "CONN1") (pin "12") (pinfunction "12_12") (pintype "unspecified"))
      (node (ref "U1") (pin "18") (pinfunction "PA12_CIM_D7_18") (pintype "unspecified"))
    )
    (net (code "15") (name "CIM_HSYN") (class "Default")
      (node (ref "CONN1") (pin "9") (pinfunction "9_9") (pintype "unspecified"))
      (node (ref "U1") (pin "27") (pinfunction "PA09_CIM_HSYN_27") (pintype "unspecified"))
    )
    (net (code "16") (name "CIM_MCLK") (class "Default")
      (node (ref "CONN1") (pin "13") (pinfunction "13_13") (pintype "unspecified"))
      (node (ref "U1") (pin "29") (pinfunction "PA11_CIM_MCLK_29") (pintype "unspecified"))
    )
    (net (code "17") (name "CIM_PCLK") (class "Default")
      (node (ref "CONN1") (pin "17") (pinfunction "17_17") (pintype "unspecified"))
      (node (ref "U1") (pin "26") (pinfunction "PA08_CIM_PCLK_26") (pintype "unspecified"))
    )
    (net (code "18") (name "CIM_VSYN") (class "Default")
      (node (ref "CONN1") (pin "7") (pinfunction "7_7") (pintype "unspecified"))
      (node (ref "U1") (pin "28") (pinfunction "PA10_CIM_VSYN_28") (pintype "unspecified"))
    )
    (net (code "19") (name "CLK_32k") (class "Default")
      (node (ref "R11") (pin "1") (pinfunction "1_1") (pintype "input"))
      (node (ref "U1") (pin "127") (pinfunction "PB26_RTC32K_127") (pintype "unspecified"))
    )
    (net (code "20") (name "CLK_12288") (class "Default")
      (node (ref "U140") (pin "1") (pinfunction "CLKI_1") (pintype "unspecified"))
      (node (ref "X1") (pin "3") (pinfunction "OUT_3") (pintype "unspecified"))
    )
    (net (code "21") (name "CODEC_AUXIN_L") (class "Default")
      (node (ref "C37") (pin "1") (pinfunction "1_1") (pintype "input"))
      (node (ref "U128") (pin "19") (pinfunction "LAUXIN_19") (pintype "unspecified"))
    )
    (net (code "22") (name "CODEC_AUXIN_R") (class "Default")
      (node (ref "C35") (pin "1") (pinfunction "1_1") (pintype "input"))
      (node (ref "U128") (pin "20") (pinfunction "RAUXIN_20") (pintype "unspecified"))
    )
    (net (code "23") (name "CODEC_AUXOUT_L") (class "Default")
      (node (ref "C22") (pin "2") (pinfunction "2_2") (pintype "unspecified"))
      (node (ref "U128") (pin "22") (pinfunction "AUXOUT2_22") (pintype "unspecified"))
    )
    (net (code "24") (name "CODEC_AUXOUT_R") (class "Default")
      (node (ref "C26") (pin "2") (pinfunction "2_2") (pintype "unspecified"))
      (node (ref "U128") (pin "21") (pinfunction "AUXOUT1_21") (pintype "unspecified"))
    )
    (net (code "25") (name "CODEC_HP_L") (class "Default")
      (node (ref "U128") (pin "30") (pinfunction "LHP_30") (pintype "unspecified"))
    )
    (net (code "26") (name "CODEC_HP_R") (class "Default")
      (node (ref "U128") (pin "29") (pinfunction "RHP_29") (pintype "unspecified"))
    )
    (net (code "27") (name "CODEC_MICBIAS") (class "Default")
      (node (ref "C4") (pin "2") (pinfunction "2_2") (pintype "input"))
      (node (ref "C60") (pin "2") (pinfunction "2_2") (pintype "input"))
      (node (ref "MIC1") (pin "1") (pinfunction "VDD_1") (pintype "unspecified"))
      (node (ref "U128") (pin "32") (pinfunction "MICBIAS_32") (pintype "unspecified"))
    )
    (net (code "28") (name "CODEC_MICLN") (class "Default")
      (node (ref "C23") (pin "1") (pinfunction "1_1") (pintype "unspecified"))
      (node (ref "U128") (pin "2") (pinfunction "LMICN_2") (pintype "unspecified"))
    )
    (net (code "29") (name "CODEC_MICLP") (class "Default")
      (node (ref "C5") (pin "1") (pinfunction "1_1") (pintype "unspecified"))
      (node (ref "U128") (pin "1") (pinfunction "LMICP_1") (pintype "unspecified"))
    )
    (net (code "30") (name "CODEC_MICRN") (class "Default")
      (node (ref "C6") (pin "1") (pinfunction "1_1") (pintype "unspecified"))
      (node (ref "U128") (pin "5") (pinfunction "RMICN_5") (pintype "unspecified"))
    )
    (net (code "31") (name "CODEC_MICRP") (class "Default")
      (node (ref "C7") (pin "2") (pinfunction "2_2") (pintype "unspecified"))
      (node (ref "U128") (pin "4") (pinfunction "RMICP_4") (pintype "unspecified"))
    )
    (net (code "32") (name "CODEC_VREF") (class "Default")
      (node (ref "C62") (pin "2") (pinfunction "2_2") (pintype "input"))
      (node (ref "U128") (pin "27") (pinfunction "VREF_27") (pintype "unspecified"))
    )
    (net (code "33") (name "CPU_INT_FUSB301") (class "Default")
      (node (ref "U135") (pin "10") (pinfunction "INT_N_10") (pintype "unspecified"))
      (node (ref "U2") (pin "6") (pinfunction "P05_6") (pintype "unspecified"))
    )
    (net (code "34") (name "CPU_INT_GAUGE") (class "Default")
      (node (ref "U2") (pin "7") (pinfunction "P06_7") (pintype "unspecified"))
      (node (ref "U39") (pin "5") (pinfunction "ALRT#_5") (pintype "unspecified"))
    )
    (net (code "35") (name "CPU_INT_IOEXP_2") (class "Default")
      (node (ref "RN3") (pin "1") (pinfunction "1_1") (pintype "unspecified"))
      (node (ref "U1") (pin "44") (pinfunction "PC20_44") (pintype "unspecified"))
      (node (ref "U2") (pin "22") (pinfunction "INT#_22") (pintype "unspecified"))
    )
    (net (code "36") (name "CPU_INT_IOEXP_KP") (class "Default")
      (node (ref "RN3") (pin "3") (pinfunction "3_3") (pintype "unspecified"))
      (node (ref "U1") (pin "46") (pinfunction "PC19_46") (pintype "unspecified"))
      (node (ref "U8") (pin "22") (pinfunction "INT#_22") (pintype "unspecified"))
    )
    (net (code "37") (name "CPU_INT_IOEXP_Y762") (class "Default")
      (node (ref "RN3") (pin "2") (pinfunction "2_2") (pintype "unspecified"))
      (node (ref "U1") (pin "45") (pinfunction "PC18_45") (pintype "unspecified"))
      (node (ref "U141") (pin "22") (pinfunction "INT#_22") (pintype "unspecified"))
    )
    (net (code "38") (name "CPU_INT_PMIC") (class "Default")
      (node (ref "U2") (pin "11") (pinfunction "P11_11") (pintype "unspecified"))
      (node (ref "U32") (pin "7") (pinfunction "INT_7") (pintype "unspecified"))
    )
    (net (code "39") (name "CPU_INT_RTC") (class "Default")
      (node (ref "U2") (pin "12") (pinfunction "P12_12") (pintype "unspecified"))
      (node (ref "U204") (pin "10") (pinfunction "/INT_10") (pintype "unspecified"))
    )
    (net (code "40") (name "CPU_RESET#") (class "Default")
      (node (ref "FPC1") (pin "12") (pinfunction "12_12") (pintype "unspecified"))
      (node (ref "SW1") (pin "3") (pinfunction "3_3") (pintype "unspecified"))
      (node (ref "SW1") (pin "4") (pinfunction "4_4") (pintype "unspecified"))
      (node (ref "U1") (pin "78") (pinfunction "PPRST#_78") (pintype "unspecified"))
    )
    (net (code "41") (name "CPU_TCK") (class "Default")
      (node (ref "FPC1") (pin "7") (pinfunction "7_7") (pintype "unspecified"))
      (node (ref "U1") (pin "121") (pinfunction "TCK_121") (pintype "unspecified"))
    )
    (net (code "42") (name "CPU_TDI") (class "Default")
      (node (ref "FPC1") (pin "4") (pinfunction "4_4") (pintype "unspecified"))
      (node (ref "U1") (pin "59") (pinfunction "TDI_UART2_RX_59") (pintype "unspecified"))
    )
    (net (code "43") (name "CPU_TDO") (class "Default")
      (node (ref "FPC1") (pin "5") (pinfunction "5_5") (pintype "unspecified"))
      (node (ref "U1") (pin "60") (pinfunction "TDO_UART2_TX_60") (pintype "unspecified"))
    )
    (net (code "44") (name "CPU_TMS") (class "Default")
      (node (ref "FPC1") (pin "6") (pinfunction "6_6") (pintype "unspecified"))
      (node (ref "U1") (pin "120") (pinfunction "TMS_120") (pintype "unspecified"))
    )
    (net (code "45") (name "CPU_TRST") (class "Default")
      (node (ref "FPC1") (pin "8") (pinfunction "8_8") (pintype "unspecified"))
      (node (ref "U1") (pin "113") (pinfunction "TRST_113") (pintype "unspecified"))
    )
    (net (code "46") (name "CPU_WKUP#") (class "Default")
      (node (ref "D1") (pin "2") (pinfunction "A_2") (pintype "unspecified"))
      (node (ref "U1") (pin "79") (pinfunction "PB31_WKUP#_79") (pintype "unspecified"))
    )
    (net (code "47") (name "EAR_1") (class "Default")
      (node (ref "J1") (pin "1") (pinfunction "1_1") (pintype "unspecified"))
      (node (ref "J1") (pin "2") (pinfunction "2_2") (pintype "unspecified"))
      (node (ref "U130") (pin "8") (pinfunction "OUT-_8") (pintype "unspecified"))
    )
    (net (code "48") (name "EAR_2") (class "Default")
      (node (ref "J2") (pin "1") (pinfunction "1_1") (pintype "unspecified"))
      (node (ref "J2") (pin "2") (pinfunction "2_2") (pintype "unspecified"))
      (node (ref "R16") (pin "1") (pinfunction "1_1") (pintype "input"))
      (node (ref "U130") (pin "5") (pinfunction "OUT+_5") (pintype "unspecified"))
    )
    (net (code "49") (name "EXCLK") (class "Default")
      (node (ref "U1") (pin "118") (pinfunction "PB27_EXCLK_118") (pintype "unspecified"))
    )
    (net (code "50") (name "GND") (class "Default")
      (node (ref "BAT1") (pin "1") (pinfunction "BAT-_1") (pintype "unspecified"))
      (node (ref "BAT1") (pin "4") (pinfunction "SHELL_4") (pintype "unspecified"))
      (node (ref "BAT1") (pin "5") (pinfunction "SHELL_5") (pintype "unspecified"))
      (node (ref "BAT1") (pin "6") (pinfunction "SHELL_6") (pintype "unspecified"))
      (node (ref "BAT1") (pin "7") (pinfunction "SHELL_7") (pintype "unspecified"))
      (node (ref "C1") (pin "1") (pinfunction "1_1") (pintype "input"))
      (node (ref "C10") (pin "1") (pinfunction "1_1") (pintype "input"))
      (node (ref "C11") (pin "1") (pinfunction "1_1") (pintype "input"))
      (node (ref "C12") (pin "1") (pinfunction "1_1") (pintype "input"))
      (node (ref "C122") (pin "2") (pinfunction "2_2") (pintype "input"))
      (node (ref "C13") (pin "1") (pinfunction "1_1") (pintype "input"))
      (node (ref "C134") (pin "1") (pinfunction "1_1") (pintype "input"))
      (node (ref "C135") (pin "2") (pinfunction "2_2") (pintype "unspecified"))
      (node (ref "C136") (pin "2") (pinfunction "2_2") (pintype "unspecified"))
      (node (ref "C14") (pin "1") (pinfunction "1_1") (pintype "input"))
      (node (ref "C15") (pin "1") (pinfunction "1_1") (pintype "unspecified"))
      (node (ref "C16") (pin "2") (pinfunction "2_2") (pintype "unspecified"))
      (node (ref "C18") (pin "1") (pinfunction "1_1") (pintype "input"))
      (node (ref "C19") (pin "1") (pinfunction "1_1") (pintype "input"))
      (node (ref "C2") (pin "2") (pinfunction "2_2") (pintype "input"))
      (node (ref "C20") (pin "1") (pinfunction "1_1") (pintype "unspecified"))
      (node (ref "C21") (pin "1") (pinfunction "1_1") (pintype "unspecified"))
      (node (ref "C23") (pin "2") (pinfunction "2_2") (pintype "unspecified"))
      (node (ref "C24") (pin "1") (pinfunction "1_1") (pintype "input"))
      (node (ref "C25") (pin "1") (pinfunction "1_1") (pintype "input"))
      (node (ref "C27") (pin "1") (pinfunction "1_1") (pintype "unspecified"))
      (node (ref "C28") (pin "1") (pinfunction "1_1") (pintype "unspecified"))
      (node (ref "C29") (pin "1") (pinfunction "1_1") (pintype "input"))
      (node (ref "C30") (pin "1") (pinfunction "1_1") (pintype "input"))
      (node (ref "C31") (pin "2") (pinfunction "2_2") (pintype "input"))
      (node (ref "C32") (pin "1") (pinfunction "1_1") (pintype "unspecified"))
      (node (ref "C34") (pin "1") (pinfunction "1_1") (pintype "unspecified"))
      (node (ref "C36") (pin "1") (pinfunction "1_1") (pintype "input"))
      (node (ref "C38") (pin "1") (pinfunction "1_1") (pintype "input"))
      (node (ref "C39") (pin "1") (pinfunction "1_1") (pintype "input"))
      (node (ref "C4") (pin "1") (pinfunction "1_1") (pintype "input"))
      (node (ref "C40") (pin "1") (pinfunction "1_1") (pintype "input"))
      (node (ref "C41") (pin "1") (pinfunction "1_1") (pintype "input"))
      (node (ref "C42") (pin "1") (pinfunction "1_1") (pintype "input"))
      (node (ref "C43") (pin "2") (pinfunction "2_2") (pintype "unspecified"))
      (node (ref "C44") (pin "2") (pinfunction "2_2") (pintype "input"))
      (node (ref "C45") (pin "1") (pinfunction "1_1") (pintype "unspecified"))
      (node (ref "C46") (pin "2") (pinfunction "2_2") (pintype "unspecified"))
      (node (ref "C47") (pin "2") (pinfunction "2_2") (pintype "unspecified"))
      (node (ref "C48") (pin "2") (pinfunction "2_2") (pintype "unspecified"))
      (node (ref "C49") (pin "2") (pinfunction "2_2") (pintype "input"))
      (node (ref "C50") (pin "2") (pinfunction "2_2") (pintype "unspecified"))
      (node (ref "C59") (pin "1") (pinfunction "1_1") (pintype "input"))
      (node (ref "C6") (pin "2") (pinfunction "2_2") (pintype "unspecified"))
      (node (ref "C60") (pin "1") (pinfunction "1_1") (pintype "input"))
      (node (ref "C62") (pin "1") (pinfunction "1_1") (pintype "input"))
      (node (ref "C64") (pin "1") (pinfunction "1_1") (pintype "input"))
      (node (ref "C65") (pin "1") (pinfunction "1_1") (pintype "input"))
      (node (ref "C66") (pin "1") (pinfunction "1_1") (pintype "input"))
      (node (ref "C71") (pin "2") (pinfunction "2_2") (pintype "input"))
      (node (ref "C74") (pin "1") (pinfunction "1_1") (pintype "input"))
      (node (ref "C75") (pin "2") (pinfunction "2_2") (pintype "input"))
      (node (ref "C8") (pin "1") (pinfunction "1_1") (pintype "input"))
      (node (ref "C9") (pin "1") (pinfunction "1_1") (pintype "input"))
      (node (ref "CONN1") (pin "15") (pinfunction "15_15") (pintype "unspecified"))
      (node (ref "CONN1") (pin "2") (pinfunction "2_2") (pintype "unspecified"))
      (node (ref "CONN1") (pin "24") (pinfunction "24_24") (pintype "unspecified"))
      (node (ref "CONN1") (pin "25") (pinfunction "25_25") (pintype "unspecified"))
      (node (ref "CONN1") (pin "26") (pinfunction "26_26") (pintype "unspecified"))
      (node (ref "FPC1") (pin "1") (pinfunction "1_1") (pintype "unspecified"))
      (node (ref "FPC1") (pin "13") (pinfunction "13_13") (pintype "unspecified"))
      (node (ref "FPC1") (pin "14") (pinfunction "14_14") (pintype "unspecified"))
      (node (ref "FPC1") (pin "9") (pinfunction "9_9") (pintype "unspecified"))
      (node (ref "J17") (pin "1") (pinfunction "LEDK_1") (pintype "unspecified"))
      (node (ref "J17") (pin "15") (pinfunction "GND_15") (pintype "unspecified"))
      (node (ref "J17") (pin "16") (pinfunction "GND_16") (pintype "unspecified"))
      (node (ref "J17") (pin "2") (pinfunction "LEDK_2") (pintype "unspecified"))
      (node (ref "J17") (pin "3") (pinfunction "GND_3") (pintype "unspecified"))
      (node (ref "J17") (pin "4") (pinfunction "GND_4") (pintype "unspecified"))
      (node (ref "K1") (pin "1") (pinfunction "1_1") (pintype "unspecified"))
      (node (ref "K10") (pin "1") (pinfunction "1_1") (pintype "unspecified"))
      (node (ref "K11") (pin "1") (pinfunction "1_1") (pintype "unspecified"))
      (node (ref "K12") (pin "1") (pinfunction "1_1") (pintype "unspecified"))
      (node (ref "K13") (pin "1") (pinfunction "1_1") (pintype "unspecified"))
      (node (ref "K14") (pin "1") (pinfunction "1_1") (pintype "unspecified"))
      (node (ref "K15") (pin "1") (pinfunction "1_1") (pintype "unspecified"))
      (node (ref "K16") (pin "1") (pinfunction "1_1") (pintype "unspecified"))
      (node (ref "K17") (pin "1") (pinfunction "1_1") (pintype "unspecified"))
      (node (ref "K18") (pin "1") (pinfunction "1_1") (pintype "unspecified"))
      (node (ref "K19") (pin "1") (pinfunction "1_1") (pintype "unspecified"))
      (node (ref "K2") (pin "1") (pinfunction "1_1") (pintype "unspecified"))
      (node (ref "K20") (pin "1") (pinfunction "1_1") (pintype "unspecified"))
      (node (ref "K21") (pin "1") (pinfunction "1_1") (pintype "unspecified"))
      (node (ref "K3") (pin "1") (pinfunction "1_1") (pintype "unspecified"))
      (node (ref "K4") (pin "1") (pinfunction "1_1") (pintype "unspecified"))
      (node (ref "K5") (pin "1") (pinfunction "1_1") (pintype "unspecified"))
      (node (ref "K6") (pin "1") (pinfunction "1_1") (pintype "unspecified"))
      (node (ref "K7") (pin "1") (pinfunction "1_1") (pintype "unspecified"))
      (node (ref "K8") (pin "1") (pinfunction "1_1") (pintype "unspecified"))
      (node (ref "K9") (pin "1") (pinfunction "1_1") (pintype "unspecified"))
      (node (ref "LED1") (pin "1") (pinfunction "K_1") (pintype "unspecified"))
      (node (ref "LED2") (pin "1") (pinfunction "K_1") (pintype "unspecified"))
      (node (ref "MIC1") (pin "2") (pinfunction "GND_2") (pintype "unspecified"))
      (node (ref "MIC1") (pin "3") (pinfunction "GND_3") (pintype "unspecified"))
      (node (ref "Q5") (pin "1") (pinfunction "1_1") (pintype "unspecified"))
      (node (ref "R10") (pin "1") (pinfunction "1_1") (pintype "input"))
      (node (ref "R18") (pin "2") (pinfunction "2_2") (pintype "input"))
      (node (ref "SW1") (pin "1") (pinfunction "1_1") (pintype "unspecified"))
      (node (ref "SW1") (pin "2") (pinfunction "2_2") (pintype "unspecified"))
      (node (ref "U1") (pin "1") (pinfunction "GND_1") (pintype "unspecified"))
      (node (ref "U1") (pin "103") (pinfunction "GND_103") (pintype "unspecified"))
      (node (ref "U1") (pin "104") (pinfunction "GND_104") (pintype "unspecified"))
      (node (ref "U1") (pin "105") (pinfunction "GND_105") (pintype "unspecified"))
      (node (ref "U1") (pin "106") (pinfunction "GND_106") (pintype "unspecified"))
      (node (ref "U1") (pin "107") (pinfunction "GND_107") (pintype "unspecified"))
      (node (ref "U1") (pin "108") (pinfunction "GND_108") (pintype "unspecified"))
      (node (ref "U1") (pin "109") (pinfunction "GND_109") (pintype "unspecified"))
      (node (ref "U1") (pin "116") (pinfunction "GND_116") (pintype "unspecified"))
      (node (ref "U1") (pin "125") (pinfunction "GND_125") (pintype "unspecified"))
      (node (ref "U1") (pin "126") (pinfunction "GND_126") (pintype "unspecified"))
      (node (ref "U1") (pin "17") (pinfunction "GND_17") (pintype "unspecified"))
      (node (ref "U1") (pin "48") (pinfunction "GND_48") (pintype "unspecified"))
      (node (ref "U1") (pin "82") (pinfunction "GND_82") (pintype "unspecified"))
      (node (ref "U1") (pin "89") (pinfunction "GND_89") (pintype "unspecified"))
      (node (ref "U128") (pin "12") (pinfunction "VSSD_12") (pintype "unspecified"))
      (node (ref "U128") (pin "18") (pinfunction "MODE_18") (pintype "unspecified"))
      (node (ref "U128") (pin "24") (pinfunction "VSSSPK_24") (pintype "unspecified"))
      (node (ref "U128") (pin "28") (pinfunction "VSSA_28") (pintype "unspecified"))
      (node (ref "U128") (pin "33") (pinfunction "EP_33") (pintype "unspecified"))
      (node (ref "U129") (pin "7") (pinfunction "GND_7") (pintype "unspecified"))
      (node (ref "U129") (pin "9") (pinfunction "EP_9") (pintype "unspecified"))
      (node (ref "U130") (pin "7") (pinfunction "GND_7") (pintype "unspecified"))
      (node (ref "U130") (pin "9") (pinfunction "EP_9") (pintype "unspecified"))
      (node (ref "U135") (pin "4") (pinfunction "GND_4") (pintype "unspecified"))
      (node (ref "U140") (pin "16") (pinfunction "SPVSS_16") (pintype "unspecified"))
      (node (ref "U140") (pin "8") (pinfunction "VSS_8") (pintype "unspecified"))
      (node (ref "U141") (pin "23") (pinfunction "A1_23") (pintype "unspecified"))
      (node (ref "U141") (pin "24") (pinfunction "A2_24") (pintype "unspecified"))
      (node (ref "U141") (pin "25") (pinfunction "EP_25") (pintype "unspecified"))
      (node (ref "U141") (pin "9") (pinfunction "GND_9") (pintype "unspecified"))
      (node (ref "U16") (pin "4") (pinfunction "GND_4") (pintype "unspecified"))
      (node (ref "U16") (pin "9") (pinfunction "EP_9") (pintype "unspecified"))
      (node (ref "U18") (pin "12") (pinfunction "RTC_XI_12") (pintype "unspecified"))
      (node (ref "U18") (pin "26") (pinfunction "PIO4_26") (pintype "unspecified"))
      (node (ref "U18") (pin "27") (pinfunction "PIO2_27") (pintype "unspecified"))
      (node (ref "U18") (pin "28") (pinfunction "PIO1_28") (pintype "unspecified"))
      (node (ref "U18") (pin "29") (pinfunction "PIO5_29") (pintype "unspecified"))
      (node (ref "U18") (pin "41") (pinfunction "GND_41") (pintype "unspecified"))
      (node (ref "U18") (pin "9") (pinfunction "VDD_USB_9") (pintype "unspecified"))
      (node (ref "U2") (pin "18") (pinfunction "A0_18") (pintype "unspecified"))
      (node (ref "U2") (pin "24") (pinfunction "A2_24") (pintype "unspecified"))
      (node (ref "U2") (pin "25") (pinfunction "EP_25") (pintype "unspecified"))
      (node (ref "U2") (pin "9") (pinfunction "GND_9") (pintype "unspecified"))
      (node (ref "U204") (pin "1") (pinfunction "FOE_1") (pintype "unspecified"))
      (node (ref "U204") (pin "9") (pinfunction "GND_9") (pintype "unspecified"))
      (node (ref "U3") (pin "11") (pinfunction "GND_11") (pintype "unspecified"))
      (node (ref "U3") (pin "7") (pinfunction "SET_7") (pintype "unspecified"))
      (node (ref "U32") (pin "10") (pinfunction "ILIM_10") (pintype "unspecified"))
      (node (ref "U32") (pin "17") (pinfunction "PGND_17") (pintype "unspecified"))
      (node (ref "U32") (pin "18") (pinfunction "PGND_18") (pintype "unspecified"))
      (node (ref "U32") (pin "25") (pinfunction "PAD_25") (pintype "unspecified"))
      (node (ref "U33") (pin "5") (pinfunction "VSS_5") (pintype "unspecified"))
      (node (ref "U39") (pin "1") (pinfunction "CTG_1") (pintype "unspecified"))
      (node (ref "U39") (pin "4") (pinfunction "GND_4") (pintype "unspecified"))
      (node (ref "U39") (pin "6") (pinfunction "QSTRT_6") (pintype "unspecified"))
      (node (ref "U39") (pin "9") (pinfunction "EP_9") (pintype "unspecified"))
      (node (ref "U41") (pin "4") (pinfunction "VSS_4") (pintype "unspecified"))
      (node (ref "U41") (pin "5") (pinfunction "ep_5") (pintype "unspecified"))
      (node (ref "U48") (pin "14") (pinfunction "GND2_14") (pintype "unspecified"))
      (node (ref "U48") (pin "2") (pinfunction "GND_2") (pintype "unspecified"))
      (node (ref "U48") (pin "21") (pinfunction "GND3_21") (pintype "unspecified"))
      (node (ref "U48") (pin "29") (pinfunction "GND4_29") (pintype "unspecified"))
      (node (ref "U48") (pin "35") (pinfunction "GND5_35") (pintype "unspecified"))
      (node (ref "U48") (pin "44") (pinfunction "GND6_44") (pintype "unspecified"))
      (node (ref "U48") (pin "9") (pinfunction "GND1_9") (pintype "unspecified"))
      (node (ref "U64") (pin "1") (pinfunction "GND_1") (pintype "unspecified"))
      (node (ref "U64") (pin "16") (pinfunction "GND_16") (pintype "unspecified"))
      (node (ref "U64") (pin "17") (pinfunction "EP_17") (pintype "unspecified"))
      (node (ref "U64") (pin "3") (pinfunction "GND_3") (pintype "unspecified"))
      (node (ref "U64") (pin "4") (pinfunction "GND_4") (pintype "unspecified"))
      (node (ref "U8") (pin "18") (pinfunction "A0_18") (pintype "unspecified"))
      (node (ref "U8") (pin "23") (pinfunction "A1_23") (pintype "unspecified"))
      (node (ref "U8") (pin "24") (pinfunction "A2_24") (pintype "unspecified"))
      (node (ref "U8") (pin "25") (pinfunction "EP_25") (pintype "unspecified"))
      (node (ref "U8") (pin "9") (pinfunction "GND_9") (pintype "unspecified"))
      (node (ref "USB1") (pin "1") (pinfunction "SHELL_1") (pintype "unspecified"))
      (node (ref "USB1") (pin "2") (pinfunction "SHELL_2") (pintype "unspecified"))
      (node (ref "USB1") (pin "3") (pinfunction "SHELL_3") (pintype "unspecified"))
      (node (ref "USB1") (pin "4") (pinfunction "SHELL_4") (pintype "unspecified"))
      (node (ref "USB1") (pin "A1B12") (pinfunction "GND_A1B12") (pintype "unspecified"))
      (node (ref "USB1") (pin "B1A12") (pinfunction "GND_B1A12") (pintype "unspecified"))
      (node (ref "X1") (pin "2") (pinfunction "GND_2") (pintype "unspecified"))
      (node (ref "X2") (pin "2") (pinfunction "GND_2") (pintype "input"))
    )
    (net (code "51") (name "GNSS_1PPS") (class "Default")
      (node (ref "U1") (pin "124") (pinfunction "PB12_MAC_TXD0_124") (pintype "unspecified"))
      (node (ref "U18") (pin "35") (pinfunction "PIO11_35") (pintype "unspecified"))
    )
    (net (code "52") (name "GNSS_ANT") (class "Default")
      (node (ref "ANT2") (pin "1") (pinfunction "1_1") (pintype "unspecified"))
      (node (ref "C33") (pin "1") (pinfunction "1_1") (pintype "input"))
    )
    (net (code "53") (name "GNSS_BOOT0") (class "Default")
      (node (ref "Q6") (pin "1") (pinfunction "1_1") (pintype "unspecified"))
      (node (ref "U18") (pin "34") (pinfunction "PIO12_34") (pintype "unspecified"))
    )
    (net (code "54") (name "GNSS_PWR") (class "Default")
      (node (ref "U1") (pin "123") (pinfunction "PB13_MAC_MDC_123") (pintype "unspecified"))
      (node (ref "U18") (pin "14") (pinfunction "PIO13_14") (pintype "unspecified"))
    )
    (net (code "55") (name "GNSS_RST#") (class "Default")
      (node (ref "U1") (pin "122") (pinfunction "PB15_MAC_REFCLK_122") (pintype "unspecified"))
      (node (ref "U18") (pin "17") (pinfunction "RESET_N_17") (pintype "unspecified"))
    )
    (net (code "56") (name "I2C0_SCL") (class "Default")
      (node (ref "R13") (pin "1") (pinfunction "1_1") (pintype "input"))
      (node (ref "U1") (pin "119") (pinfunction "PB23_I2C0_SCL_119") (pintype "unspecified"))
      (node (ref "U128") (pin "16") (pinfunction "SCLK_16") (pintype "unspecified"))
      (node (ref "U141") (pin "19") (pinfunction "SCL_19") (pintype "unspecified"))
      (node (ref "U2") (pin "19") (pinfunction "SCL_19") (pintype "unspecified"))
      (node (ref "U204") (pin "5") (pinfunction "SCL_5") (pintype "unspecified"))
      (node (ref "U32") (pin "5") (pinfunction "SCL_5") (pintype "unspecified"))
      (node (ref "U39") (pin "7") (pinfunction "SCL_7") (pintype "unspecified"))
      (node (ref "U41") (pin "2") (pinfunction "SCL_2") (pintype "unspecified"))
      (node (ref "U8") (pin "19") (pinfunction "SCL_19") (pintype "unspecified"))
    )
    (net (code "57") (name "I2C0_SDA") (class "Default")
      (node (ref "R12") (pin "1") (pinfunction "1_1") (pintype "input"))
      (node (ref "U1") (pin "110") (pinfunction "PB24_I2C0_SDA_110") (pintype "unspecified"))
      (node (ref "U128") (pin "17") (pinfunction "SDIO_17") (pintype "unspecified"))
      (node (ref "U141") (pin "20") (pinfunction "SDA_20") (pintype "unspecified"))
      (node (ref "U2") (pin "20") (pinfunction "SDA_20") (pintype "unspecified"))
      (node (ref "U204") (pin "7") (pinfunction "SDA_7") (pintype "unspecified"))
      (node (ref "U32") (pin "6") (pinfunction "SDA_6") (pintype "unspecified"))
      (node (ref "U39") (pin "8") (pinfunction "SDA_8") (pintype "unspecified"))
      (node (ref "U41") (pin "3") (pinfunction "SDA_3") (pintype "unspecified"))
      (node (ref "U8") (pin "20") (pinfunction "SDA_20") (pintype "unspecified"))
    )
    (net (code "58") (name "I2C1_SCL") (class "Default")
      (node (ref "CONN1") (pin "5") (pinfunction "5_5") (pintype "unspecified"))
      (node (ref "R1") (pin "1") (pinfunction "1_1") (pintype "input"))
      (node (ref "U1") (pin "5") (pinfunction "PA00_SLCD_D0_5") (pintype "unspecified"))
      (node (ref "U135") (pin "2") (pinfunction "SCL_2") (pintype "unspecified"))
      (node (ref "U18") (pin "31") (pinfunction "PIO8_31") (pintype "unspecified"))
      (node (ref "U3") (pin "10") (pinfunction "SCL_10") (pintype "unspecified"))
    )
    (net (code "59") (name "I2C1_SDA") (class "Default")
      (node (ref "CONN1") (pin "3") (pinfunction "3_3") (pintype "unspecified"))
      (node (ref "R2") (pin "1") (pinfunction "1_1") (pintype "input"))
      (node (ref "U1") (pin "2") (pinfunction "PA01_SLCD_D1_2") (pintype "unspecified"))
      (node (ref "U135") (pin "1") (pinfunction "SDA_1") (pintype "unspecified"))
      (node (ref "U18") (pin "32") (pinfunction "PIO9_32") (pintype "unspecified"))
      (node (ref "U3") (pin "9") (pinfunction "SDA_9") (pintype "unspecified"))
    )
    (net (code "60") (name "I2S0_FS") (class "Default")
      (node (ref "U1") (pin "49") (pinfunction "PC09_PCM_SYN_49") (pintype "unspecified"))
      (node (ref "U48") (pin "37") (pinfunction "PCM_SYNC_37") (pintype "unspecified"))
    )
    (net (code "61") (name "I2S0_MISO") (class "Default")
      (node (ref "U1") (pin "51") (pinfunction "PC08_PCM_DI_51") (pintype "unspecified"))
      (node (ref "U48") (pin "38") (pinfunction "PCM_OUT_38") (pintype "unspecified"))
    )
    (net (code "62") (name "I2S0_MOSI") (class "Default")
      (node (ref "U1") (pin "50") (pinfunction "PC07_PCM_DO_50") (pintype "unspecified"))
      (node (ref "U48") (pin "39") (pinfunction "PCM_IN_39") (pintype "unspecified"))
    )
    (net (code "63") (name "I2S0_SCK") (class "Default")
      (node (ref "U1") (pin "52") (pinfunction "PC06_PCM_CLK_52") (pintype "unspecified"))
      (node (ref "U48") (pin "36") (pinfunction "PCM_CLK_36") (pintype "unspecified"))
    )
    (net (code "64") (name "I2S1_CS") (class "Default")
      (node (ref "U1") (pin "76") (pinfunction "PB02_I2S_LRCK_76") (pintype "unspecified"))
      (node (ref "U128") (pin "7") (pinfunction "FS_7") (pintype "unspecified"))
    )
    (net (code "65") (name "I2S1_MCLK") (class "Default")
      (node (ref "U1") (pin "72") (pinfunction "PB00_I2S_MCLK_72") (pintype "unspecified"))
      (node (ref "U128") (pin "11") (pinfunction "MCLK_11") (pintype "unspecified"))
    )
    (net (code "66") (name "I2S1_MISO") (class "Default")
      (node (ref "U1") (pin "73") (pinfunction "PB03_I2S_DI_73") (pintype "unspecified"))
      (node (ref "U128") (pin "9") (pinfunction "ADCOUT_9") (pintype "unspecified"))
    )
    (net (code "67") (name "I2S1_MOSI") (class "Default")
      (node (ref "U1") (pin "75") (pinfunction "PB04_I2S_DO_75") (pintype "unspecified"))
      (node (ref "U128") (pin "10") (pinfunction "DACIN_10") (pintype "unspecified"))
    )
    (net (code "68") (name "I2S1_SCLK") (class "Default")
      (node (ref "U1") (pin "74") (pinfunction "PB01_I2S_BCLK_74") (pintype "unspecified"))
      (node (ref "U128") (pin "8") (pinfunction "BCLK_8") (pintype "unspecified"))
    )
    (net (code "69") (name "KEY_#") (class "Default")
      (node (ref "K21") (pin "2") (pinfunction "2_2") (pintype "unspecified"))
      (node (ref "U8") (pin "15") (pinfunction "P15_15") (pintype "unspecified"))
    )
    (net (code "70") (name "KEY_*") (class "Default")
      (node (ref "K19") (pin "2") (pinfunction "2_2") (pintype "unspecified"))
      (node (ref "U8") (pin "17") (pinfunction "P17_17") (pintype "unspecified"))
    )
    (net (code "71") (name "KEY_0") (class "Default")
      (node (ref "K20") (pin "2") (pinfunction "2_2") (pintype "unspecified"))
      (node (ref "U8") (pin "16") (pinfunction "P16_16") (pintype "unspecified"))
    )
    (net (code "72") (name "KEY_1") (class "Default")
      (node (ref "K10") (pin "2") (pinfunction "2_2") (pintype "unspecified"))
      (node (ref "U8") (pin "8") (pinfunction "P07_8") (pintype "unspecified"))
    )
    (net (code "73") (name "KEY_2") (class "Default")
      (node (ref "K11") (pin "2") (pinfunction "2_2") (pintype "unspecified"))
      (node (ref "U8") (pin "6") (pinfunction "P05_6") (pintype "unspecified"))
    )
    (net (code "74") (name "KEY_3") (class "Default")
      (node (ref "K12") (pin "2") (pinfunction "2_2") (pintype "unspecified"))
      (node (ref "U8") (pin "5") (pinfunction "P04_5") (pintype "unspecified"))
    )
    (net (code "75") (name "KEY_4") (class "Default")
      (node (ref "K13") (pin "2") (pinfunction "2_2") (pintype "unspecified"))
      (node (ref "U8") (pin "11") (pinfunction "P11_11") (pintype "unspecified"))
    )
    (net (code "76") (name "KEY_5") (class "Default")
      (node (ref "K14") (pin "2") (pinfunction "2_2") (pintype "unspecified"))
      (node (ref "U8") (pin "10") (pinfunction "P10_10") (pintype "unspecified"))
    )
    (net (code "77") (name "KEY_6") (class "Default")
      (node (ref "K15") (pin "2") (pinfunction "2_2") (pintype "unspecified"))
      (node (ref "U8") (pin "7") (pinfunction "P06_7") (pintype "unspecified"))
    )
    (net (code "78") (name "KEY_7") (class "Default")
      (node (ref "K16") (pin "2") (pinfunction "2_2") (pintype "unspecified"))
      (node (ref "U8") (pin "14") (pinfunction "P14_14") (pintype "unspecified"))
    )
    (net (code "79") (name "KEY_8") (class "Default")
      (node (ref "K17") (pin "2") (pinfunction "2_2") (pintype "unspecified"))
      (node (ref "U8") (pin "13") (pinfunction "P13_13") (pintype "unspecified"))
    )
    (net (code "80") (name "KEY_9") (class "Default")
      (node (ref "K18") (pin "2") (pinfunction "2_2") (pintype "unspecified"))
      (node (ref "U8") (pin "12") (pinfunction "P12_12") (pintype "unspecified"))
    )
    (net (code "81") (name "KEY_CALL") (class "Default")
      (node (ref "K7") (pin "2") (pinfunction "2_2") (pintype "unspecified"))
      (node (ref "U2") (pin "16") (pinfunction "P16_16") (pintype "unspecified"))
    )
    (net (code "82") (name "KEY_CENTER") (class "Default")
      (node (ref "K5") (pin "2") (pinfunction "2_2") (pintype "unspecified"))
      (node (ref "U2") (pin "17") (pinfunction "P17_17") (pintype "unspecified"))
    )
    (net (code "83") (name "KEY_DOWN") (class "Default")
      (node (ref "K8") (pin "2") (pinfunction "2_2") (pintype "unspecified"))
      (node (ref "U8") (pin "4") (pinfunction "P03_4") (pintype "unspecified"))
    )
    (net (code "84") (name "KEY_HANGUP_PWR") (class "Default")
      (node (ref "D1") (pin "1") (pinfunction "C_1") (pintype "unspecified"))
      (node (ref "K9") (pin "2") (pinfunction "2_2") (pintype "unspecified"))
      (node (ref "U32") (pin "12") (pinfunction "QON#_12") (pintype "unspecified"))
    )
    (net (code "85") (name "KEY_LEFT") (class "Default")
      (node (ref "K4") (pin "2") (pinfunction "2_2") (pintype "unspecified"))
      (node (ref "U8") (pin "2") (pinfunction "P01_2") (pintype "unspecified"))
    )
    (net (code "86") (name "KEY_LF_BOOT0") (class "Default")
      (node (ref "FPC1") (pin "2") (pinfunction "2_2") (pintype "unspecified"))
      (node (ref "K1") (pin "2") (pinfunction "2_2") (pintype "unspecified"))
      (node (ref "RN3") (pin "4") (pinfunction "4_4") (pintype "unspecified"))
      (node (ref "U1") (pin "67") (pinfunction "PB28_BOOTSEL_0_67") (pintype "unspecified"))
    )
    (net (code "87") (name "KEY_RF_BOOT1") (class "Default")
      (node (ref "FPC1") (pin "3") (pinfunction "3_3") (pintype "unspecified"))
      (node (ref "K3") (pin "2") (pinfunction "2_2") (pintype "unspecified"))
      (node (ref "R3") (pin "1") (pinfunction "1_1") (pintype "input"))
      (node (ref "U1") (pin "66") (pinfunction "PB29_BOOTSEL_1_66") (pintype "unspecified"))
    )
    (net (code "88") (name "KEY_RIGHT") (class "Default")
      (node (ref "K6") (pin "2") (pinfunction "2_2") (pintype "unspecified"))
      (node (ref "U8") (pin "3") (pinfunction "P02_3") (pintype "unspecified"))
    )
    (net (code "89") (name "KEY_UP") (class "Default")
      (node (ref "K2") (pin "2") (pinfunction "2_2") (pintype "unspecified"))
      (node (ref "U8") (pin "1") (pinfunction "P00_1") (pintype "unspecified"))
    )
    (net (code "90") (name "KP_LED+") (class "Default")
      (node (ref "C39") (pin "2") (pinfunction "2_2") (pintype "input"))
      (node (ref "LED1") (pin "2") (pinfunction "A_2") (pintype "unspecified"))
      (node (ref "LED2") (pin "2") (pinfunction "A_2") (pintype "unspecified"))
      (node (ref "R20") (pin "1") (pinfunction "1_1") (pintype "input"))
    )
    (net (code "91") (name "LCD_D_C") (class "Default")
      (node (ref "J17") (pin "7") (pinfunction "WR_7") (pintype "unspecified"))
      (node (ref "U1") (pin "98") (pinfunction "PB07_MAC_CRSDV_98") (pintype "unspecified"))
    )
    (net (code "92") (name "LCD_LED+") (class "Default")
      (node (ref "C18") (pin "2") (pinfunction "2_2") (pintype "input"))
      (node (ref "J17") (pin "23") (pinfunction "LEDA_23") (pintype "unspecified"))
      (node (ref "J17") (pin "24") (pinfunction "LEDA_24") (pintype "unspecified"))
      (node (ref "Q1") (pin "3") (pinfunction "D_3") (pintype "unspecified"))
    )
    (net (code "93") (name "LCD_RESET#") (class "Default")
      (node (ref "J17") (pin "10") (pinfunction "RESET_10") (pintype "unspecified"))
      (node (ref "U1") (pin "99") (pinfunction "PB10_MAC_TXEN_99") (pintype "unspecified"))
    )
    (net (code "94") (name "LCD_TE") (class "Default")
      (node (ref "J17") (pin "5") (pinfunction "FMARK_5") (pintype "unspecified"))
      (node (ref "U1") (pin "97") (pinfunction "PB06_MAC_PHYCLK_97") (pintype "unspecified"))
    )
    (net (code "95") (name "LED_B") (class "Default")
      (node (ref "LED16") (pin "2") (pinfunction "-_2") (pintype "unspecified"))
      (node (ref "U3") (pin "3") (pinfunction "LED2_3") (pintype "unspecified"))
    )
    (net (code "96") (name "LED_G") (class "Default")
      (node (ref "LED16") (pin "3") (pinfunction "-_3") (pintype "unspecified"))
      (node (ref "U3") (pin "2") (pinfunction "LED1_2") (pintype "unspecified"))
    )
    (net (code "97") (name "LED_R") (class "Default")
      (node (ref "LED16") (pin "4") (pinfunction "-_4") (pintype "unspecified"))
      (node (ref "U3") (pin "1") (pinfunction "LED0_1") (pintype "unspecified"))
    )
    (net (code "98") (name "Lora_0_ANT") (class "Default")
      (node (ref "U64") (pin "13") (pinfunction "ANT_13") (pintype "unspecified"))
    )
    (net (code "99") (name "Lora_0_BUSY") (class "Default")
      (node (ref "U1") (pin "42") (pinfunction "PC17_42") (pintype "unspecified"))
      (node (ref "U64") (pin "9") (pinfunction "BUSY_9") (pintype "unspecified"))
    )
    (net (code "100") (name "Lora_0_DIO1") (class "Default")
      (node (ref "U1") (pin "41") (pinfunction "PC16_41") (pintype "unspecified"))
      (node (ref "U64") (pin "8") (pinfunction "DIO1_8") (pintype "unspecified"))
    )
    (net (code "101") (name "Lora_0_DIO2") (class "Default")
      (node (ref "U1") (pin "40") (pinfunction "PC22_40") (pintype "unspecified"))
      (node (ref "U64") (pin "7") (pinfunction "DIO2_7") (pintype "unspecified"))
    )
    (net (code "102") (name "Lora_0_NRST") (class "Default")
      (node (ref "U1") (pin "43") (pinfunction "PC23_43") (pintype "unspecified"))
      (node (ref "U64") (pin "10") (pinfunction "NRST_10") (pintype "unspecified"))
    )
    (net (code "103") (name "Net-(ANT1-Pad1)") (class "Default")
      (node (ref "ANT1") (pin "1") (pinfunction "1_1") (pintype "unspecified"))
      (node (ref "R49") (pin "2") (pinfunction "2_2") (pintype "input"))
    )
    (net (code "104") (name "Net-(C22-Pad1)") (class "Default")
      (node (ref "C22") (pin "1") (pinfunction "1_1") (pintype "unspecified"))
      (node (ref "R15") (pin "1") (pinfunction "1_1") (pintype "input"))
    )
    (net (code "105") (name "Net-(C26-Pad1)") (class "Default")
      (node (ref "C26") (pin "1") (pinfunction "1_1") (pintype "unspecified"))
      (node (ref "R17") (pin "1") (pinfunction "1_1") (pintype "input"))
    )
    (net (code "106") (name "Net-(C31-Pad1)") (class "Default")
      (node (ref "C31") (pin "1") (pinfunction "1_1") (pintype "input"))
      (node (ref "R19") (pin "2") (pinfunction "2_2") (pintype "input"))
    )
    (net (code "107") (name "Net-(C33-Pad2)") (class "Default")
      (node (ref "C33") (pin "2") (pinfunction "2_2") (pintype "input"))
      (node (ref "C41") (pin "2") (pinfunction "2_2") (pintype "input"))
      (node (ref "L1") (pin "1") (pinfunction "1_1") (pintype "unspecified"))
    )
    (net (code "108") (name "Net-(MIC1-OUT)") (class "Default")
      (node (ref "C7") (pin "1") (pinfunction "1_1") (pintype "unspecified"))
      (node (ref "MIC1") (pin "4") (pinfunction "OUT_4") (pintype "unspecified"))
    )
    (net (code "109") (name "Net-(Q2-D)") (class "Default")
      (node (ref "Q2") (pin "3") (pinfunction "D_3") (pintype "unspecified"))
      (node (ref "R20") (pin "2") (pinfunction "2_2") (pintype "input"))
    )
    (net (code "110") (name "Net-(R49-Pad1)") (class "Default")
      (node (ref "R49") (pin "1") (pinfunction "1_1") (pintype "input"))
      (node (ref "R54") (pin "2") (pinfunction "2_2") (pintype "input"))
    )
    (net (code "111") (name "Net-(U1-USB_VBUS)") (class "Default")
      (node (ref "R8") (pin "1") (pinfunction "1_1") (pintype "input"))
      (node (ref "U1") (pin "87") (pinfunction "USB_VBUS_87") (pintype "unspecified"))
    )
    (net (code "112") (name "Net-(U18-LDO_B_OUT)") (class "Default")
      (node (ref "C45") (pin "2") (pinfunction "2_2") (pintype "unspecified"))
      (node (ref "U18") (pin "5") (pinfunction "LDO_B_OUT_5") (pintype "unspecified"))
    )
    (net (code "113") (name "Net-(U18-LDO_C_OUT)") (class "Default")
      (node (ref "C50") (pin "1") (pinfunction "1_1") (pintype "unspecified"))
      (node (ref "U18") (pin "24") (pinfunction "LDO_C_OUT_24") (pintype "unspecified"))
    )
    (net (code "114") (name "Net-(U18-LDO_RF_OUT)") (class "Default")
      (node (ref "C43") (pin "1") (pinfunction "1_1") (pintype "unspecified"))
      (node (ref "U18") (pin "1") (pinfunction "VDD_ANA_1") (pintype "unspecified"))
      (node (ref "U18") (pin "38") (pinfunction "LDO_RF_OUT_38") (pintype "unspecified"))
      (node (ref "U18") (pin "39") (pinfunction "VDD_LNA_39") (pintype "unspecified"))
    )
    (net (code "115") (name "Net-(U18-LDO_X_OUT)") (class "Default")
      (node (ref "C48") (pin "1") (pinfunction "1_1") (pintype "unspecified"))
      (node (ref "U18") (pin "2") (pinfunction "LDO_X_OUT_2") (pintype "unspecified"))
      (node (ref "X2") (pin "1") (pinfunction "OE#_1") (pintype "input"))
      (node (ref "X2") (pin "4") (pinfunction "VDD_4") (pintype "input"))
    )
    (net (code "116") (name "Net-(U18-LNA_IN)") (class "Default")
      (node (ref "L1") (pin "2") (pinfunction "2_2") (pintype "unspecified"))
      (node (ref "U18") (pin "40") (pinfunction "LNA_IN_40") (pintype "unspecified"))
    )
    (net (code "117") (name "Net-(U18-V_CORE)") (class "Default")
      (node (ref "C44") (pin "1") (pinfunction "1_1") (pintype "input"))
      (node (ref "L3") (pin "1") (pinfunction "1_1") (pintype "unspecified"))
      (node (ref "U18") (pin "23") (pinfunction "V_CORE_23") (pintype "unspecified"))
    )
    (net (code "118") (name "Net-(U18-V_DCDC_OUT)") (class "Default")
      (node (ref "L3") (pin "2") (pinfunction "2_2") (pintype "unspecified"))
      (node (ref "U18") (pin "22") (pinfunction "V_DCDC_OUT_22") (pintype "unspecified"))
    )
    (net (code "119") (name "Net-(U18-XTAL_I)") (class "Default")
      (node (ref "U18") (pin "3") (pinfunction "XTAL_I_3") (pintype "unspecified"))
      (node (ref "X2") (pin "3") (pinfunction "OUT_3") (pintype "input"))
    )
    (net (code "120") (name "Net-(U32-BTST)") (class "Default")
      (node (ref "C3") (pin "1") (pinfunction "1_1") (pintype "unspecified"))
      (node (ref "U32") (pin "21") (pinfunction "BTST_21") (pintype "unspecified"))
    )
    (net (code "121") (name "Net-(U32-PMID)") (class "Default")
      (node (ref "C2") (pin "1") (pinfunction "1_1") (pintype "input"))
      (node (ref "U32") (pin "23") (pinfunction "PMID_23") (pintype "unspecified"))
    )
    (net (code "122") (name "Net-(U32-REGN)") (class "Default")
      (node (ref "C122") (pin "1") (pinfunction "1_1") (pintype "input"))
      (node (ref "R7") (pin "1") (pinfunction "1_1") (pintype "input"))
      (node (ref "U32") (pin "22") (pinfunction "REGN_22") (pintype "unspecified"))
    )
    (net (code "123") (name "Net-(U48-LPO)") (class "Default")
      (node (ref "R10") (pin "2") (pinfunction "2_2") (pintype "input"))
      (node (ref "R11") (pin "2") (pinfunction "2_2") (pintype "input"))
      (node (ref "U48") (pin "31") (pinfunction "LPO_31") (pintype "unspecified"))
    )
    (net (code "124") (name "Net-(U129-BIAS)") (class "Default")
      (node (ref "C21") (pin "2") (pinfunction "2_2") (pintype "unspecified"))
      (node (ref "U129") (pin "2") (pinfunction "BIAS_2") (pintype "unspecified"))
      (node (ref "U129") (pin "3") (pinfunction "IN+_3") (pintype "unspecified"))
    )
    (net (code "125") (name "Net-(U129-IN-)") (class "Default")
      (node (ref "R14") (pin "2") (pinfunction "2_2") (pintype "input"))
      (node (ref "R15") (pin "2") (pinfunction "2_2") (pintype "input"))
      (node (ref "U129") (pin "4") (pinfunction "IN-_4") (pintype "unspecified"))
    )
    (net (code "126") (name "Net-(U130-BIAS)") (class "Default")
      (node (ref "C27") (pin "2") (pinfunction "2_2") (pintype "unspecified"))
      (node (ref "U130") (pin "2") (pinfunction "BIAS_2") (pintype "unspecified"))
      (node (ref "U130") (pin "3") (pinfunction "IN+_3") (pintype "unspecified"))
    )
    (net (code "127") (name "Net-(U130-IN-)") (class "Default")
      (node (ref "R16") (pin "2") (pinfunction "2_2") (pintype "input"))
      (node (ref "R17") (pin "2") (pinfunction "2_2") (pintype "input"))
      (node (ref "U130") (pin "4") (pinfunction "IN-_4") (pintype "unspecified"))
    )
    (net (code "128") (name "PHONE_MIC") (class "Default")
      (node (ref "C5") (pin "2") (pinfunction "2_2") (pintype "unspecified"))
    )
    (net (code "129") (name "PMIC_CE") (class "Default")
      (node (ref "U2") (pin "8") (pinfunction "P07_8") (pintype "unspecified"))
      (node (ref "U32") (pin "9") (pinfunction "CE#_9") (pintype "unspecified"))
    )
    (net (code "130") (name "PMIC_OTG") (class "Default")
      (node (ref "U2") (pin "10") (pinfunction "P10_10") (pintype "unspecified"))
      (node (ref "U32") (pin "8") (pinfunction "OTG_8") (pintype "unspecified"))
    )
    (net (code "131") (name "PMIC_SW") (class "Default")
      (node (ref "C3") (pin "2") (pinfunction "2_2") (pintype "unspecified"))
      (node (ref "L4") (pin "1") (pinfunction "1_1") (pintype "unspecified"))
      (node (ref "U32") (pin "19") (pinfunction "SW_19") (pintype "unspecified"))
      (node (ref "U32") (pin "20") (pinfunction "SW_20") (pintype "unspecified"))
    )
    (net (code "132") (name "PMIC_TS") (class "Default")
      (node (ref "R18") (pin "1") (pinfunction "1_1") (pintype "input"))
      (node (ref "R7") (pin "2") (pinfunction "2_2") (pintype "input"))
      (node (ref "U32") (pin "11") (pinfunction "TS_11") (pintype "unspecified"))
    )
    (net (code "133") (name "PSW_3V3_KPBL#") (class "Default")
      (node (ref "Q2") (pin "1") (pinfunction "G_1") (pintype "unspecified"))
      (node (ref "U1") (pin "64") (pinfunction "PC25_PWM0_64") (pintype "unspecified"))
    )
    (net (code "134") (name "PSW_3V3_LCDBL#") (class "Default")
      (node (ref "Q1") (pin "1") (pinfunction "G_1") (pintype "unspecified"))
      (node (ref "U1") (pin "65") (pinfunction "PC24_PWM4_65") (pintype "unspecified"))
    )
    (net (code "135") (name "PSW_AAMP_EARP") (class "Default")
      (node (ref "U130") (pin "1") (pinfunction "SHDN_1") (pintype "unspecified"))
      (node (ref "U2") (pin "13") (pinfunction "P13_13") (pintype "unspecified"))
    )
    (net (code "136") (name "PSW_AAMP_SPK") (class "Default")
      (node (ref "U129") (pin "1") (pinfunction "SHDN_1") (pintype "unspecified"))
      (node (ref "U2") (pin "14") (pinfunction "P14_14") (pintype "unspecified"))
    )
    (net (code "137") (name "SDIO_WiFi_CLK") (class "Default")
      (node (ref "U1") (pin "56") (pinfunction "PC00_MSC1_CLK_56") (pintype "unspecified"))
      (node (ref "U48") (pin "24") (pinfunction "SDIO_DATA_CLK_24") (pintype "unspecified"))
    )
    (net (code "138") (name "SDIO_WiFi_CMD") (class "Default")
      (node (ref "R29") (pin "1") (pinfunction "1_1") (pintype "input"))
      (node (ref "U1") (pin "58") (pinfunction "PC01_MSC1_CMD_58") (pintype "unspecified"))
      (node (ref "U48") (pin "23") (pinfunction "SDIO_DATA_CMD_23") (pintype "unspecified"))
    )
    (net (code "139") (name "SDIO_WiFi_D0") (class "Default")
      (node (ref "RN1") (pin "2") (pinfunction "2_2") (pintype "unspecified"))
      (node (ref "U1") (pin "57") (pinfunction "PC02_MSC1_D0_57") (pintype "unspecified"))
      (node (ref "U48") (pin "26") (pinfunction "SDIO_DATA_0_26") (pintype "unspecified"))
    )
    (net (code "140") (name "SDIO_WiFi_D1") (class "Default")
      (node (ref "RN1") (pin "4") (pinfunction "4_4") (pintype "unspecified"))
      (node (ref "U1") (pin "55") (pinfunction "PC03_MSC1_D1_55") (pintype "unspecified"))
      (node (ref "U48") (pin "28") (pinfunction "SDIO_DATA_1_28") (pintype "unspecified"))
    )
    (net (code "141") (name "SDIO_WiFi_D2") (class "Default")
      (node (ref "RN1") (pin "1") (pinfunction "1_1") (pintype "unspecified"))
      (node (ref "U1") (pin "53") (pinfunction "PC04_MSC1_D2_53") (pintype "unspecified"))
      (node (ref "U48") (pin "25") (pinfunction "SDIO_DATA_2_25") (pintype "unspecified"))
    )
    (net (code "142") (name "SDIO_WiFi_D3") (class "Default")
      (node (ref "RN1") (pin "3") (pinfunction "3_3") (pintype "unspecified"))
      (node (ref "U1") (pin "54") (pinfunction "PC05_MSC1_D3_54") (pintype "unspecified"))
      (node (ref "U48") (pin "27") (pinfunction "SDIO_DATA_3_27") (pintype "unspecified"))
    )
    (net (code "143") (name "SD_CLK") (class "Default")
      (node (ref "U1") (pin "34") (pinfunction "PA24_MSC0_CLK_34") (pintype "unspecified"))
      (node (ref "U16") (pin "3") (pinfunction "CLK_3") (pintype "unspecified"))
    )
    (net (code "144") (name "SD_CMD") (class "Default")
      (node (ref "R4") (pin "1") (pinfunction "1_1") (pintype "input"))
      (node (ref "U1") (pin "35") (pinfunction "PA25_MSC0_CMD_35") (pintype "unspecified"))
      (node (ref "U16") (pin "5") (pinfunction "CMD_5") (pintype "unspecified"))
    )
    (net (code "145") (name "SD_D0") (class "Default")
      (node (ref "RN2") (pin "4") (pinfunction "4_4") (pintype "unspecified"))
      (node (ref "U1") (pin "33") (pinfunction "PA23_MSC0_D0_33") (pintype "unspecified"))
      (node (ref "U16") (pin "6") (pinfunction "DAT0_6") (pintype "unspecified"))
    )
    (net (code "146") (name "SD_D1") (class "Default")
      (node (ref "RN2") (pin "3") (pinfunction "3_3") (pintype "unspecified"))
      (node (ref "U1") (pin "32") (pinfunction "PA22_MSC0_D1_32") (pintype "unspecified"))
      (node (ref "U16") (pin "7") (pinfunction "DAT1_7") (pintype "unspecified"))
    )
    (net (code "147") (name "SD_D2") (class "Default")
      (node (ref "RN2") (pin "1") (pinfunction "1_1") (pintype "unspecified"))
      (node (ref "U1") (pin "31") (pinfunction "PA21_MSC0_D2_31") (pintype "unspecified"))
      (node (ref "U16") (pin "1") (pinfunction "DAT2_1") (pintype "unspecified"))
    )
    (net (code "148") (name "SD_D3") (class "Default")
      (node (ref "RN2") (pin "2") (pinfunction "2_2") (pintype "unspecified"))
      (node (ref "U1") (pin "30") (pinfunction "PA20_MSC0_D3_30") (pintype "unspecified"))
      (node (ref "U16") (pin "2") (pinfunction "DAT3_2") (pintype "unspecified"))
    )
    (net (code "149") (name "SPIHW_CS") (class "Default")
      (node (ref "J17") (pin "9") (pinfunction "CS_9") (pintype "unspecified"))
      (node (ref "U1") (pin "70") (pinfunction "PD01_SPI_CS_I2C2_SDA_70") (pintype "unspecified"))
    )
    (net (code "150") (name "SPIHW_MISO") (class "Default")
      (node (ref "U1") (pin "68") (pinfunction "PD03_SPI_MISO_UART1_TX_68") (pintype "unspecified"))
    )
    (net (code "151") (name "SPIHW_MOSI") (class "Default")
      (node (ref "J17") (pin "6") (pinfunction "SDA_6") (pintype "unspecified"))
      (node (ref "U1") (pin "69") (pinfunction "PD02_SPI_MOSI_UART1_RX_69") (pintype "unspecified"))
    )
    (net (code "152") (name "SPIHW_SCLK") (class "Default")
      (node (ref "J17") (pin "8") (pinfunction "SCL_8") (pintype "unspecified"))
      (node (ref "U1") (pin "71") (pinfunction "PD00_SPI_SCK_I2C2_SCL_71") (pintype "unspecified"))
    )
    (net (code "153") (name "SPISW_CS_L0") (class "Default")
      (node (ref "U1") (pin "12") (pinfunction "PB20_SLCD_D_C#_12") (pintype "unspecified"))
      (node (ref "U64") (pin "15") (pinfunction "NSS_15") (pintype "unspecified"))
    )
    (net (code "154") (name "SPISW_MISO") (class "Default")
      (node (ref "U1") (pin "9") (pinfunction "PB19_SLCD_TE_9") (pintype "unspecified"))
      (node (ref "U64") (pin "11") (pinfunction "MISO_11") (pintype "unspecified"))
    )
    (net (code "155") (name "SPISW_MOSI") (class "Default")
      (node (ref "U1") (pin "8") (pinfunction "PB18_SLCD_CS#_8") (pintype "unspecified"))
      (node (ref "U64") (pin "14") (pinfunction "MOSI_14") (pintype "unspecified"))
    )
    (net (code "156") (name "SPISW_SCLK") (class "Default")
      (node (ref "U1") (pin "10") (pinfunction "PB17_SLCD_WR#_10") (pintype "unspecified"))
      (node (ref "U64") (pin "12") (pinfunction "SCK_12") (pintype "unspecified"))
    )
    (net (code "157") (name "SPK_1") (class "Default")
      (node (ref "U129") (pin "8") (pinfunction "OUT-_8") (pintype "unspecified"))
    )
    (net (code "158") (name "SPK_2") (class "Default")
      (node (ref "R14") (pin "1") (pinfunction "1_1") (pintype "input"))
      (node (ref "U129") (pin "5") (pinfunction "OUT+_5") (pintype "unspecified"))
    )
    (net (code "159") (name "UART2_RX") (class "Default")
      (node (ref "FPC1") (pin "10") (pinfunction "10_10") (pintype "unspecified"))
      (node (ref "Q3") (pin "1") (pinfunction "1_1") (pintype "unspecified"))
      (node (ref "U1") (pin "111") (pinfunction "PD05_UART2_RX_UART1_RTS_111") (pintype "unspecified"))
    )
    (net (code "160") (name "UART2_TX") (class "Default")
      (node (ref "FPC1") (pin "11") (pinfunction "11_11") (pintype "unspecified"))
      (node (ref "Q4") (pin "1") (pinfunction "1_1") (pintype "unspecified"))
      (node (ref "U1") (pin "112") (pinfunction "PD04_UART2_TX_UART1_CTS_112") (pintype "unspecified"))
    )
    (net (code "161") (name "UART_BT_CTS_CPU_RTS") (class "Default")
      (node (ref "U1") (pin "38") (pinfunction "PC13_UART0_RTS_38") (pintype "unspecified"))
      (node (ref "U48") (pin "42") (pinfunction "UART_CTS_N_42") (pintype "unspecified"))
    )
    (net (code "162") (name "UART_BT_RTS_CPU_CTS") (class "Default")
      (node (ref "U1") (pin "39") (pinfunction "PC12_UART0_CTS_39") (pintype "unspecified"))
      (node (ref "U48") (pin "43") (pinfunction "UART_RTS_N_43") (pintype "unspecified"))
    )
    (net (code "163") (name "UART_BT_RX_CPU_TX") (class "Default")
      (node (ref "U1") (pin "37") (pinfunction "PC11_UART0_TX_37") (pintype "unspecified"))
      (node (ref "U48") (pin "41") (pinfunction "UART_RXD_41") (pintype "unspecified"))
    )
    (net (code "164") (name "UART_BT_TX_CPU_RX") (class "Default")
      (node (ref "U1") (pin "36") (pinfunction "PC10_UART0_RX_36") (pintype "unspecified"))
      (node (ref "U48") (pin "40") (pinfunction "UART_TXD_40") (pintype "unspecified"))
    )
    (net (code "165") (name "UART_GNSS_RX_CPU_TX") (class "Default")
      (node (ref "U1") (pin "13") (pinfunction "PA05_SLCD_D5_13") (pintype "unspecified"))
      (node (ref "U18") (pin "18") (pinfunction "PIO7_18") (pintype "unspecified"))
    )
    (net (code "166") (name "UART_GNSS_TX_CPU_RX") (class "Default")
      (node (ref "U1") (pin "11") (pinfunction "PA04_SLCD_D4_11") (pintype "unspecified"))
      (node (ref "U18") (pin "19") (pinfunction "PIO6_19") (pintype "unspecified"))
    )
    (net (code "167") (name "USB_CC1") (class "Default")
      (node (ref "U135") (pin "6") (pinfunction "CC1_6") (pintype "unspecified"))
      (node (ref "USB1") (pin "A5") (pinfunction "CC1_A5") (pintype "unspecified"))
    )
    (net (code "168") (name "USB_CC2") (class "Default")
      (node (ref "U135") (pin "7") (pinfunction "CC2_7") (pintype "unspecified"))
      (node (ref "USB1") (pin "B5") (pinfunction "CC2_B5") (pintype "unspecified"))
    )
    (net (code "169") (name "USB_D+") (class "Default")
      (node (ref "U1") (pin "86") (pinfunction "USB_D+_86") (pintype "unspecified"))
      (node (ref "USB1") (pin "A6") (pinfunction "DP1_A6") (pintype "unspecified"))
      (node (ref "USB1") (pin "B6") (pinfunction "DP2_B6") (pintype "unspecified"))
    )
    (net (code "170") (name "USB_D-") (class "Default")
      (node (ref "U1") (pin "85") (pinfunction "USB_D-_85") (pintype "unspecified"))
      (node (ref "USB1") (pin "A7") (pinfunction "DN1_A7") (pintype "unspecified"))
      (node (ref "USB1") (pin "B7") (pinfunction "DN2_B7") (pintype "unspecified"))
    )
    (net (code "171") (name "USB_ID") (class "Default")
      (node (ref "U1") (pin "117") (pinfunction "PC21_117") (pintype "unspecified"))
      (node (ref "U1") (pin "88") (pinfunction "USB_ID_88") (pintype "unspecified"))
      (node (ref "U135") (pin "3") (pinfunction "ID_3") (pintype "unspecified"))
    )
    (net (code "172") (name "USB_SBU1") (class "Default")
      (node (ref "USB1") (pin "A8") (pinfunction "SBU1_A8") (pintype "unspecified"))
    )
    (net (code "173") (name "USB_SBU2") (class "Default")
      (node (ref "USB1") (pin "B8") (pinfunction "SBU2_B8") (pintype "unspecified"))
    )
    (net (code "174") (name "VBUS") (class "Default")
      (node (ref "C20") (pin "2") (pinfunction "2_2") (pintype "unspecified"))
      (node (ref "R8") (pin "2") (pinfunction "2_2") (pintype "input"))
      (node (ref "U135") (pin "8") (pinfunction "VBUS_8") (pintype "unspecified"))
      (node (ref "U32") (pin "1") (pinfunction "VBUS_1") (pintype "unspecified"))
      (node (ref "USB1") (pin "A4B9") (pinfunction "VBUS_A4B9") (pintype "unspecified"))
      (node (ref "USB1") (pin "B4A9") (pinfunction "VBUS_B4A9") (pintype "unspecified"))
    )
    (net (code "175") (name "VDD_RTC_BAT") (class "Default")
      (node (ref "C40") (pin "2") (pinfunction "2_2") (pintype "input"))
      (node (ref "D3") (pin "1") (pinfunction "C_1") (pintype "unspecified"))
      (node (ref "U204") (pin "3") (pinfunction "VBAT_3") (pintype "unspecified"))
    )
    (net (code "176") (name "VSYS") (class "Default")
      (node (ref "C135") (pin "1") (pinfunction "1_1") (pintype "unspecified"))
      (node (ref "C136") (pin "1") (pinfunction "1_1") (pintype "unspecified"))
      (node (ref "C24") (pin "2") (pinfunction "2_2") (pintype "input"))
      (node (ref "C25") (pin "2") (pinfunction "2_2") (pintype "input"))
      (node (ref "L4") (pin "2") (pinfunction "2_2") (pintype "unspecified"))
      (node (ref "U1") (pin "15") (pinfunction "VSYS_15") (pintype "unspecified"))
      (node (ref "U1") (pin "16") (pinfunction "VSYS_16") (pintype "unspecified"))
      (node (ref "U129") (pin "6") (pinfunction "VCC_6") (pintype "unspecified"))
      (node (ref "U130") (pin "6") (pinfunction "VCC_6") (pintype "unspecified"))
      (node (ref "U32") (pin "15") (pinfunction "SYS_15") (pintype "unspecified"))
      (node (ref "U32") (pin "16") (pinfunction "SYS_16") (pintype "unspecified"))
    )
    (net (code "177") (name "WL_BT_REG_EN") (class "Default")
      (node (ref "U2") (pin "3") (pinfunction "P02_3") (pintype "unspecified"))
      (node (ref "U48") (pin "5") (pinfunction "BT_REG_ON_5") (pintype "unspecified"))
    )
    (net (code "178") (name "WL_BT_WAKE_HOST") (class "Default")
      (node (ref "U2") (pin "4") (pinfunction "P03_4") (pintype "unspecified"))
      (node (ref "U48") (pin "4") (pinfunction "BT_HOST_WAKE_4") (pintype "unspecified"))
    )
    (net (code "179") (name "WL_HOST_WAKE_BT") (class "Default")
      (node (ref "U2") (pin "5") (pinfunction "P04_5") (pintype "unspecified"))
      (node (ref "U48") (pin "3") (pinfunction "BT_WAKE_3") (pintype "unspecified"))
    )
    (net (code "180") (name "WL_REG_EN") (class "Default")
      (node (ref "U2") (pin "2") (pinfunction "P01_2") (pintype "unspecified"))
      (node (ref "U48") (pin "20") (pinfunction "WL_REG_ON_20") (pintype "unspecified"))
    )
    (net (code "181") (name "WL_WAKE_HOST") (class "Default")
      (node (ref "U2") (pin "1") (pinfunction "P00_1") (pintype "unspecified"))
      (node (ref "U48") (pin "19") (pinfunction "WL_HOST_WAKE_19") (pintype "unspecified"))
    )
    (net (code "182") (name "WiFi_ANT_PORT") (class "Default")
      (node (ref "R54") (pin "1") (pinfunction "1_1") (pintype "input"))
      (node (ref "U48") (pin "1") (pinfunction "WL_BT_ANT_1") (pintype "unspecified"))
    )
    (net (code "183") (name "WiFi_VIN_LDO") (class "Default")
      (node (ref "C71") (pin "1") (pinfunction "1_1") (pintype "input"))
      (node (ref "L2") (pin "1") (pinfunction "1_1") (pintype "unspecified"))
      (node (ref "U48") (pin "32") (pinfunction "VIN_LDO_32") (pintype "unspecified"))
    )
    (net (code "184") (name "WiFi_VIN_LDO_OUT") (class "Default")
      (node (ref "L2") (pin "2") (pinfunction "2_2") (pintype "unspecified"))
      (node (ref "U48") (pin "34") (pinfunction "VIN_LDO_OUT_34") (pintype "unspecified"))
    )
    (net (code "185") (name "Y762_A0") (class "Default")
      (node (ref "U140") (pin "30") (pinfunction "A0_30") (pintype "unspecified"))
      (node (ref "U141") (pin "15") (pinfunction "P15_15") (pintype "unspecified"))
    )
    (net (code "186") (name "Y762_AOUT_L") (class "Default")
      (node (ref "C37") (pin "2") (pinfunction "2_2") (pintype "input"))
      (node (ref "U140") (pin "10") (pinfunction "HPOUT-L/MONO_10") (pintype "unspecified"))
    )
    (net (code "187") (name "Y762_AOUT_R") (class "Default")
      (node (ref "C35") (pin "2") (pinfunction "2_2") (pintype "input"))
      (node (ref "U140") (pin "11") (pinfunction "HPOUT_R_11") (pintype "unspecified"))
    )
    (net (code "188") (name "Y762_CLK_EN") (class "Default")
      (node (ref "U141") (pin "11") (pinfunction "P11_11") (pintype "unspecified"))
      (node (ref "X1") (pin "1") (pinfunction "TRI_1") (pintype "unspecified"))
    )
    (net (code "189") (name "Y762_CS#") (class "Default")
      (node (ref "U140") (pin "29") (pinfunction "CS#_29") (pintype "unspecified"))
      (node (ref "U141") (pin "16") (pinfunction "P16_16") (pintype "unspecified"))
    )
    (net (code "190") (name "Y762_D0") (class "Default")
      (node (ref "U140") (pin "27") (pinfunction "D0_27") (pintype "unspecified"))
      (node (ref "U141") (pin "1") (pinfunction "P00_1") (pintype "unspecified"))
    )
    (net (code "191") (name "Y762_D1") (class "Default")
      (node (ref "U140") (pin "26") (pinfunction "D1_26") (pintype "unspecified"))
      (node (ref "U141") (pin "2") (pinfunction "P01_2") (pintype "unspecified"))
    )
    (net (code "192") (name "Y762_D2") (class "Default")
      (node (ref "U140") (pin "25") (pinfunction "D2_25") (pintype "unspecified"))
      (node (ref "U141") (pin "3") (pinfunction "P02_3") (pintype "unspecified"))
    )
    (net (code "193") (name "Y762_D3") (class "Default")
      (node (ref "U140") (pin "24") (pinfunction "D3_24") (pintype "unspecified"))
      (node (ref "U141") (pin "4") (pinfunction "P03_4") (pintype "unspecified"))
    )
    (net (code "194") (name "Y762_D4") (class "Default")
      (node (ref "U140") (pin "23") (pinfunction "D4_23") (pintype "unspecified"))
      (node (ref "U141") (pin "5") (pinfunction "P04_5") (pintype "unspecified"))
    )
    (net (code "195") (name "Y762_D5") (class "Default")
      (node (ref "U140") (pin "22") (pinfunction "D5_22") (pintype "unspecified"))
      (node (ref "U141") (pin "6") (pinfunction "P05_6") (pintype "unspecified"))
    )
    (net (code "196") (name "Y762_D6") (class "Default")
      (node (ref "U140") (pin "21") (pinfunction "D6_21") (pintype "unspecified"))
      (node (ref "U141") (pin "7") (pinfunction "P06_7") (pintype "unspecified"))
    )
    (net (code "197") (name "Y762_D7") (class "Default")
      (node (ref "U140") (pin "20") (pinfunction "D7_20") (pintype "unspecified"))
      (node (ref "U141") (pin "8") (pinfunction "P07_8") (pintype "unspecified"))
    )
    (net (code "198") (name "Y762_IRQ#") (class "Default")
      (node (ref "U140") (pin "3") (pinfunction "IRQ#_3") (pintype "unspecified"))
      (node (ref "U141") (pin "13") (pinfunction "P13_13") (pintype "unspecified"))
    )
    (net (code "199") (name "Y762_LED") (class "Default")
      (node (ref "U140") (pin "2") (pinfunction "LED_2") (pintype "unspecified"))
    )
    (net (code "200") (name "Y762_MTR") (class "Default")
      (node (ref "U140") (pin "19") (pinfunction "MTR_19") (pintype "unspecified"))
    )
    (net (code "201") (name "Y762_PLLC") (class "Default")
      (node (ref "R19") (pin "1") (pinfunction "1_1") (pintype "input"))
      (node (ref "U140") (pin "6") (pinfunction "PLLC_6") (pintype "unspecified"))
    )
    (net (code "202") (name "Y762_RD#") (class "Default")
      (node (ref "U140") (pin "31") (pinfunction "RD#_31") (pintype "unspecified"))
      (node (ref "U141") (pin "14") (pinfunction "P14_14") (pintype "unspecified"))
    )
    (net (code "203") (name "Y762_RST#") (class "Default")
      (node (ref "U140") (pin "4") (pinfunction "RST#_4") (pintype "unspecified"))
      (node (ref "U141") (pin "12") (pinfunction "P12_12") (pintype "unspecified"))
    )
    (net (code "204") (name "Y762_VREF") (class "Default")
      (node (ref "C30") (pin "2") (pinfunction "2_2") (pintype "input"))
      (node (ref "U140") (pin "9") (pinfunction "VREF_9") (pintype "unspecified"))
    )
    (net (code "205") (name "Y762_WR#") (class "Default")
      (node (ref "U140") (pin "28") (pinfunction "WR#_28") (pintype "unspecified"))
      (node (ref "U141") (pin "17") (pinfunction "P17_17") (pintype "unspecified"))
    )
    (net (code "206") (name "unconnected-(ANT1-Pad2)") (class "Default")
      (node (ref "ANT1") (pin "2") (pinfunction "2_2") (pintype "unspecified+no_connect"))
    )
    (net (code "207") (name "unconnected-(ANT2-Pad2)") (class "Default")
      (node (ref "ANT2") (pin "2") (pinfunction "2_2") (pintype "unspecified+no_connect"))
    )
    (net (code "208") (name "unconnected-(BAT1-NTC-Pad2)") (class "Default")
      (node (ref "BAT1") (pin "2") (pinfunction "NTC_2") (pintype "unspecified+no_connect"))
    )
    (net (code "209") (name "unconnected-(CONN1-Pad1)") (class "Default")
      (node (ref "CONN1") (pin "1") (pinfunction "1_1") (pintype "unspecified+no_connect"))
    )
    (net (code "210") (name "unconnected-(J17-NC-Pad17)") (class "Default")
      (node (ref "J17") (pin "17") (pinfunction "NC_17") (pintype "unspecified+no_connect"))
    )
    (net (code "211") (name "unconnected-(J17-NC-Pad18)") (class "Default")
      (node (ref "J17") (pin "18") (pinfunction "NC_18") (pintype "unspecified+no_connect"))
    )
    (net (code "212") (name "unconnected-(J17-NC-Pad19)") (class "Default")
      (node (ref "J17") (pin "19") (pinfunction "NC_19") (pintype "unspecified+no_connect"))
    )
    (net (code "213") (name "unconnected-(J17-NC-Pad20)") (class "Default")
      (node (ref "J17") (pin "20") (pinfunction "NC_20") (pintype "unspecified+no_connect"))
    )
    (net (code "214") (name "unconnected-(J17-NC-Pad21)") (class "Default")
      (node (ref "J17") (pin "21") (pinfunction "NC_21") (pintype "unspecified+no_connect"))
    )
    (net (code "215") (name "unconnected-(J17-NC-Pad22)") (class "Default")
      (node (ref "J17") (pin "22") (pinfunction "NC_22") (pintype "unspecified+no_connect"))
    )
    (net (code "216") (name "unconnected-(U1-1V8-Pad83)") (class "Default")
      (node (ref "U1") (pin "83") (pinfunction "1V8_83") (pintype "unspecified+no_connect"))
    )
    (net (code "217") (name "unconnected-(U1-2V5-Pad114)") (class "Default")
      (node (ref "U1") (pin "114") (pinfunction "2V5_114") (pintype "unspecified"))
    )
    (net (code "218") (name "unconnected-(U1-CODEC_AIN_N-Pad91)") (class "Default")
      (node (ref "U1") (pin "91") (pinfunction "CODEC_AIN_N_91") (pintype "unspecified+no_connect"))
    )
    (net (code "219") (name "unconnected-(U1-CODEC_AIN_P-Pad92)") (class "Default")
      (node (ref "U1") (pin "92") (pinfunction "CODEC_AIN_P_92") (pintype "unspecified+no_connect"))
    )
    (net (code "220") (name "unconnected-(U1-CODEC_MICBIAS-Pad90)") (class "Default")
      (node (ref "U1") (pin "90") (pinfunction "CODEC_MICBIAS_90") (pintype "unspecified+no_connect"))
    )
    (net (code "221") (name "unconnected-(U1-CODEC_PWMLN-Pad94)") (class "Default")
      (node (ref "U1") (pin "94") (pinfunction "CODEC_PWMLN_94") (pintype "unspecified+no_connect"))
    )
    (net (code "222") (name "unconnected-(U1-CODEC_PWMLP-Pad93)") (class "Default")
      (node (ref "U1") (pin "93") (pinfunction "CODEC_PWMLP_93") (pintype "unspecified+no_connect"))
    )
    (net (code "223") (name "unconnected-(U1-CODEC_PWMRN-Pad95)") (class "Default")
      (node (ref "U1") (pin "95") (pinfunction "CODEC_PWMRN_95") (pintype "unspecified+no_connect"))
    )
    (net (code "224") (name "unconnected-(U1-CODEC_PWMRP-Pad96)") (class "Default")
      (node (ref "U1") (pin "96") (pinfunction "CODEC_PWMRP_96") (pintype "unspecified+no_connect"))
    )
    (net (code "225") (name "unconnected-(U1-CPU_FUSE-Pad77)") (class "Default")
      (node (ref "U1") (pin "77") (pinfunction "CPU_FUSE_77") (pintype "unspecified+no_connect"))
    )
    (net (code "226") (name "unconnected-(U1-PA02_SLCD_D2-Pad4)") (class "Default")
      (node (ref "U1") (pin "4") (pinfunction "PA02_SLCD_D2_4") (pintype "unspecified"))
    )
    (net (code "227") (name "unconnected-(U1-PA03_SLCD_D3-Pad7)") (class "Default")
      (node (ref "U1") (pin "7") (pinfunction "PA03_SLCD_D3_7") (pintype "unspecified"))
    )
    (net (code "228") (name "unconnected-(U1-PB05_DMIC_IN1-Pad80)") (class "Default")
      (node (ref "U1") (pin "80") (pinfunction "PB05_DMIC_IN1_80") (pintype "unspecified+no_connect"))
    )
    (net (code "229") (name "unconnected-(U1-PB08_MAC_RXD1-Pad101)") (class "Default")
      (node (ref "U1") (pin "101") (pinfunction "PB08_MAC_RXD1_101") (pintype "unspecified"))
    )
    (net (code "230") (name "unconnected-(U1-PB09_MAC_RXD0-Pad100)") (class "Default")
      (node (ref "U1") (pin "100") (pinfunction "PB09_MAC_RXD0_100") (pintype "unspecified"))
    )
    (net (code "231") (name "unconnected-(U1-PB11_MAC_TXD1-Pad115)") (class "Default")
      (node (ref "U1") (pin "115") (pinfunction "PB11_MAC_TXD1_115") (pintype "unspecified"))
    )
    (net (code "232") (name "unconnected-(U1-PB14_MAC_MDIO-Pad102)") (class "Default")
      (node (ref "U1") (pin "102") (pinfunction "PB14_MAC_MDIO_102") (pintype "unspecified"))
    )
    (net (code "233") (name "unconnected-(U1-PB16_SLCD_RD#-Pad3)") (class "Default")
      (node (ref "U1") (pin "3") (pinfunction "PB16_SLCD_RD#_3") (pintype "unspecified"))
    )
    (net (code "234") (name "unconnected-(U1-PB21_DMIC_CLK-Pad81)") (class "Default")
      (node (ref "U1") (pin "81") (pinfunction "PB21_DMIC_CLK_81") (pintype "unspecified+no_connect"))
    )
    (net (code "235") (name "unconnected-(U1-PB22_DMIC_IN0-Pad61)") (class "Default")
      (node (ref "U1") (pin "61") (pinfunction "PB22_DMIC_IN0_61") (pintype "unspecified+no_connect"))
    )
    (net (code "236") (name "unconnected-(U1-PB25_DRV_VBUS-Pad84)") (class "Default")
      (node (ref "U1") (pin "84") (pinfunction "PB25_DRV_VBUS_84") (pintype "unspecified+no_connect"))
    )
    (net (code "237") (name "unconnected-(U1-PC26_I2C1_SCL_PWM1-Pad63)") (class "Default")
      (node (ref "U1") (pin "63") (pinfunction "PC26_I2C1_SCL_PWM1_63") (pintype "unspecified+no_connect"))
    )
    (net (code "238") (name "unconnected-(U1-PC27_I2C1_SDA_PWM2-Pad62)") (class "Default")
      (node (ref "U1") (pin "62") (pinfunction "PC27_I2C1_SDA_PWM2_62") (pintype "unspecified+no_connect"))
    )
    (net (code "239") (name "unconnected-(U2-P15-Pad15)") (class "Default")
      (node (ref "U2") (pin "15") (pinfunction "P15_15") (pintype "unspecified"))
    )
    (net (code "240") (name "unconnected-(U3-CHRG-Pad8)") (class "Default")
      (node (ref "U3") (pin "8") (pinfunction "CHRG_8") (pintype "unspecified+no_connect"))
    )
    (net (code "241") (name "unconnected-(U3-INTN-Pad4)") (class "Default")
      (node (ref "U3") (pin "4") (pinfunction "INTN_4") (pintype "unspecified+no_connect"))
    )
    (net (code "242") (name "unconnected-(U3-NC-Pad6)") (class "Default")
      (node (ref "U3") (pin "6") (pinfunction "NC_6") (pintype "unspecified+no_connect"))
    )
    (net (code "243") (name "unconnected-(U18-PIO0-Pad25)") (class "Default")
      (node (ref "U18") (pin "25") (pinfunction "PIO0_25") (pintype "unspecified+no_connect"))
    )
    (net (code "244") (name "unconnected-(U18-PIO3-Pad30)") (class "Default")
      (node (ref "U18") (pin "30") (pinfunction "PIO3_30") (pintype "unspecified+no_connect"))
    )
    (net (code "245") (name "unconnected-(U18-PIO10-Pad33)") (class "Default")
      (node (ref "U18") (pin "33") (pinfunction "PIO10_33") (pintype "unspecified+no_connect"))
    )
    (net (code "246") (name "unconnected-(U18-PIO14-Pad13)") (class "Default")
      (node (ref "U18") (pin "13") (pinfunction "PIO14_13") (pintype "unspecified+no_connect"))
    )
    (net (code "247") (name "unconnected-(U18-PIO15-Pad36)") (class "Default")
      (node (ref "U18") (pin "36") (pinfunction "PIO15_36") (pintype "unspecified+no_connect"))
    )
    (net (code "248") (name "unconnected-(U18-PIO16-Pad37)") (class "Default")
      (node (ref "U18") (pin "37") (pinfunction "PIO16_37") (pintype "unspecified+no_connect"))
    )
    (net (code "249") (name "unconnected-(U18-RTC_XO-Pad11)") (class "Default")
      (node (ref "U18") (pin "11") (pinfunction "RTC_XO_11") (pintype "unspecified+no_connect"))
    )
    (net (code "250") (name "unconnected-(U18-TCK-Pad15)") (class "Default")
      (node (ref "U18") (pin "15") (pinfunction "TCK_15") (pintype "unspecified+no_connect"))
    )
    (net (code "251") (name "unconnected-(U18-TMS-Pad16)") (class "Default")
      (node (ref "U18") (pin "16") (pinfunction "TMS_16") (pintype "unspecified+no_connect"))
    )
    (net (code "252") (name "unconnected-(U18-T_SENSE-Pad20)") (class "Default")
      (node (ref "U18") (pin "20") (pinfunction "T_SENSE_20") (pintype "unspecified+no_connect"))
    )
    (net (code "253") (name "unconnected-(U18-USB_DM-Pad8)") (class "Default")
      (node (ref "U18") (pin "8") (pinfunction "USB_DM_8") (pintype "unspecified+no_connect"))
    )
    (net (code "254") (name "unconnected-(U18-USB_P-Pad10)") (class "Default")
      (node (ref "U18") (pin "10") (pinfunction "USB_P_10") (pintype "unspecified+no_connect"))
    )
    (net (code "255") (name "unconnected-(U18-XTAL_O-Pad4)") (class "Default")
      (node (ref "U18") (pin "4") (pinfunction "XTAL_O_4") (pintype "unspecified+no_connect"))
    )
    (net (code "256") (name "unconnected-(U32-D+-Pad2)") (class "Default")
      (node (ref "U32") (pin "2") (pinfunction "D+_2") (pintype "unspecified+no_connect"))
    )
    (net (code "257") (name "unconnected-(U32-D--Pad3)") (class "Default")
      (node (ref "U32") (pin "3") (pinfunction "D-_3") (pintype "unspecified+no_connect"))
    )
    (net (code "258") (name "unconnected-(U32-DSEL-Pad24)") (class "Default")
      (node (ref "U32") (pin "24") (pinfunction "DSEL_24") (pintype "unspecified+no_connect"))
    )
    (net (code "259") (name "unconnected-(U32-STAT-Pad4)") (class "Default")
      (node (ref "U32") (pin "4") (pinfunction "STAT_4") (pintype "unspecified+no_connect"))
    )
    (net (code "260") (name "unconnected-(U48-NC1-Pad6)") (class "Default")
      (node (ref "U48") (pin "6") (pinfunction "NC1_6") (pintype "unspecified+no_connect"))
    )
    (net (code "261") (name "unconnected-(U48-NC2-Pad7)") (class "Default")
      (node (ref "U48") (pin "7") (pinfunction "NC2_7") (pintype "unspecified+no_connect"))
    )
    (net (code "262") (name "unconnected-(U48-NC3-Pad8)") (class "Default")
      (node (ref "U48") (pin "8") (pinfunction "NC3_8") (pintype "unspecified+no_connect"))
    )
    (net (code "263") (name "unconnected-(U48-NC4-Pad10)") (class "Default")
      (node (ref "U48") (pin "10") (pinfunction "NC4_10") (pintype "unspecified+no_connect"))
    )
    (net (code "264") (name "unconnected-(U48-NC5-Pad11)") (class "Default")
      (node (ref "U48") (pin "11") (pinfunction "NC5_11") (pintype "unspecified+no_connect"))
    )
    (net (code "265") (name "unconnected-(U48-NC6-Pad12)") (class "Default")
      (node (ref "U48") (pin "12") (pinfunction "NC6_12") (pintype "unspecified+no_connect"))
    )
    (net (code "266") (name "unconnected-(U48-NC7-Pad13)") (class "Default")
      (node (ref "U48") (pin "13") (pinfunction "NC7_13") (pintype "unspecified+no_connect"))
    )
    (net (code "267") (name "unconnected-(U48-NC8-Pad15)") (class "Default")
      (node (ref "U48") (pin "15") (pinfunction "NC8_15") (pintype "unspecified+no_connect"))
    )
    (net (code "268") (name "unconnected-(U48-NC9-Pad16)") (class "Default")
      (node (ref "U48") (pin "16") (pinfunction "NC9_16") (pintype "unspecified+no_connect"))
    )
    (net (code "269") (name "unconnected-(U48-NC10-Pad22)") (class "Default")
      (node (ref "U48") (pin "22") (pinfunction "NC10_22") (pintype "unspecified+no_connect"))
    )
    (net (code "270") (name "unconnected-(U48-WL_GPIO1-Pad18)") (class "Default")
      (node (ref "U48") (pin "18") (pinfunction "WL_GPIO1_18") (pintype "unspecified+no_connect"))
    )
    (net (code "271") (name "unconnected-(U48-WL_GPIO2-Pad17)") (class "Default")
      (node (ref "U48") (pin "17") (pinfunction "WL_GPIO2_17") (pintype "unspecified+no_connect"))
    )
    (net (code "272") (name "unconnected-(U64-DIO3-Pad6)") (class "Default")
      (node (ref "U64") (pin "6") (pinfunction "DIO3_6") (pintype "unspecified+no_connect"))
    )
    (net (code "273") (name "unconnected-(U128-CSB-Pad15)") (class "Default")
      (node (ref "U128") (pin "15") (pinfunction "CSB_15") (pintype "unspecified+no_connect"))
    )
    (net (code "274") (name "unconnected-(U128-LLIN{slash}GPIO2-Pad3)") (class "Default")
      (node (ref "U128") (pin "3") (pinfunction "LLIN/GPIO2_3") (pintype "unspecified+no_connect"))
    )
    (net (code "275") (name "unconnected-(U128-LSPKOUT-Pad25)") (class "Default")
      (node (ref "U128") (pin "25") (pinfunction "LSPKOUT_25") (pintype "unspecified+no_connect"))
    )
    (net (code "276") (name "unconnected-(U128-RLIN{slash}GPIO3-Pad6)") (class "Default")
      (node (ref "U128") (pin "6") (pinfunction "RLIN/GPIO3_6") (pintype "unspecified+no_connect"))
    )
    (net (code "277") (name "unconnected-(U128-RSPKOUT-Pad23)") (class "Default")
      (node (ref "U128") (pin "23") (pinfunction "RSPKOUT_23") (pintype "unspecified+no_connect"))
    )
    (net (code "278") (name "unconnected-(U135-SS_SW-Pad9)") (class "Default")
      (node (ref "U135") (pin "9") (pinfunction "SS_SW_9") (pintype "unspecified+no_connect"))
    )
    (net (code "279") (name "unconnected-(U140-EQ1-Pad12)") (class "Default")
      (node (ref "U140") (pin "12") (pinfunction "EQ1_12") (pintype "unspecified+no_connect"))
    )
    (net (code "280") (name "unconnected-(U140-EQ2-Pad13)") (class "Default")
      (node (ref "U140") (pin "13") (pinfunction "EQ2_13") (pintype "unspecified+no_connect"))
    )
    (net (code "281") (name "unconnected-(U140-EQ3-Pad14)") (class "Default")
      (node (ref "U140") (pin "14") (pinfunction "EQ3_14") (pintype "unspecified+no_connect"))
    )
    (net (code "282") (name "unconnected-(U140-NC-Pad5)") (class "Default")
      (node (ref "U140") (pin "5") (pinfunction "NC_5") (pintype "unspecified+no_connect"))
    )
    (net (code "283") (name "unconnected-(U140-SPOUT1-Pad17)") (class "Default")
      (node (ref "U140") (pin "17") (pinfunction "SPOUT1_17") (pintype "unspecified+no_connect"))
    )
    (net (code "284") (name "unconnected-(U140-SPOUT2-Pad18)") (class "Default")
      (node (ref "U140") (pin "18") (pinfunction "SPOUT2_18") (pintype "unspecified+no_connect"))
    )
    (net (code "285") (name "unconnected-(U140-SPVDD-Pad15)") (class "Default")
      (node (ref "U140") (pin "15") (pinfunction "SPVDD_15") (pintype "unspecified+no_connect"))
    )
    (net (code "286") (name "unconnected-(U141-P10-Pad10)") (class "Default")
      (node (ref "U141") (pin "10") (pinfunction "P10_10") (pintype "unspecified+no_connect"))
    )
    (net (code "287") (name "unconnected-(U204-FOUT-Pad4)") (class "Default")
      (node (ref "U204") (pin "4") (pinfunction "FOUT_4") (pintype "unspecified+no_connect"))
    )
    (net (code "288") (name "unconnected-(U204-T1-Pad6)") (class "Default")
      (node (ref "U204") (pin "6") (pinfunction "T1_6") (pintype "unspecified+no_connect"))
    )
    (net (code "289") (name "unconnected-(U204-T2-Pad8)") (class "Default")
      (node (ref "U204") (pin "8") (pinfunction "T2_8") (pintype "unspecified+no_connect"))
    )
  )
)
